# base.net
KiCad netlist of a schematic drawn in EAGLE
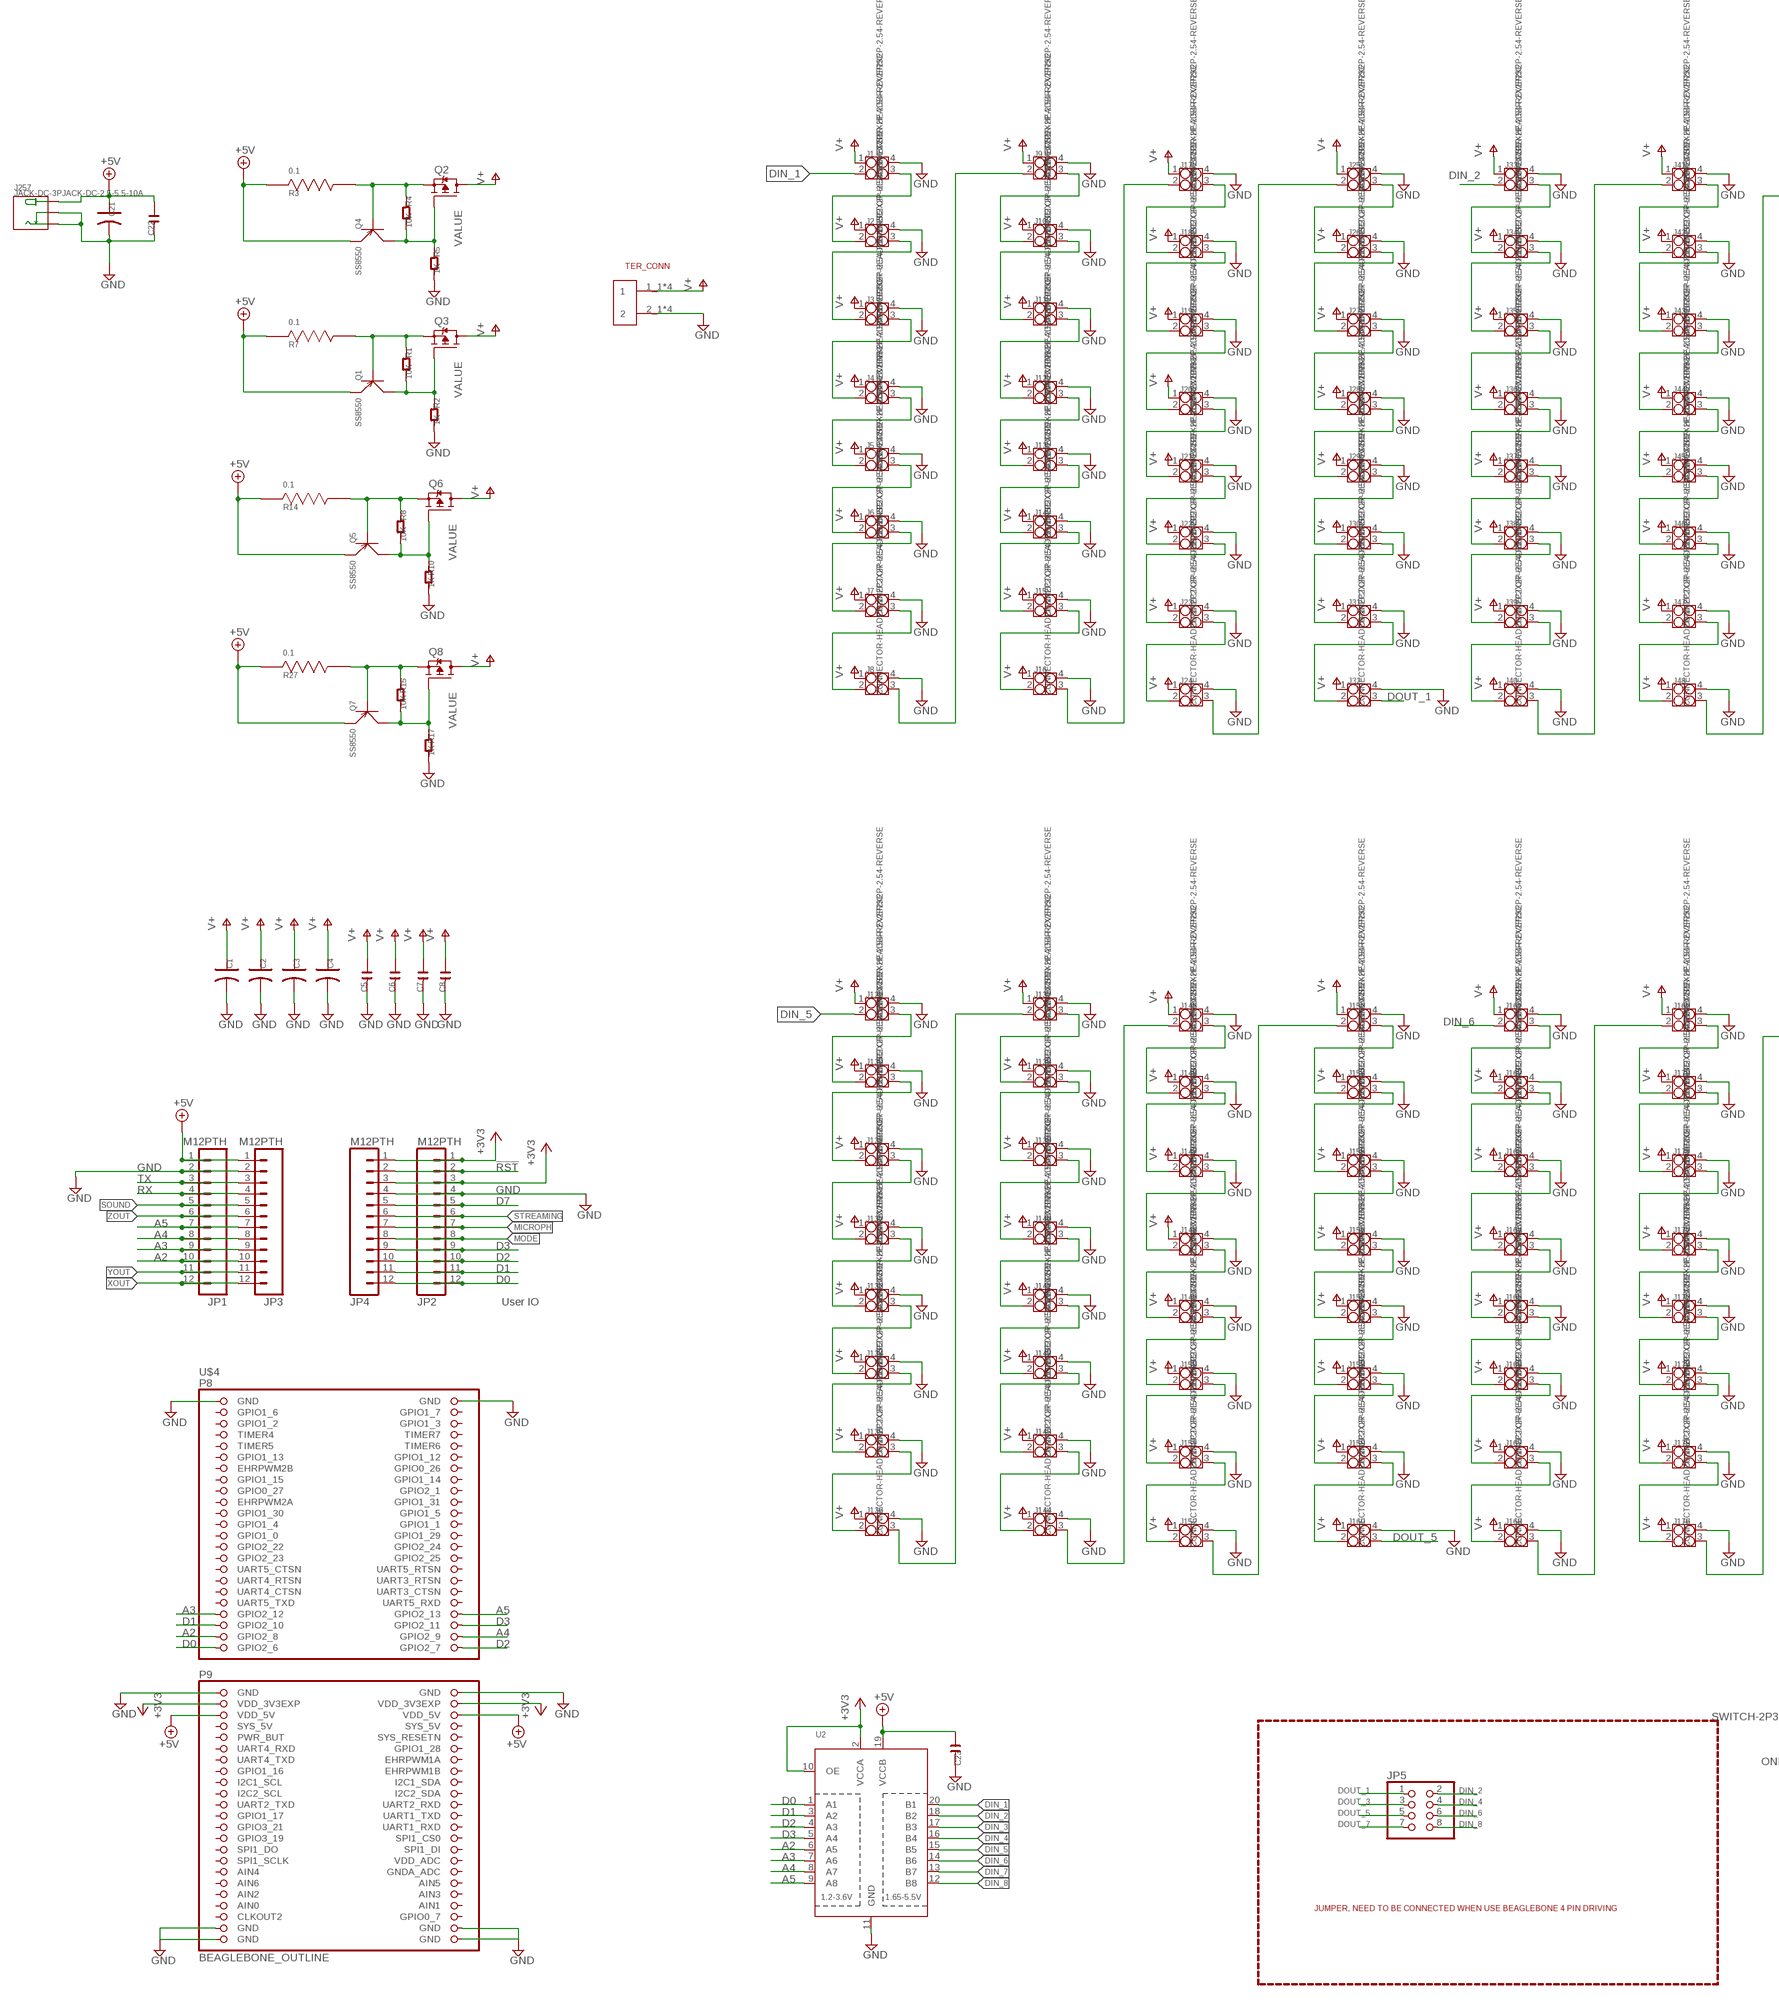
[diagram p0: schematic, sheet 1, part 1 of 2]
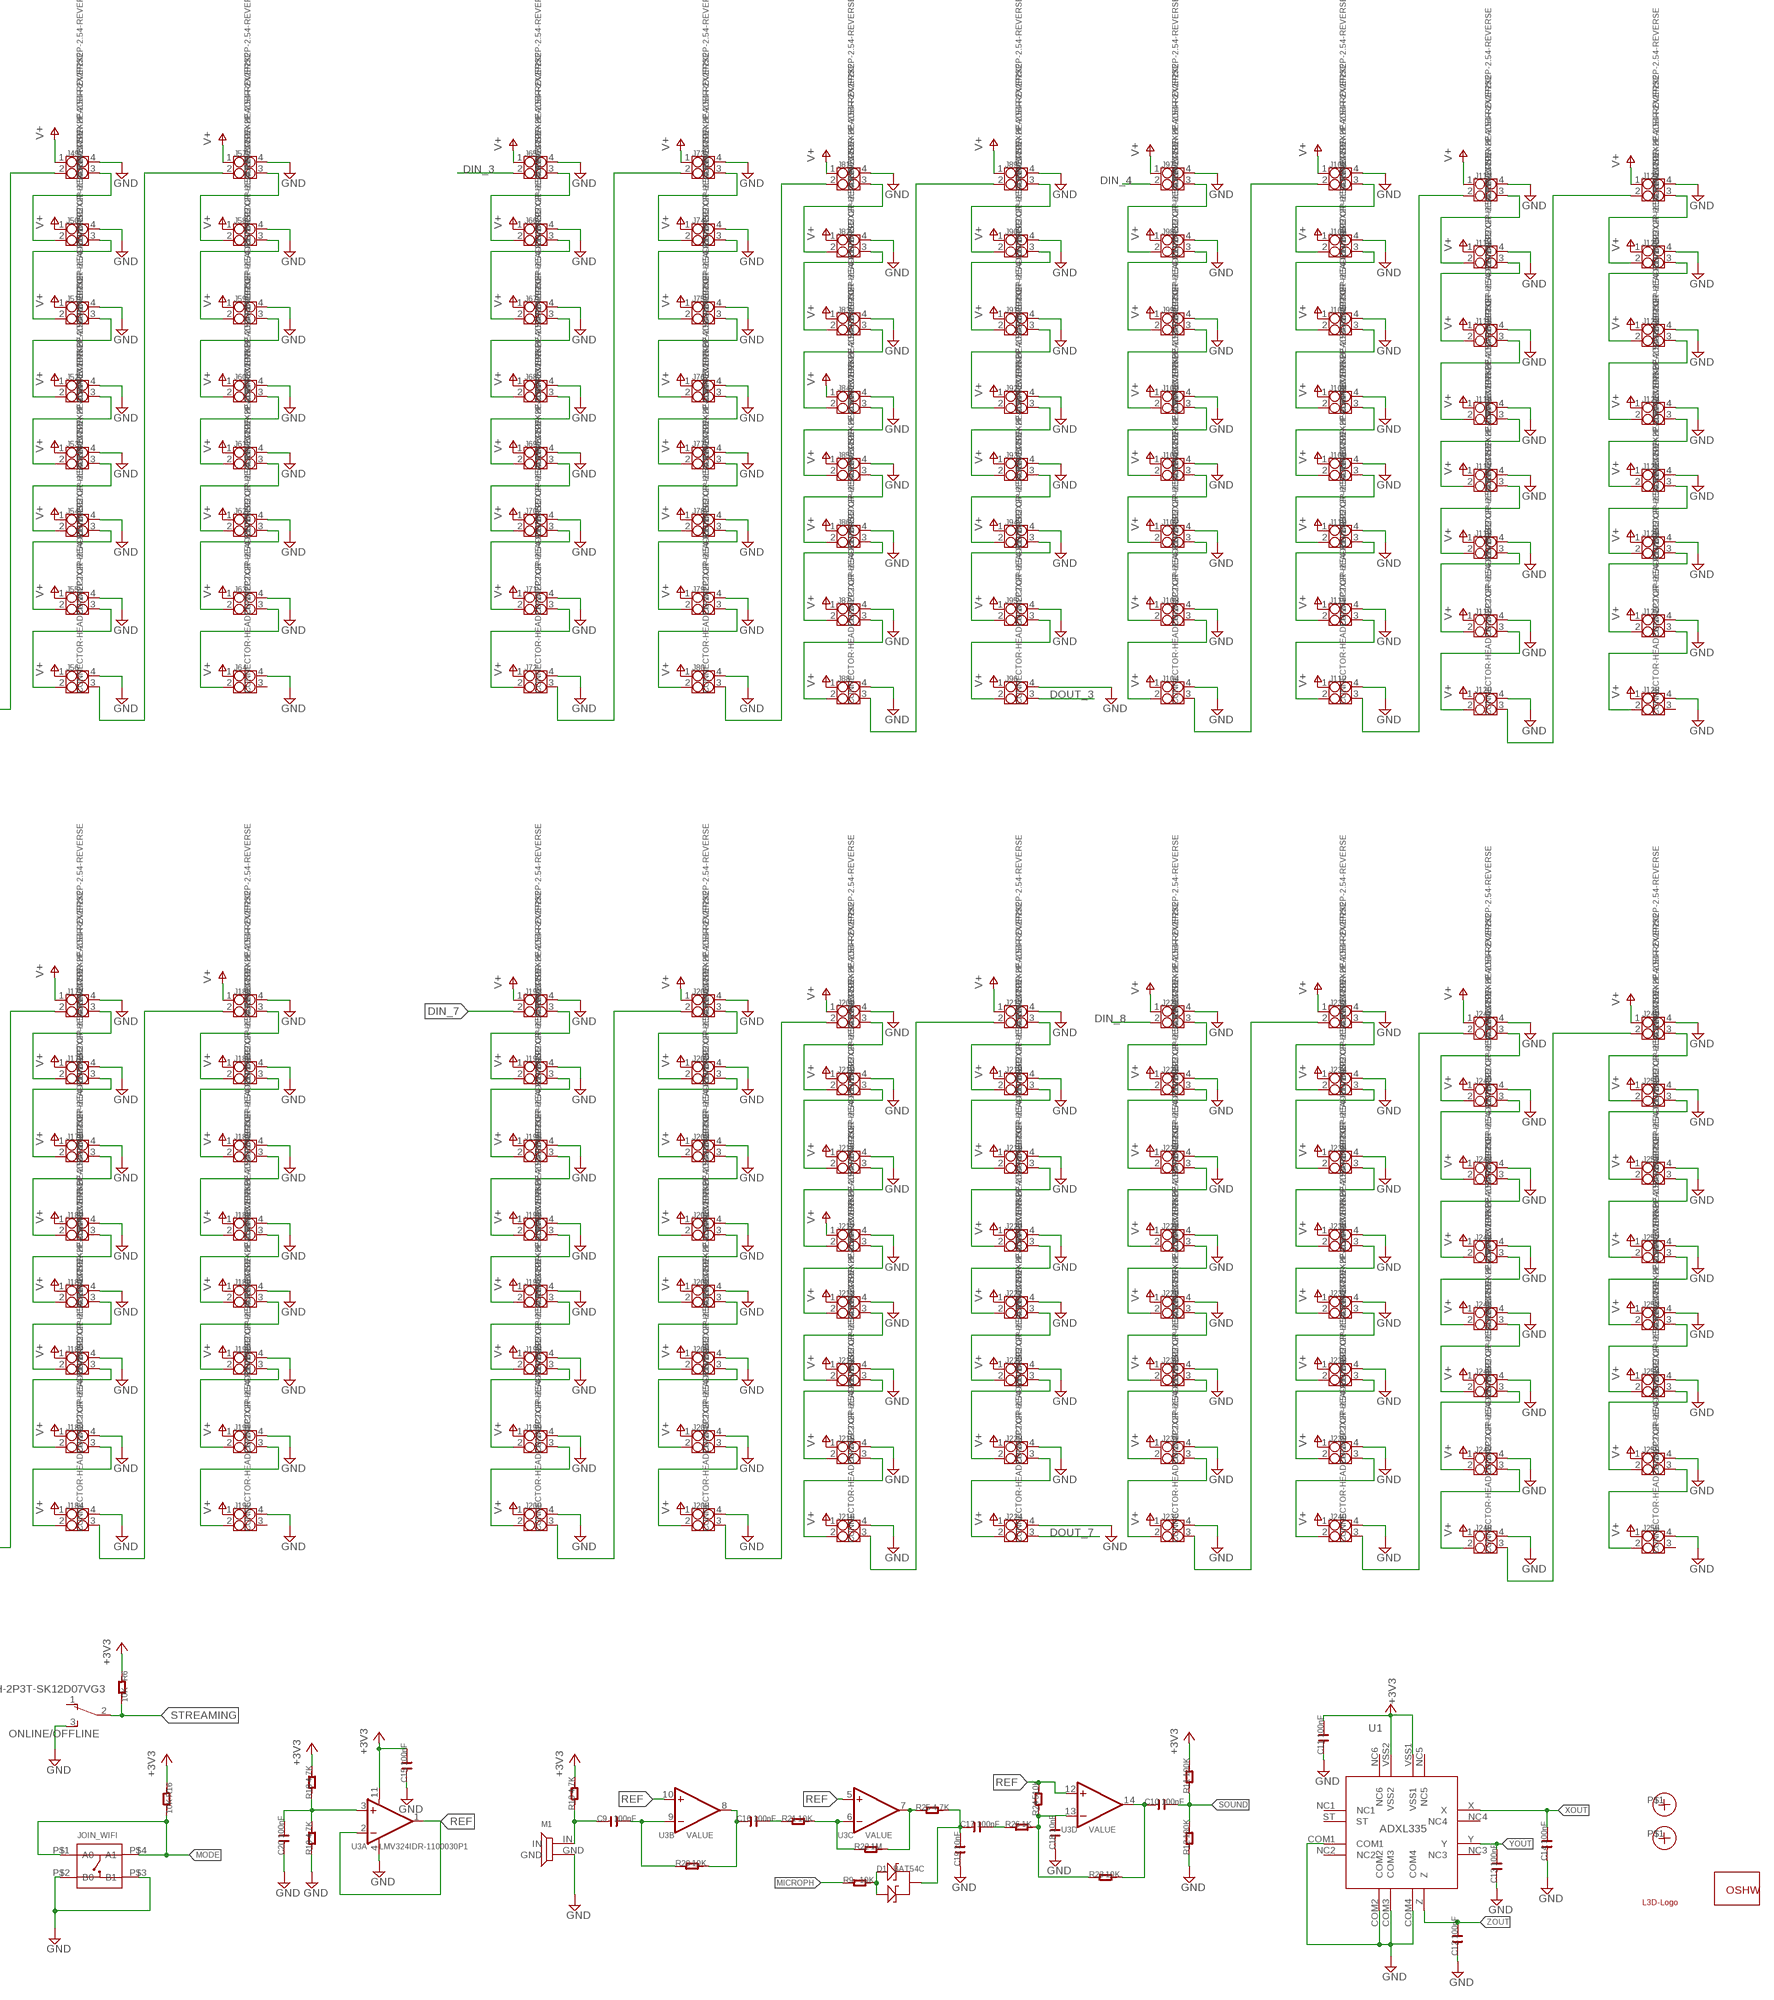
[diagram p1: schematic, sheet 1, part 2 of 2]

(export (version "E")
  (design (tool "Eeschema 10.0.6"))
  (components
    (comp (ref "C1")
      (value "C-POLAR")
      (footprint "eagle-import:CAPACITOR-E3-8")
      (libsource (lib "eagle-import") (part "C-POLAR"))
    )
    (comp (ref "C2")
      (value "C-POLAR")
      (footprint "eagle-import:CAPACITOR-E3-8")
      (libsource (lib "eagle-import") (part "C-POLAR"))
    )
    (comp (ref "C3")
      (value "C-POLAR")
      (footprint "eagle-import:CAPACITOR-E3-8")
      (libsource (lib "eagle-import") (part "C-POLAR"))
    )
    (comp (ref "C4")
      (value "C-POLAR")
      (footprint "eagle-import:CAPACITOR-E3-8")
      (libsource (lib "eagle-import") (part "C-POLAR"))
    )
    (comp (ref "C5")
      (value "C-0603")
      (footprint "eagle-import:C0603")
      (libsource (lib "eagle-import") (part "C-0603"))
    )
    (comp (ref "C6")
      (value "C-0603")
      (footprint "eagle-import:C0603")
      (libsource (lib "eagle-import") (part "C-0603"))
    )
    (comp (ref "C7")
      (value "C-0603")
      (footprint "eagle-import:C0603")
      (libsource (lib "eagle-import") (part "C-0603"))
    )
    (comp (ref "C8")
      (value "C-0603")
      (footprint "eagle-import:C0603")
      (libsource (lib "eagle-import") (part "C-0603"))
    )
    (comp (ref "C9")
      (value "100nF")
      (footprint "eagle-import:C0603")
      (libsource (lib "eagle-import") (part "C-0603"))
    )
    (comp (ref "C10")
      (value "100nF")
      (footprint "eagle-import:C0603")
      (libsource (lib "eagle-import") (part "C-0603"))
    )
    (comp (ref "C11")
      (value "100nF")
      (footprint "eagle-import:C0603")
      (libsource (lib "eagle-import") (part "C-0603"))
    )
    (comp (ref "C12")
      (value "100nF")
      (footprint "eagle-import:C0603")
      (libsource (lib "eagle-import") (part "C-0603"))
    )
    (comp (ref "C13")
      (value "100nF")
      (footprint "eagle-import:C0603")
      (libsource (lib "eagle-import") (part "C-0603"))
    )
    (comp (ref "C14")
      (value "100nF")
      (footprint "eagle-import:C0603")
      (libsource (lib "eagle-import") (part "C-0603"))
    )
    (comp (ref "C15")
      (value "100nF")
      (footprint "eagle-import:C0603")
      (libsource (lib "eagle-import") (part "C-0603"))
    )
    (comp (ref "C16")
      (value "100nF")
      (footprint "eagle-import:C0603")
      (libsource (lib "eagle-import") (part "C-0603"))
    )
    (comp (ref "C17")
      (value "100nF")
      (footprint "eagle-import:C0603")
      (libsource (lib "eagle-import") (part "C-0603"))
    )
    (comp (ref "C18")
      (value "10nF")
      (footprint "eagle-import:C0603")
      (libsource (lib "eagle-import") (part "C-0603"))
    )
    (comp (ref "C19")
      (value "10nF")
      (footprint "eagle-import:C0603")
      (libsource (lib "eagle-import") (part "C-0603"))
    )
    (comp (ref "C20")
      (value "100nF")
      (footprint "eagle-import:C0603")
      (libsource (lib "eagle-import") (part "C-0603"))
    )
    (comp (ref "C21")
      (value "C-POLAR")
      (footprint "eagle-import:CAPACITOR-E3-8")
      (libsource (lib "eagle-import") (part "C-POLAR"))
    )
    (comp (ref "C22")
      (value "C-0603")
      (footprint "eagle-import:C0603")
      (libsource (lib "eagle-import") (part "C-0603"))
    )
    (comp (ref "C23")
      (value "C-0603")
      (footprint "eagle-import:C0603")
      (libsource (lib "eagle-import") (part "C-0603"))
    )
    (comp (ref "D1")
      (value "BAT54C")
      (footprint "eagle-import:SOT23")
      (libsource (lib "eagle-import") (part "BAT54C"))
    )
    (comp (ref "GOLD_ORB_SM1")
      (value "OSHWLOGO_GOLD_ORB_LG")
      (footprint "eagle-import:OSHW0")
      (libsource (lib "eagle-import") (part "OSHWLOGO_GOLD_ORB_LG"))
    )
    (comp (ref "J1")
      (value "CONNECTOR-HEADER-2X2P2X2P-2.54-REVERSE")
      (footprint "eagle-import:2X2P-2.54-REVERSE")
      (libsource (lib "eagle-import") (part "CONNECTOR-HEADER-2X2P2X2P-2.54-REVERSE"))
    )
    (comp (ref "J2")
      (value "CONNECTOR-HEADER-2X2P2X2P-2.54-REVERSE")
      (footprint "eagle-import:2X2P-2.54-REVERSE")
      (libsource (lib "eagle-import") (part "CONNECTOR-HEADER-2X2P2X2P-2.54-REVERSE"))
    )
    (comp (ref "J3")
      (value "CONNECTOR-HEADER-2X2P2X2P-2.54-REVERSE")
      (footprint "eagle-import:2X2P-2.54-REVERSE")
      (libsource (lib "eagle-import") (part "CONNECTOR-HEADER-2X2P2X2P-2.54-REVERSE"))
    )
    (comp (ref "J4")
      (value "CONNECTOR-HEADER-2X2P2X2P-2.54-REVERSE")
      (footprint "eagle-import:2X2P-2.54-REVERSE")
      (libsource (lib "eagle-import") (part "CONNECTOR-HEADER-2X2P2X2P-2.54-REVERSE"))
    )
    (comp (ref "J5")
      (value "CONNECTOR-HEADER-2X2P2X2P-2.54-REVERSE")
      (footprint "eagle-import:2X2P-2.54-REVERSE")
      (libsource (lib "eagle-import") (part "CONNECTOR-HEADER-2X2P2X2P-2.54-REVERSE"))
    )
    (comp (ref "J6")
      (value "CONNECTOR-HEADER-2X2P2X2P-2.54-REVERSE")
      (footprint "eagle-import:2X2P-2.54-REVERSE")
      (libsource (lib "eagle-import") (part "CONNECTOR-HEADER-2X2P2X2P-2.54-REVERSE"))
    )
    (comp (ref "J7")
      (value "CONNECTOR-HEADER-2X2P2X2P-2.54-REVERSE")
      (footprint "eagle-import:2X2P-2.54-REVERSE")
      (libsource (lib "eagle-import") (part "CONNECTOR-HEADER-2X2P2X2P-2.54-REVERSE"))
    )
    (comp (ref "J8")
      (value "CONNECTOR-HEADER-2X2P2X2P-2.54-REVERSE")
      (footprint "eagle-import:2X2P-2.54-REVERSE")
      (libsource (lib "eagle-import") (part "CONNECTOR-HEADER-2X2P2X2P-2.54-REVERSE"))
    )
    (comp (ref "J9")
      (value "CONNECTOR-HEADER-2X2P2X2P-2.54-REVERSE")
      (footprint "eagle-import:2X2P-2.54-REVERSE")
      (libsource (lib "eagle-import") (part "CONNECTOR-HEADER-2X2P2X2P-2.54-REVERSE"))
    )
    (comp (ref "J10")
      (value "CONNECTOR-HEADER-2X2P2X2P-2.54-REVERSE")
      (footprint "eagle-import:2X2P-2.54-REVERSE")
      (libsource (lib "eagle-import") (part "CONNECTOR-HEADER-2X2P2X2P-2.54-REVERSE"))
    )
    (comp (ref "J11")
      (value "CONNECTOR-HEADER-2X2P2X2P-2.54-REVERSE")
      (footprint "eagle-import:2X2P-2.54-REVERSE")
      (libsource (lib "eagle-import") (part "CONNECTOR-HEADER-2X2P2X2P-2.54-REVERSE"))
    )
    (comp (ref "J12")
      (value "CONNECTOR-HEADER-2X2P2X2P-2.54-REVERSE")
      (footprint "eagle-import:2X2P-2.54-REVERSE")
      (libsource (lib "eagle-import") (part "CONNECTOR-HEADER-2X2P2X2P-2.54-REVERSE"))
    )
    (comp (ref "J13")
      (value "CONNECTOR-HEADER-2X2P2X2P-2.54-REVERSE")
      (footprint "eagle-import:2X2P-2.54-REVERSE")
      (libsource (lib "eagle-import") (part "CONNECTOR-HEADER-2X2P2X2P-2.54-REVERSE"))
    )
    (comp (ref "J14")
      (value "CONNECTOR-HEADER-2X2P2X2P-2.54-REVERSE")
      (footprint "eagle-import:2X2P-2.54-REVERSE")
      (libsource (lib "eagle-import") (part "CONNECTOR-HEADER-2X2P2X2P-2.54-REVERSE"))
    )
    (comp (ref "J15")
      (value "CONNECTOR-HEADER-2X2P2X2P-2.54-REVERSE")
      (footprint "eagle-import:2X2P-2.54-REVERSE")
      (libsource (lib "eagle-import") (part "CONNECTOR-HEADER-2X2P2X2P-2.54-REVERSE"))
    )
    (comp (ref "J16")
      (value "CONNECTOR-HEADER-2X2P2X2P-2.54-REVERSE")
      (footprint "eagle-import:2X2P-2.54-REVERSE")
      (libsource (lib "eagle-import") (part "CONNECTOR-HEADER-2X2P2X2P-2.54-REVERSE"))
    )
    (comp (ref "J17")
      (value "CONNECTOR-HEADER-2X2P2X2P-2.54-REVERSE")
      (footprint "eagle-import:2X2P-2.54-REVERSE")
      (libsource (lib "eagle-import") (part "CONNECTOR-HEADER-2X2P2X2P-2.54-REVERSE"))
    )
    (comp (ref "J18")
      (value "CONNECTOR-HEADER-2X2P2X2P-2.54-REVERSE")
      (footprint "eagle-import:2X2P-2.54-REVERSE")
      (libsource (lib "eagle-import") (part "CONNECTOR-HEADER-2X2P2X2P-2.54-REVERSE"))
    )
    (comp (ref "J19")
      (value "CONNECTOR-HEADER-2X2P2X2P-2.54-REVERSE")
      (footprint "eagle-import:2X2P-2.54-REVERSE")
      (libsource (lib "eagle-import") (part "CONNECTOR-HEADER-2X2P2X2P-2.54-REVERSE"))
    )
    (comp (ref "J20")
      (value "CONNECTOR-HEADER-2X2P2X2P-2.54-REVERSE")
      (footprint "eagle-import:2X2P-2.54-REVERSE")
      (libsource (lib "eagle-import") (part "CONNECTOR-HEADER-2X2P2X2P-2.54-REVERSE"))
    )
    (comp (ref "J21")
      (value "CONNECTOR-HEADER-2X2P2X2P-2.54-REVERSE")
      (footprint "eagle-import:2X2P-2.54-REVERSE")
      (libsource (lib "eagle-import") (part "CONNECTOR-HEADER-2X2P2X2P-2.54-REVERSE"))
    )
    (comp (ref "J22")
      (value "CONNECTOR-HEADER-2X2P2X2P-2.54-REVERSE")
      (footprint "eagle-import:2X2P-2.54-REVERSE")
      (libsource (lib "eagle-import") (part "CONNECTOR-HEADER-2X2P2X2P-2.54-REVERSE"))
    )
    (comp (ref "J23")
      (value "CONNECTOR-HEADER-2X2P2X2P-2.54-REVERSE")
      (footprint "eagle-import:2X2P-2.54-REVERSE")
      (libsource (lib "eagle-import") (part "CONNECTOR-HEADER-2X2P2X2P-2.54-REVERSE"))
    )
    (comp (ref "J24")
      (value "CONNECTOR-HEADER-2X2P2X2P-2.54-REVERSE")
      (footprint "eagle-import:2X2P-2.54-REVERSE")
      (libsource (lib "eagle-import") (part "CONNECTOR-HEADER-2X2P2X2P-2.54-REVERSE"))
    )
    (comp (ref "J25")
      (value "CONNECTOR-HEADER-2X2P2X2P-2.54-REVERSE")
      (footprint "eagle-import:2X2P-2.54-REVERSE")
      (libsource (lib "eagle-import") (part "CONNECTOR-HEADER-2X2P2X2P-2.54-REVERSE"))
    )
    (comp (ref "J26")
      (value "CONNECTOR-HEADER-2X2P2X2P-2.54-REVERSE")
      (footprint "eagle-import:2X2P-2.54-REVERSE")
      (libsource (lib "eagle-import") (part "CONNECTOR-HEADER-2X2P2X2P-2.54-REVERSE"))
    )
    (comp (ref "J27")
      (value "CONNECTOR-HEADER-2X2P2X2P-2.54-REVERSE")
      (footprint "eagle-import:2X2P-2.54-REVERSE")
      (libsource (lib "eagle-import") (part "CONNECTOR-HEADER-2X2P2X2P-2.54-REVERSE"))
    )
    (comp (ref "J28")
      (value "CONNECTOR-HEADER-2X2P2X2P-2.54-REVERSE")
      (footprint "eagle-import:2X2P-2.54-REVERSE")
      (libsource (lib "eagle-import") (part "CONNECTOR-HEADER-2X2P2X2P-2.54-REVERSE"))
    )
    (comp (ref "J29")
      (value "CONNECTOR-HEADER-2X2P2X2P-2.54-REVERSE")
      (footprint "eagle-import:2X2P-2.54-REVERSE")
      (libsource (lib "eagle-import") (part "CONNECTOR-HEADER-2X2P2X2P-2.54-REVERSE"))
    )
    (comp (ref "J30")
      (value "CONNECTOR-HEADER-2X2P2X2P-2.54-REVERSE")
      (footprint "eagle-import:2X2P-2.54-REVERSE")
      (libsource (lib "eagle-import") (part "CONNECTOR-HEADER-2X2P2X2P-2.54-REVERSE"))
    )
    (comp (ref "J31")
      (value "CONNECTOR-HEADER-2X2P2X2P-2.54-REVERSE")
      (footprint "eagle-import:2X2P-2.54-REVERSE")
      (libsource (lib "eagle-import") (part "CONNECTOR-HEADER-2X2P2X2P-2.54-REVERSE"))
    )
    (comp (ref "J32")
      (value "CONNECTOR-HEADER-2X2P2X2P-2.54-REVERSE")
      (footprint "eagle-import:2X2P-2.54-REVERSE")
      (libsource (lib "eagle-import") (part "CONNECTOR-HEADER-2X2P2X2P-2.54-REVERSE"))
    )
    (comp (ref "J33")
      (value "CONNECTOR-HEADER-2X2P2X2P-2.54-REVERSE")
      (footprint "eagle-import:2X2P-2.54-REVERSE")
      (libsource (lib "eagle-import") (part "CONNECTOR-HEADER-2X2P2X2P-2.54-REVERSE"))
    )
    (comp (ref "J34")
      (value "CONNECTOR-HEADER-2X2P2X2P-2.54-REVERSE")
      (footprint "eagle-import:2X2P-2.54-REVERSE")
      (libsource (lib "eagle-import") (part "CONNECTOR-HEADER-2X2P2X2P-2.54-REVERSE"))
    )
    (comp (ref "J35")
      (value "CONNECTOR-HEADER-2X2P2X2P-2.54-REVERSE")
      (footprint "eagle-import:2X2P-2.54-REVERSE")
      (libsource (lib "eagle-import") (part "CONNECTOR-HEADER-2X2P2X2P-2.54-REVERSE"))
    )
    (comp (ref "J36")
      (value "CONNECTOR-HEADER-2X2P2X2P-2.54-REVERSE")
      (footprint "eagle-import:2X2P-2.54-REVERSE")
      (libsource (lib "eagle-import") (part "CONNECTOR-HEADER-2X2P2X2P-2.54-REVERSE"))
    )
    (comp (ref "J37")
      (value "CONNECTOR-HEADER-2X2P2X2P-2.54-REVERSE")
      (footprint "eagle-import:2X2P-2.54-REVERSE")
      (libsource (lib "eagle-import") (part "CONNECTOR-HEADER-2X2P2X2P-2.54-REVERSE"))
    )
    (comp (ref "J38")
      (value "CONNECTOR-HEADER-2X2P2X2P-2.54-REVERSE")
      (footprint "eagle-import:2X2P-2.54-REVERSE")
      (libsource (lib "eagle-import") (part "CONNECTOR-HEADER-2X2P2X2P-2.54-REVERSE"))
    )
    (comp (ref "J39")
      (value "CONNECTOR-HEADER-2X2P2X2P-2.54-REVERSE")
      (footprint "eagle-import:2X2P-2.54-REVERSE")
      (libsource (lib "eagle-import") (part "CONNECTOR-HEADER-2X2P2X2P-2.54-REVERSE"))
    )
    (comp (ref "J40")
      (value "CONNECTOR-HEADER-2X2P2X2P-2.54-REVERSE")
      (footprint "eagle-import:2X2P-2.54-REVERSE")
      (libsource (lib "eagle-import") (part "CONNECTOR-HEADER-2X2P2X2P-2.54-REVERSE"))
    )
    (comp (ref "J41")
      (value "CONNECTOR-HEADER-2X2P2X2P-2.54-REVERSE")
      (footprint "eagle-import:2X2P-2.54-REVERSE")
      (libsource (lib "eagle-import") (part "CONNECTOR-HEADER-2X2P2X2P-2.54-REVERSE"))
    )
    (comp (ref "J42")
      (value "CONNECTOR-HEADER-2X2P2X2P-2.54-REVERSE")
      (footprint "eagle-import:2X2P-2.54-REVERSE")
      (libsource (lib "eagle-import") (part "CONNECTOR-HEADER-2X2P2X2P-2.54-REVERSE"))
    )
    (comp (ref "J43")
      (value "CONNECTOR-HEADER-2X2P2X2P-2.54-REVERSE")
      (footprint "eagle-import:2X2P-2.54-REVERSE")
      (libsource (lib "eagle-import") (part "CONNECTOR-HEADER-2X2P2X2P-2.54-REVERSE"))
    )
    (comp (ref "J44")
      (value "CONNECTOR-HEADER-2X2P2X2P-2.54-REVERSE")
      (footprint "eagle-import:2X2P-2.54-REVERSE")
      (libsource (lib "eagle-import") (part "CONNECTOR-HEADER-2X2P2X2P-2.54-REVERSE"))
    )
    (comp (ref "J45")
      (value "CONNECTOR-HEADER-2X2P2X2P-2.54-REVERSE")
      (footprint "eagle-import:2X2P-2.54-REVERSE")
      (libsource (lib "eagle-import") (part "CONNECTOR-HEADER-2X2P2X2P-2.54-REVERSE"))
    )
    (comp (ref "J46")
      (value "CONNECTOR-HEADER-2X2P2X2P-2.54-REVERSE")
      (footprint "eagle-import:2X2P-2.54-REVERSE")
      (libsource (lib "eagle-import") (part "CONNECTOR-HEADER-2X2P2X2P-2.54-REVERSE"))
    )
    (comp (ref "J47")
      (value "CONNECTOR-HEADER-2X2P2X2P-2.54-REVERSE")
      (footprint "eagle-import:2X2P-2.54-REVERSE")
      (libsource (lib "eagle-import") (part "CONNECTOR-HEADER-2X2P2X2P-2.54-REVERSE"))
    )
    (comp (ref "J48")
      (value "CONNECTOR-HEADER-2X2P2X2P-2.54-REVERSE")
      (footprint "eagle-import:2X2P-2.54-REVERSE")
      (libsource (lib "eagle-import") (part "CONNECTOR-HEADER-2X2P2X2P-2.54-REVERSE"))
    )
    (comp (ref "J49")
      (value "CONNECTOR-HEADER-2X2P2X2P-2.54-REVERSE")
      (footprint "eagle-import:2X2P-2.54-REVERSE")
      (libsource (lib "eagle-import") (part "CONNECTOR-HEADER-2X2P2X2P-2.54-REVERSE"))
    )
    (comp (ref "J50")
      (value "CONNECTOR-HEADER-2X2P2X2P-2.54-REVERSE")
      (footprint "eagle-import:2X2P-2.54-REVERSE")
      (libsource (lib "eagle-import") (part "CONNECTOR-HEADER-2X2P2X2P-2.54-REVERSE"))
    )
    (comp (ref "J51")
      (value "CONNECTOR-HEADER-2X2P2X2P-2.54-REVERSE")
      (footprint "eagle-import:2X2P-2.54-REVERSE")
      (libsource (lib "eagle-import") (part "CONNECTOR-HEADER-2X2P2X2P-2.54-REVERSE"))
    )
    (comp (ref "J52")
      (value "CONNECTOR-HEADER-2X2P2X2P-2.54-REVERSE")
      (footprint "eagle-import:2X2P-2.54-REVERSE")
      (libsource (lib "eagle-import") (part "CONNECTOR-HEADER-2X2P2X2P-2.54-REVERSE"))
    )
    (comp (ref "J53")
      (value "CONNECTOR-HEADER-2X2P2X2P-2.54-REVERSE")
      (footprint "eagle-import:2X2P-2.54-REVERSE")
      (libsource (lib "eagle-import") (part "CONNECTOR-HEADER-2X2P2X2P-2.54-REVERSE"))
    )
    (comp (ref "J54")
      (value "CONNECTOR-HEADER-2X2P2X2P-2.54-REVERSE")
      (footprint "eagle-import:2X2P-2.54-REVERSE")
      (libsource (lib "eagle-import") (part "CONNECTOR-HEADER-2X2P2X2P-2.54-REVERSE"))
    )
    (comp (ref "J55")
      (value "CONNECTOR-HEADER-2X2P2X2P-2.54-REVERSE")
      (footprint "eagle-import:2X2P-2.54-REVERSE")
      (libsource (lib "eagle-import") (part "CONNECTOR-HEADER-2X2P2X2P-2.54-REVERSE"))
    )
    (comp (ref "J56")
      (value "CONNECTOR-HEADER-2X2P2X2P-2.54-REVERSE")
      (footprint "eagle-import:2X2P-2.54-REVERSE")
      (libsource (lib "eagle-import") (part "CONNECTOR-HEADER-2X2P2X2P-2.54-REVERSE"))
    )
    (comp (ref "J57")
      (value "CONNECTOR-HEADER-2X2P2X2P-2.54-REVERSE")
      (footprint "eagle-import:2X2P-2.54-REVERSE")
      (libsource (lib "eagle-import") (part "CONNECTOR-HEADER-2X2P2X2P-2.54-REVERSE"))
    )
    (comp (ref "J58")
      (value "CONNECTOR-HEADER-2X2P2X2P-2.54-REVERSE")
      (footprint "eagle-import:2X2P-2.54-REVERSE")
      (libsource (lib "eagle-import") (part "CONNECTOR-HEADER-2X2P2X2P-2.54-REVERSE"))
    )
    (comp (ref "J59")
      (value "CONNECTOR-HEADER-2X2P2X2P-2.54-REVERSE")
      (footprint "eagle-import:2X2P-2.54-REVERSE")
      (libsource (lib "eagle-import") (part "CONNECTOR-HEADER-2X2P2X2P-2.54-REVERSE"))
    )
    (comp (ref "J60")
      (value "CONNECTOR-HEADER-2X2P2X2P-2.54-REVERSE")
      (footprint "eagle-import:2X2P-2.54-REVERSE")
      (libsource (lib "eagle-import") (part "CONNECTOR-HEADER-2X2P2X2P-2.54-REVERSE"))
    )
    (comp (ref "J61")
      (value "CONNECTOR-HEADER-2X2P2X2P-2.54-REVERSE")
      (footprint "eagle-import:2X2P-2.54-REVERSE")
      (libsource (lib "eagle-import") (part "CONNECTOR-HEADER-2X2P2X2P-2.54-REVERSE"))
    )
    (comp (ref "J62")
      (value "CONNECTOR-HEADER-2X2P2X2P-2.54-REVERSE")
      (footprint "eagle-import:2X2P-2.54-REVERSE")
      (libsource (lib "eagle-import") (part "CONNECTOR-HEADER-2X2P2X2P-2.54-REVERSE"))
    )
    (comp (ref "J63")
      (value "CONNECTOR-HEADER-2X2P2X2P-2.54-REVERSE")
      (footprint "eagle-import:2X2P-2.54-REVERSE")
      (libsource (lib "eagle-import") (part "CONNECTOR-HEADER-2X2P2X2P-2.54-REVERSE"))
    )
    (comp (ref "J64")
      (value "CONNECTOR-HEADER-2X2P2X2P-2.54-REVERSE")
      (footprint "eagle-import:2X2P-2.54-REVERSE")
      (libsource (lib "eagle-import") (part "CONNECTOR-HEADER-2X2P2X2P-2.54-REVERSE"))
    )
    (comp (ref "J65")
      (value "CONNECTOR-HEADER-2X2P2X2P-2.54-REVERSE")
      (footprint "eagle-import:2X2P-2.54-REVERSE")
      (libsource (lib "eagle-import") (part "CONNECTOR-HEADER-2X2P2X2P-2.54-REVERSE"))
    )
    (comp (ref "J66")
      (value "CONNECTOR-HEADER-2X2P2X2P-2.54-REVERSE")
      (footprint "eagle-import:2X2P-2.54-REVERSE")
      (libsource (lib "eagle-import") (part "CONNECTOR-HEADER-2X2P2X2P-2.54-REVERSE"))
    )
    (comp (ref "J67")
      (value "CONNECTOR-HEADER-2X2P2X2P-2.54-REVERSE")
      (footprint "eagle-import:2X2P-2.54-REVERSE")
      (libsource (lib "eagle-import") (part "CONNECTOR-HEADER-2X2P2X2P-2.54-REVERSE"))
    )
    (comp (ref "J68")
      (value "CONNECTOR-HEADER-2X2P2X2P-2.54-REVERSE")
      (footprint "eagle-import:2X2P-2.54-REVERSE")
      (libsource (lib "eagle-import") (part "CONNECTOR-HEADER-2X2P2X2P-2.54-REVERSE"))
    )
    (comp (ref "J69")
      (value "CONNECTOR-HEADER-2X2P2X2P-2.54-REVERSE")
      (footprint "eagle-import:2X2P-2.54-REVERSE")
      (libsource (lib "eagle-import") (part "CONNECTOR-HEADER-2X2P2X2P-2.54-REVERSE"))
    )
    (comp (ref "J70")
      (value "CONNECTOR-HEADER-2X2P2X2P-2.54-REVERSE")
      (footprint "eagle-import:2X2P-2.54-REVERSE")
      (libsource (lib "eagle-import") (part "CONNECTOR-HEADER-2X2P2X2P-2.54-REVERSE"))
    )
    (comp (ref "J71")
      (value "CONNECTOR-HEADER-2X2P2X2P-2.54-REVERSE")
      (footprint "eagle-import:2X2P-2.54-REVERSE")
      (libsource (lib "eagle-import") (part "CONNECTOR-HEADER-2X2P2X2P-2.54-REVERSE"))
    )
    (comp (ref "J72")
      (value "CONNECTOR-HEADER-2X2P2X2P-2.54-REVERSE")
      (footprint "eagle-import:2X2P-2.54-REVERSE")
      (libsource (lib "eagle-import") (part "CONNECTOR-HEADER-2X2P2X2P-2.54-REVERSE"))
    )
    (comp (ref "J73")
      (value "CONNECTOR-HEADER-2X2P2X2P-2.54-REVERSE")
      (footprint "eagle-import:2X2P-2.54-REVERSE")
      (libsource (lib "eagle-import") (part "CONNECTOR-HEADER-2X2P2X2P-2.54-REVERSE"))
    )
    (comp (ref "J74")
      (value "CONNECTOR-HEADER-2X2P2X2P-2.54-REVERSE")
      (footprint "eagle-import:2X2P-2.54-REVERSE")
      (libsource (lib "eagle-import") (part "CONNECTOR-HEADER-2X2P2X2P-2.54-REVERSE"))
    )
    (comp (ref "J75")
      (value "CONNECTOR-HEADER-2X2P2X2P-2.54-REVERSE")
      (footprint "eagle-import:2X2P-2.54-REVERSE")
      (libsource (lib "eagle-import") (part "CONNECTOR-HEADER-2X2P2X2P-2.54-REVERSE"))
    )
    (comp (ref "J76")
      (value "CONNECTOR-HEADER-2X2P2X2P-2.54-REVERSE")
      (footprint "eagle-import:2X2P-2.54-REVERSE")
      (libsource (lib "eagle-import") (part "CONNECTOR-HEADER-2X2P2X2P-2.54-REVERSE"))
    )
    (comp (ref "J77")
      (value "CONNECTOR-HEADER-2X2P2X2P-2.54-REVERSE")
      (footprint "eagle-import:2X2P-2.54-REVERSE")
      (libsource (lib "eagle-import") (part "CONNECTOR-HEADER-2X2P2X2P-2.54-REVERSE"))
    )
    (comp (ref "J78")
      (value "CONNECTOR-HEADER-2X2P2X2P-2.54-REVERSE")
      (footprint "eagle-import:2X2P-2.54-REVERSE")
      (libsource (lib "eagle-import") (part "CONNECTOR-HEADER-2X2P2X2P-2.54-REVERSE"))
    )
    (comp (ref "J79")
      (value "CONNECTOR-HEADER-2X2P2X2P-2.54-REVERSE")
      (footprint "eagle-import:2X2P-2.54-REVERSE")
      (libsource (lib "eagle-import") (part "CONNECTOR-HEADER-2X2P2X2P-2.54-REVERSE"))
    )
    (comp (ref "J80")
      (value "CONNECTOR-HEADER-2X2P2X2P-2.54-REVERSE")
      (footprint "eagle-import:2X2P-2.54-REVERSE")
      (libsource (lib "eagle-import") (part "CONNECTOR-HEADER-2X2P2X2P-2.54-REVERSE"))
    )
    (comp (ref "J81")
      (value "CONNECTOR-HEADER-2X2P2X2P-2.54-REVERSE")
      (footprint "eagle-import:2X2P-2.54-REVERSE")
      (libsource (lib "eagle-import") (part "CONNECTOR-HEADER-2X2P2X2P-2.54-REVERSE"))
    )
    (comp (ref "J82")
      (value "CONNECTOR-HEADER-2X2P2X2P-2.54-REVERSE")
      (footprint "eagle-import:2X2P-2.54-REVERSE")
      (libsource (lib "eagle-import") (part "CONNECTOR-HEADER-2X2P2X2P-2.54-REVERSE"))
    )
    (comp (ref "J83")
      (value "CONNECTOR-HEADER-2X2P2X2P-2.54-REVERSE")
      (footprint "eagle-import:2X2P-2.54-REVERSE")
      (libsource (lib "eagle-import") (part "CONNECTOR-HEADER-2X2P2X2P-2.54-REVERSE"))
    )
    (comp (ref "J84")
      (value "CONNECTOR-HEADER-2X2P2X2P-2.54-REVERSE")
      (footprint "eagle-import:2X2P-2.54-REVERSE")
      (libsource (lib "eagle-import") (part "CONNECTOR-HEADER-2X2P2X2P-2.54-REVERSE"))
    )
    (comp (ref "J85")
      (value "CONNECTOR-HEADER-2X2P2X2P-2.54-REVERSE")
      (footprint "eagle-import:2X2P-2.54-REVERSE")
      (libsource (lib "eagle-import") (part "CONNECTOR-HEADER-2X2P2X2P-2.54-REVERSE"))
    )
    (comp (ref "J86")
      (value "CONNECTOR-HEADER-2X2P2X2P-2.54-REVERSE")
      (footprint "eagle-import:2X2P-2.54-REVERSE")
      (libsource (lib "eagle-import") (part "CONNECTOR-HEADER-2X2P2X2P-2.54-REVERSE"))
    )
    (comp (ref "J87")
      (value "CONNECTOR-HEADER-2X2P2X2P-2.54-REVERSE")
      (footprint "eagle-import:2X2P-2.54-REVERSE")
      (libsource (lib "eagle-import") (part "CONNECTOR-HEADER-2X2P2X2P-2.54-REVERSE"))
    )
    (comp (ref "J88")
      (value "CONNECTOR-HEADER-2X2P2X2P-2.54-REVERSE")
      (footprint "eagle-import:2X2P-2.54-REVERSE")
      (libsource (lib "eagle-import") (part "CONNECTOR-HEADER-2X2P2X2P-2.54-REVERSE"))
    )
    (comp (ref "J89")
      (value "CONNECTOR-HEADER-2X2P2X2P-2.54-REVERSE")
      (footprint "eagle-import:2X2P-2.54-REVERSE")
      (libsource (lib "eagle-import") (part "CONNECTOR-HEADER-2X2P2X2P-2.54-REVERSE"))
    )
    (comp (ref "J90")
      (value "CONNECTOR-HEADER-2X2P2X2P-2.54-REVERSE")
      (footprint "eagle-import:2X2P-2.54-REVERSE")
      (libsource (lib "eagle-import") (part "CONNECTOR-HEADER-2X2P2X2P-2.54-REVERSE"))
    )
    (comp (ref "J91")
      (value "CONNECTOR-HEADER-2X2P2X2P-2.54-REVERSE")
      (footprint "eagle-import:2X2P-2.54-REVERSE")
      (libsource (lib "eagle-import") (part "CONNECTOR-HEADER-2X2P2X2P-2.54-REVERSE"))
    )
    (comp (ref "J92")
      (value "CONNECTOR-HEADER-2X2P2X2P-2.54-REVERSE")
      (footprint "eagle-import:2X2P-2.54-REVERSE")
      (libsource (lib "eagle-import") (part "CONNECTOR-HEADER-2X2P2X2P-2.54-REVERSE"))
    )
    (comp (ref "J93")
      (value "CONNECTOR-HEADER-2X2P2X2P-2.54-REVERSE")
      (footprint "eagle-import:2X2P-2.54-REVERSE")
      (libsource (lib "eagle-import") (part "CONNECTOR-HEADER-2X2P2X2P-2.54-REVERSE"))
    )
    (comp (ref "J94")
      (value "CONNECTOR-HEADER-2X2P2X2P-2.54-REVERSE")
      (footprint "eagle-import:2X2P-2.54-REVERSE")
      (libsource (lib "eagle-import") (part "CONNECTOR-HEADER-2X2P2X2P-2.54-REVERSE"))
    )
    (comp (ref "J95")
      (value "CONNECTOR-HEADER-2X2P2X2P-2.54-REVERSE")
      (footprint "eagle-import:2X2P-2.54-REVERSE")
      (libsource (lib "eagle-import") (part "CONNECTOR-HEADER-2X2P2X2P-2.54-REVERSE"))
    )
    (comp (ref "J96")
      (value "CONNECTOR-HEADER-2X2P2X2P-2.54-REVERSE")
      (footprint "eagle-import:2X2P-2.54-REVERSE")
      (libsource (lib "eagle-import") (part "CONNECTOR-HEADER-2X2P2X2P-2.54-REVERSE"))
    )
    (comp (ref "J97")
      (value "CONNECTOR-HEADER-2X2P2X2P-2.54-REVERSE")
      (footprint "eagle-import:2X2P-2.54-REVERSE")
      (libsource (lib "eagle-import") (part "CONNECTOR-HEADER-2X2P2X2P-2.54-REVERSE"))
    )
    (comp (ref "J98")
      (value "CONNECTOR-HEADER-2X2P2X2P-2.54-REVERSE")
      (footprint "eagle-import:2X2P-2.54-REVERSE")
      (libsource (lib "eagle-import") (part "CONNECTOR-HEADER-2X2P2X2P-2.54-REVERSE"))
    )
    (comp (ref "J99")
      (value "CONNECTOR-HEADER-2X2P2X2P-2.54-REVERSE")
      (footprint "eagle-import:2X2P-2.54-REVERSE")
      (libsource (lib "eagle-import") (part "CONNECTOR-HEADER-2X2P2X2P-2.54-REVERSE"))
    )
    (comp (ref "J100")
      (value "CONNECTOR-HEADER-2X2P2X2P-2.54-REVERSE")
      (footprint "eagle-import:2X2P-2.54-REVERSE")
      (libsource (lib "eagle-import") (part "CONNECTOR-HEADER-2X2P2X2P-2.54-REVERSE"))
    )
    (comp (ref "J101")
      (value "CONNECTOR-HEADER-2X2P2X2P-2.54-REVERSE")
      (footprint "eagle-import:2X2P-2.54-REVERSE")
      (libsource (lib "eagle-import") (part "CONNECTOR-HEADER-2X2P2X2P-2.54-REVERSE"))
    )
    (comp (ref "J102")
      (value "CONNECTOR-HEADER-2X2P2X2P-2.54-REVERSE")
      (footprint "eagle-import:2X2P-2.54-REVERSE")
      (libsource (lib "eagle-import") (part "CONNECTOR-HEADER-2X2P2X2P-2.54-REVERSE"))
    )
    (comp (ref "J103")
      (value "CONNECTOR-HEADER-2X2P2X2P-2.54-REVERSE")
      (footprint "eagle-import:2X2P-2.54-REVERSE")
      (libsource (lib "eagle-import") (part "CONNECTOR-HEADER-2X2P2X2P-2.54-REVERSE"))
    )
    (comp (ref "J104")
      (value "CONNECTOR-HEADER-2X2P2X2P-2.54-REVERSE")
      (footprint "eagle-import:2X2P-2.54-REVERSE")
      (libsource (lib "eagle-import") (part "CONNECTOR-HEADER-2X2P2X2P-2.54-REVERSE"))
    )
    (comp (ref "J105")
      (value "CONNECTOR-HEADER-2X2P2X2P-2.54-REVERSE")
      (footprint "eagle-import:2X2P-2.54-REVERSE")
      (libsource (lib "eagle-import") (part "CONNECTOR-HEADER-2X2P2X2P-2.54-REVERSE"))
    )
    (comp (ref "J106")
      (value "CONNECTOR-HEADER-2X2P2X2P-2.54-REVERSE")
      (footprint "eagle-import:2X2P-2.54-REVERSE")
      (libsource (lib "eagle-import") (part "CONNECTOR-HEADER-2X2P2X2P-2.54-REVERSE"))
    )
    (comp (ref "J107")
      (value "CONNECTOR-HEADER-2X2P2X2P-2.54-REVERSE")
      (footprint "eagle-import:2X2P-2.54-REVERSE")
      (libsource (lib "eagle-import") (part "CONNECTOR-HEADER-2X2P2X2P-2.54-REVERSE"))
    )
    (comp (ref "J108")
      (value "CONNECTOR-HEADER-2X2P2X2P-2.54-REVERSE")
      (footprint "eagle-import:2X2P-2.54-REVERSE")
      (libsource (lib "eagle-import") (part "CONNECTOR-HEADER-2X2P2X2P-2.54-REVERSE"))
    )
    (comp (ref "J109")
      (value "CONNECTOR-HEADER-2X2P2X2P-2.54-REVERSE")
      (footprint "eagle-import:2X2P-2.54-REVERSE")
      (libsource (lib "eagle-import") (part "CONNECTOR-HEADER-2X2P2X2P-2.54-REVERSE"))
    )
    (comp (ref "J110")
      (value "CONNECTOR-HEADER-2X2P2X2P-2.54-REVERSE")
      (footprint "eagle-import:2X2P-2.54-REVERSE")
      (libsource (lib "eagle-import") (part "CONNECTOR-HEADER-2X2P2X2P-2.54-REVERSE"))
    )
    (comp (ref "J111")
      (value "CONNECTOR-HEADER-2X2P2X2P-2.54-REVERSE")
      (footprint "eagle-import:2X2P-2.54-REVERSE")
      (libsource (lib "eagle-import") (part "CONNECTOR-HEADER-2X2P2X2P-2.54-REVERSE"))
    )
    (comp (ref "J112")
      (value "CONNECTOR-HEADER-2X2P2X2P-2.54-REVERSE")
      (footprint "eagle-import:2X2P-2.54-REVERSE")
      (libsource (lib "eagle-import") (part "CONNECTOR-HEADER-2X2P2X2P-2.54-REVERSE"))
    )
    (comp (ref "J113")
      (value "CONNECTOR-HEADER-2X2P2X2P-2.54-REVERSE")
      (footprint "eagle-import:2X2P-2.54-REVERSE")
      (libsource (lib "eagle-import") (part "CONNECTOR-HEADER-2X2P2X2P-2.54-REVERSE"))
    )
    (comp (ref "J114")
      (value "CONNECTOR-HEADER-2X2P2X2P-2.54-REVERSE")
      (footprint "eagle-import:2X2P-2.54-REVERSE")
      (libsource (lib "eagle-import") (part "CONNECTOR-HEADER-2X2P2X2P-2.54-REVERSE"))
    )
    (comp (ref "J115")
      (value "CONNECTOR-HEADER-2X2P2X2P-2.54-REVERSE")
      (footprint "eagle-import:2X2P-2.54-REVERSE")
      (libsource (lib "eagle-import") (part "CONNECTOR-HEADER-2X2P2X2P-2.54-REVERSE"))
    )
    (comp (ref "J116")
      (value "CONNECTOR-HEADER-2X2P2X2P-2.54-REVERSE")
      (footprint "eagle-import:2X2P-2.54-REVERSE")
      (libsource (lib "eagle-import") (part "CONNECTOR-HEADER-2X2P2X2P-2.54-REVERSE"))
    )
    (comp (ref "J117")
      (value "CONNECTOR-HEADER-2X2P2X2P-2.54-REVERSE")
      (footprint "eagle-import:2X2P-2.54-REVERSE")
      (libsource (lib "eagle-import") (part "CONNECTOR-HEADER-2X2P2X2P-2.54-REVERSE"))
    )
    (comp (ref "J118")
      (value "CONNECTOR-HEADER-2X2P2X2P-2.54-REVERSE")
      (footprint "eagle-import:2X2P-2.54-REVERSE")
      (libsource (lib "eagle-import") (part "CONNECTOR-HEADER-2X2P2X2P-2.54-REVERSE"))
    )
    (comp (ref "J119")
      (value "CONNECTOR-HEADER-2X2P2X2P-2.54-REVERSE")
      (footprint "eagle-import:2X2P-2.54-REVERSE")
      (libsource (lib "eagle-import") (part "CONNECTOR-HEADER-2X2P2X2P-2.54-REVERSE"))
    )
    (comp (ref "J120")
      (value "CONNECTOR-HEADER-2X2P2X2P-2.54-REVERSE")
      (footprint "eagle-import:2X2P-2.54-REVERSE")
      (libsource (lib "eagle-import") (part "CONNECTOR-HEADER-2X2P2X2P-2.54-REVERSE"))
    )
    (comp (ref "J121")
      (value "CONNECTOR-HEADER-2X2P2X2P-2.54-REVERSE")
      (footprint "eagle-import:2X2P-2.54-REVERSE")
      (libsource (lib "eagle-import") (part "CONNECTOR-HEADER-2X2P2X2P-2.54-REVERSE"))
    )
    (comp (ref "J122")
      (value "CONNECTOR-HEADER-2X2P2X2P-2.54-REVERSE")
      (footprint "eagle-import:2X2P-2.54-REVERSE")
      (libsource (lib "eagle-import") (part "CONNECTOR-HEADER-2X2P2X2P-2.54-REVERSE"))
    )
    (comp (ref "J123")
      (value "CONNECTOR-HEADER-2X2P2X2P-2.54-REVERSE")
      (footprint "eagle-import:2X2P-2.54-REVERSE")
      (libsource (lib "eagle-import") (part "CONNECTOR-HEADER-2X2P2X2P-2.54-REVERSE"))
    )
    (comp (ref "J124")
      (value "CONNECTOR-HEADER-2X2P2X2P-2.54-REVERSE")
      (footprint "eagle-import:2X2P-2.54-REVERSE")
      (libsource (lib "eagle-import") (part "CONNECTOR-HEADER-2X2P2X2P-2.54-REVERSE"))
    )
    (comp (ref "J125")
      (value "CONNECTOR-HEADER-2X2P2X2P-2.54-REVERSE")
      (footprint "eagle-import:2X2P-2.54-REVERSE")
      (libsource (lib "eagle-import") (part "CONNECTOR-HEADER-2X2P2X2P-2.54-REVERSE"))
    )
    (comp (ref "J126")
      (value "CONNECTOR-HEADER-2X2P2X2P-2.54-REVERSE")
      (footprint "eagle-import:2X2P-2.54-REVERSE")
      (libsource (lib "eagle-import") (part "CONNECTOR-HEADER-2X2P2X2P-2.54-REVERSE"))
    )
    (comp (ref "J127")
      (value "CONNECTOR-HEADER-2X2P2X2P-2.54-REVERSE")
      (footprint "eagle-import:2X2P-2.54-REVERSE")
      (libsource (lib "eagle-import") (part "CONNECTOR-HEADER-2X2P2X2P-2.54-REVERSE"))
    )
    (comp (ref "J128")
      (value "CONNECTOR-HEADER-2X2P2X2P-2.54-REVERSE")
      (footprint "eagle-import:2X2P-2.54-REVERSE")
      (libsource (lib "eagle-import") (part "CONNECTOR-HEADER-2X2P2X2P-2.54-REVERSE"))
    )
    (comp (ref "J129")
      (value "CONNECTOR-HEADER-2X2P2X2P-2.54-REVERSE")
      (footprint "eagle-import:2X2P-2.54-REVERSE")
      (libsource (lib "eagle-import") (part "CONNECTOR-HEADER-2X2P2X2P-2.54-REVERSE"))
    )
    (comp (ref "J130")
      (value "CONNECTOR-HEADER-2X2P2X2P-2.54-REVERSE")
      (footprint "eagle-import:2X2P-2.54-REVERSE")
      (libsource (lib "eagle-import") (part "CONNECTOR-HEADER-2X2P2X2P-2.54-REVERSE"))
    )
    (comp (ref "J131")
      (value "CONNECTOR-HEADER-2X2P2X2P-2.54-REVERSE")
      (footprint "eagle-import:2X2P-2.54-REVERSE")
      (libsource (lib "eagle-import") (part "CONNECTOR-HEADER-2X2P2X2P-2.54-REVERSE"))
    )
    (comp (ref "J132")
      (value "CONNECTOR-HEADER-2X2P2X2P-2.54-REVERSE")
      (footprint "eagle-import:2X2P-2.54-REVERSE")
      (libsource (lib "eagle-import") (part "CONNECTOR-HEADER-2X2P2X2P-2.54-REVERSE"))
    )
    (comp (ref "J133")
      (value "CONNECTOR-HEADER-2X2P2X2P-2.54-REVERSE")
      (footprint "eagle-import:2X2P-2.54-REVERSE")
      (libsource (lib "eagle-import") (part "CONNECTOR-HEADER-2X2P2X2P-2.54-REVERSE"))
    )
    (comp (ref "J134")
      (value "CONNECTOR-HEADER-2X2P2X2P-2.54-REVERSE")
      (footprint "eagle-import:2X2P-2.54-REVERSE")
      (libsource (lib "eagle-import") (part "CONNECTOR-HEADER-2X2P2X2P-2.54-REVERSE"))
    )
    (comp (ref "J135")
      (value "CONNECTOR-HEADER-2X2P2X2P-2.54-REVERSE")
      (footprint "eagle-import:2X2P-2.54-REVERSE")
      (libsource (lib "eagle-import") (part "CONNECTOR-HEADER-2X2P2X2P-2.54-REVERSE"))
    )
    (comp (ref "J136")
      (value "CONNECTOR-HEADER-2X2P2X2P-2.54-REVERSE")
      (footprint "eagle-import:2X2P-2.54-REVERSE")
      (libsource (lib "eagle-import") (part "CONNECTOR-HEADER-2X2P2X2P-2.54-REVERSE"))
    )
    (comp (ref "J137")
      (value "CONNECTOR-HEADER-2X2P2X2P-2.54-REVERSE")
      (footprint "eagle-import:2X2P-2.54-REVERSE")
      (libsource (lib "eagle-import") (part "CONNECTOR-HEADER-2X2P2X2P-2.54-REVERSE"))
    )
    (comp (ref "J138")
      (value "CONNECTOR-HEADER-2X2P2X2P-2.54-REVERSE")
      (footprint "eagle-import:2X2P-2.54-REVERSE")
      (libsource (lib "eagle-import") (part "CONNECTOR-HEADER-2X2P2X2P-2.54-REVERSE"))
    )
    (comp (ref "J139")
      (value "CONNECTOR-HEADER-2X2P2X2P-2.54-REVERSE")
      (footprint "eagle-import:2X2P-2.54-REVERSE")
      (libsource (lib "eagle-import") (part "CONNECTOR-HEADER-2X2P2X2P-2.54-REVERSE"))
    )
    (comp (ref "J140")
      (value "CONNECTOR-HEADER-2X2P2X2P-2.54-REVERSE")
      (footprint "eagle-import:2X2P-2.54-REVERSE")
      (libsource (lib "eagle-import") (part "CONNECTOR-HEADER-2X2P2X2P-2.54-REVERSE"))
    )
    (comp (ref "J141")
      (value "CONNECTOR-HEADER-2X2P2X2P-2.54-REVERSE")
      (footprint "eagle-import:2X2P-2.54-REVERSE")
      (libsource (lib "eagle-import") (part "CONNECTOR-HEADER-2X2P2X2P-2.54-REVERSE"))
    )
    (comp (ref "J142")
      (value "CONNECTOR-HEADER-2X2P2X2P-2.54-REVERSE")
      (footprint "eagle-import:2X2P-2.54-REVERSE")
      (libsource (lib "eagle-import") (part "CONNECTOR-HEADER-2X2P2X2P-2.54-REVERSE"))
    )
    (comp (ref "J143")
      (value "CONNECTOR-HEADER-2X2P2X2P-2.54-REVERSE")
      (footprint "eagle-import:2X2P-2.54-REVERSE")
      (libsource (lib "eagle-import") (part "CONNECTOR-HEADER-2X2P2X2P-2.54-REVERSE"))
    )
    (comp (ref "J144")
      (value "CONNECTOR-HEADER-2X2P2X2P-2.54-REVERSE")
      (footprint "eagle-import:2X2P-2.54-REVERSE")
      (libsource (lib "eagle-import") (part "CONNECTOR-HEADER-2X2P2X2P-2.54-REVERSE"))
    )
    (comp (ref "J145")
      (value "CONNECTOR-HEADER-2X2P2X2P-2.54-REVERSE")
      (footprint "eagle-import:2X2P-2.54-REVERSE")
      (libsource (lib "eagle-import") (part "CONNECTOR-HEADER-2X2P2X2P-2.54-REVERSE"))
    )
    (comp (ref "J146")
      (value "CONNECTOR-HEADER-2X2P2X2P-2.54-REVERSE")
      (footprint "eagle-import:2X2P-2.54-REVERSE")
      (libsource (lib "eagle-import") (part "CONNECTOR-HEADER-2X2P2X2P-2.54-REVERSE"))
    )
    (comp (ref "J147")
      (value "CONNECTOR-HEADER-2X2P2X2P-2.54-REVERSE")
      (footprint "eagle-import:2X2P-2.54-REVERSE")
      (libsource (lib "eagle-import") (part "CONNECTOR-HEADER-2X2P2X2P-2.54-REVERSE"))
    )
    (comp (ref "J148")
      (value "CONNECTOR-HEADER-2X2P2X2P-2.54-REVERSE")
      (footprint "eagle-import:2X2P-2.54-REVERSE")
      (libsource (lib "eagle-import") (part "CONNECTOR-HEADER-2X2P2X2P-2.54-REVERSE"))
    )
    (comp (ref "J149")
      (value "CONNECTOR-HEADER-2X2P2X2P-2.54-REVERSE")
      (footprint "eagle-import:2X2P-2.54-REVERSE")
      (libsource (lib "eagle-import") (part "CONNECTOR-HEADER-2X2P2X2P-2.54-REVERSE"))
    )
    (comp (ref "J150")
      (value "CONNECTOR-HEADER-2X2P2X2P-2.54-REVERSE")
      (footprint "eagle-import:2X2P-2.54-REVERSE")
      (libsource (lib "eagle-import") (part "CONNECTOR-HEADER-2X2P2X2P-2.54-REVERSE"))
    )
    (comp (ref "J151")
      (value "CONNECTOR-HEADER-2X2P2X2P-2.54-REVERSE")
      (footprint "eagle-import:2X2P-2.54-REVERSE")
      (libsource (lib "eagle-import") (part "CONNECTOR-HEADER-2X2P2X2P-2.54-REVERSE"))
    )
    (comp (ref "J152")
      (value "CONNECTOR-HEADER-2X2P2X2P-2.54-REVERSE")
      (footprint "eagle-import:2X2P-2.54-REVERSE")
      (libsource (lib "eagle-import") (part "CONNECTOR-HEADER-2X2P2X2P-2.54-REVERSE"))
    )
    (comp (ref "J153")
      (value "CONNECTOR-HEADER-2X2P2X2P-2.54-REVERSE")
      (footprint "eagle-import:2X2P-2.54-REVERSE")
      (libsource (lib "eagle-import") (part "CONNECTOR-HEADER-2X2P2X2P-2.54-REVERSE"))
    )
    (comp (ref "J154")
      (value "CONNECTOR-HEADER-2X2P2X2P-2.54-REVERSE")
      (footprint "eagle-import:2X2P-2.54-REVERSE")
      (libsource (lib "eagle-import") (part "CONNECTOR-HEADER-2X2P2X2P-2.54-REVERSE"))
    )
    (comp (ref "J155")
      (value "CONNECTOR-HEADER-2X2P2X2P-2.54-REVERSE")
      (footprint "eagle-import:2X2P-2.54-REVERSE")
      (libsource (lib "eagle-import") (part "CONNECTOR-HEADER-2X2P2X2P-2.54-REVERSE"))
    )
    (comp (ref "J156")
      (value "CONNECTOR-HEADER-2X2P2X2P-2.54-REVERSE")
      (footprint "eagle-import:2X2P-2.54-REVERSE")
      (libsource (lib "eagle-import") (part "CONNECTOR-HEADER-2X2P2X2P-2.54-REVERSE"))
    )
    (comp (ref "J157")
      (value "CONNECTOR-HEADER-2X2P2X2P-2.54-REVERSE")
      (footprint "eagle-import:2X2P-2.54-REVERSE")
      (libsource (lib "eagle-import") (part "CONNECTOR-HEADER-2X2P2X2P-2.54-REVERSE"))
    )
    (comp (ref "J158")
      (value "CONNECTOR-HEADER-2X2P2X2P-2.54-REVERSE")
      (footprint "eagle-import:2X2P-2.54-REVERSE")
      (libsource (lib "eagle-import") (part "CONNECTOR-HEADER-2X2P2X2P-2.54-REVERSE"))
    )
    (comp (ref "J159")
      (value "CONNECTOR-HEADER-2X2P2X2P-2.54-REVERSE")
      (footprint "eagle-import:2X2P-2.54-REVERSE")
      (libsource (lib "eagle-import") (part "CONNECTOR-HEADER-2X2P2X2P-2.54-REVERSE"))
    )
    (comp (ref "J160")
      (value "CONNECTOR-HEADER-2X2P2X2P-2.54-REVERSE")
      (footprint "eagle-import:2X2P-2.54-REVERSE")
      (libsource (lib "eagle-import") (part "CONNECTOR-HEADER-2X2P2X2P-2.54-REVERSE"))
    )
    (comp (ref "J161")
      (value "CONNECTOR-HEADER-2X2P2X2P-2.54-REVERSE")
      (footprint "eagle-import:2X2P-2.54-REVERSE")
      (libsource (lib "eagle-import") (part "CONNECTOR-HEADER-2X2P2X2P-2.54-REVERSE"))
    )
    (comp (ref "J162")
      (value "CONNECTOR-HEADER-2X2P2X2P-2.54-REVERSE")
      (footprint "eagle-import:2X2P-2.54-REVERSE")
      (libsource (lib "eagle-import") (part "CONNECTOR-HEADER-2X2P2X2P-2.54-REVERSE"))
    )
    (comp (ref "J163")
      (value "CONNECTOR-HEADER-2X2P2X2P-2.54-REVERSE")
      (footprint "eagle-import:2X2P-2.54-REVERSE")
      (libsource (lib "eagle-import") (part "CONNECTOR-HEADER-2X2P2X2P-2.54-REVERSE"))
    )
    (comp (ref "J164")
      (value "CONNECTOR-HEADER-2X2P2X2P-2.54-REVERSE")
      (footprint "eagle-import:2X2P-2.54-REVERSE")
      (libsource (lib "eagle-import") (part "CONNECTOR-HEADER-2X2P2X2P-2.54-REVERSE"))
    )
    (comp (ref "J165")
      (value "CONNECTOR-HEADER-2X2P2X2P-2.54-REVERSE")
      (footprint "eagle-import:2X2P-2.54-REVERSE")
      (libsource (lib "eagle-import") (part "CONNECTOR-HEADER-2X2P2X2P-2.54-REVERSE"))
    )
    (comp (ref "J166")
      (value "CONNECTOR-HEADER-2X2P2X2P-2.54-REVERSE")
      (footprint "eagle-import:2X2P-2.54-REVERSE")
      (libsource (lib "eagle-import") (part "CONNECTOR-HEADER-2X2P2X2P-2.54-REVERSE"))
    )
    (comp (ref "J167")
      (value "CONNECTOR-HEADER-2X2P2X2P-2.54-REVERSE")
      (footprint "eagle-import:2X2P-2.54-REVERSE")
      (libsource (lib "eagle-import") (part "CONNECTOR-HEADER-2X2P2X2P-2.54-REVERSE"))
    )
    (comp (ref "J168")
      (value "CONNECTOR-HEADER-2X2P2X2P-2.54-REVERSE")
      (footprint "eagle-import:2X2P-2.54-REVERSE")
      (libsource (lib "eagle-import") (part "CONNECTOR-HEADER-2X2P2X2P-2.54-REVERSE"))
    )
    (comp (ref "J169")
      (value "CONNECTOR-HEADER-2X2P2X2P-2.54-REVERSE")
      (footprint "eagle-import:2X2P-2.54-REVERSE")
      (libsource (lib "eagle-import") (part "CONNECTOR-HEADER-2X2P2X2P-2.54-REVERSE"))
    )
    (comp (ref "J170")
      (value "CONNECTOR-HEADER-2X2P2X2P-2.54-REVERSE")
      (footprint "eagle-import:2X2P-2.54-REVERSE")
      (libsource (lib "eagle-import") (part "CONNECTOR-HEADER-2X2P2X2P-2.54-REVERSE"))
    )
    (comp (ref "J171")
      (value "CONNECTOR-HEADER-2X2P2X2P-2.54-REVERSE")
      (footprint "eagle-import:2X2P-2.54-REVERSE")
      (libsource (lib "eagle-import") (part "CONNECTOR-HEADER-2X2P2X2P-2.54-REVERSE"))
    )
    (comp (ref "J172")
      (value "CONNECTOR-HEADER-2X2P2X2P-2.54-REVERSE")
      (footprint "eagle-import:2X2P-2.54-REVERSE")
      (libsource (lib "eagle-import") (part "CONNECTOR-HEADER-2X2P2X2P-2.54-REVERSE"))
    )
    (comp (ref "J173")
      (value "CONNECTOR-HEADER-2X2P2X2P-2.54-REVERSE")
      (footprint "eagle-import:2X2P-2.54-REVERSE")
      (libsource (lib "eagle-import") (part "CONNECTOR-HEADER-2X2P2X2P-2.54-REVERSE"))
    )
    (comp (ref "J174")
      (value "CONNECTOR-HEADER-2X2P2X2P-2.54-REVERSE")
      (footprint "eagle-import:2X2P-2.54-REVERSE")
      (libsource (lib "eagle-import") (part "CONNECTOR-HEADER-2X2P2X2P-2.54-REVERSE"))
    )
    (comp (ref "J175")
      (value "CONNECTOR-HEADER-2X2P2X2P-2.54-REVERSE")
      (footprint "eagle-import:2X2P-2.54-REVERSE")
      (libsource (lib "eagle-import") (part "CONNECTOR-HEADER-2X2P2X2P-2.54-REVERSE"))
    )
    (comp (ref "J176")
      (value "CONNECTOR-HEADER-2X2P2X2P-2.54-REVERSE")
      (footprint "eagle-import:2X2P-2.54-REVERSE")
      (libsource (lib "eagle-import") (part "CONNECTOR-HEADER-2X2P2X2P-2.54-REVERSE"))
    )
    (comp (ref "J177")
      (value "CONNECTOR-HEADER-2X2P2X2P-2.54-REVERSE")
      (footprint "eagle-import:2X2P-2.54-REVERSE")
      (libsource (lib "eagle-import") (part "CONNECTOR-HEADER-2X2P2X2P-2.54-REVERSE"))
    )
    (comp (ref "J178")
      (value "CONNECTOR-HEADER-2X2P2X2P-2.54-REVERSE")
      (footprint "eagle-import:2X2P-2.54-REVERSE")
      (libsource (lib "eagle-import") (part "CONNECTOR-HEADER-2X2P2X2P-2.54-REVERSE"))
    )
    (comp (ref "J179")
      (value "CONNECTOR-HEADER-2X2P2X2P-2.54-REVERSE")
      (footprint "eagle-import:2X2P-2.54-REVERSE")
      (libsource (lib "eagle-import") (part "CONNECTOR-HEADER-2X2P2X2P-2.54-REVERSE"))
    )
    (comp (ref "J180")
      (value "CONNECTOR-HEADER-2X2P2X2P-2.54-REVERSE")
      (footprint "eagle-import:2X2P-2.54-REVERSE")
      (libsource (lib "eagle-import") (part "CONNECTOR-HEADER-2X2P2X2P-2.54-REVERSE"))
    )
    (comp (ref "J181")
      (value "CONNECTOR-HEADER-2X2P2X2P-2.54-REVERSE")
      (footprint "eagle-import:2X2P-2.54-REVERSE")
      (libsource (lib "eagle-import") (part "CONNECTOR-HEADER-2X2P2X2P-2.54-REVERSE"))
    )
    (comp (ref "J182")
      (value "CONNECTOR-HEADER-2X2P2X2P-2.54-REVERSE")
      (footprint "eagle-import:2X2P-2.54-REVERSE")
      (libsource (lib "eagle-import") (part "CONNECTOR-HEADER-2X2P2X2P-2.54-REVERSE"))
    )
    (comp (ref "J183")
      (value "CONNECTOR-HEADER-2X2P2X2P-2.54-REVERSE")
      (footprint "eagle-import:2X2P-2.54-REVERSE")
      (libsource (lib "eagle-import") (part "CONNECTOR-HEADER-2X2P2X2P-2.54-REVERSE"))
    )
    (comp (ref "J184")
      (value "CONNECTOR-HEADER-2X2P2X2P-2.54-REVERSE")
      (footprint "eagle-import:2X2P-2.54-REVERSE")
      (libsource (lib "eagle-import") (part "CONNECTOR-HEADER-2X2P2X2P-2.54-REVERSE"))
    )
    (comp (ref "J185")
      (value "CONNECTOR-HEADER-2X2P2X2P-2.54-REVERSE")
      (footprint "eagle-import:2X2P-2.54-REVERSE")
      (libsource (lib "eagle-import") (part "CONNECTOR-HEADER-2X2P2X2P-2.54-REVERSE"))
    )
    (comp (ref "J186")
      (value "CONNECTOR-HEADER-2X2P2X2P-2.54-REVERSE")
      (footprint "eagle-import:2X2P-2.54-REVERSE")
      (libsource (lib "eagle-import") (part "CONNECTOR-HEADER-2X2P2X2P-2.54-REVERSE"))
    )
    (comp (ref "J187")
      (value "CONNECTOR-HEADER-2X2P2X2P-2.54-REVERSE")
      (footprint "eagle-import:2X2P-2.54-REVERSE")
      (libsource (lib "eagle-import") (part "CONNECTOR-HEADER-2X2P2X2P-2.54-REVERSE"))
    )
    (comp (ref "J188")
      (value "CONNECTOR-HEADER-2X2P2X2P-2.54-REVERSE")
      (footprint "eagle-import:2X2P-2.54-REVERSE")
      (libsource (lib "eagle-import") (part "CONNECTOR-HEADER-2X2P2X2P-2.54-REVERSE"))
    )
    (comp (ref "J189")
      (value "CONNECTOR-HEADER-2X2P2X2P-2.54-REVERSE")
      (footprint "eagle-import:2X2P-2.54-REVERSE")
      (libsource (lib "eagle-import") (part "CONNECTOR-HEADER-2X2P2X2P-2.54-REVERSE"))
    )
    (comp (ref "J190")
      (value "CONNECTOR-HEADER-2X2P2X2P-2.54-REVERSE")
      (footprint "eagle-import:2X2P-2.54-REVERSE")
      (libsource (lib "eagle-import") (part "CONNECTOR-HEADER-2X2P2X2P-2.54-REVERSE"))
    )
    (comp (ref "J191")
      (value "CONNECTOR-HEADER-2X2P2X2P-2.54-REVERSE")
      (footprint "eagle-import:2X2P-2.54-REVERSE")
      (libsource (lib "eagle-import") (part "CONNECTOR-HEADER-2X2P2X2P-2.54-REVERSE"))
    )
    (comp (ref "J192")
      (value "CONNECTOR-HEADER-2X2P2X2P-2.54-REVERSE")
      (footprint "eagle-import:2X2P-2.54-REVERSE")
      (libsource (lib "eagle-import") (part "CONNECTOR-HEADER-2X2P2X2P-2.54-REVERSE"))
    )
    (comp (ref "J193")
      (value "CONNECTOR-HEADER-2X2P2X2P-2.54-REVERSE")
      (footprint "eagle-import:2X2P-2.54-REVERSE")
      (libsource (lib "eagle-import") (part "CONNECTOR-HEADER-2X2P2X2P-2.54-REVERSE"))
    )
    (comp (ref "J194")
      (value "CONNECTOR-HEADER-2X2P2X2P-2.54-REVERSE")
      (footprint "eagle-import:2X2P-2.54-REVERSE")
      (libsource (lib "eagle-import") (part "CONNECTOR-HEADER-2X2P2X2P-2.54-REVERSE"))
    )
    (comp (ref "J195")
      (value "CONNECTOR-HEADER-2X2P2X2P-2.54-REVERSE")
      (footprint "eagle-import:2X2P-2.54-REVERSE")
      (libsource (lib "eagle-import") (part "CONNECTOR-HEADER-2X2P2X2P-2.54-REVERSE"))
    )
    (comp (ref "J196")
      (value "CONNECTOR-HEADER-2X2P2X2P-2.54-REVERSE")
      (footprint "eagle-import:2X2P-2.54-REVERSE")
      (libsource (lib "eagle-import") (part "CONNECTOR-HEADER-2X2P2X2P-2.54-REVERSE"))
    )
    (comp (ref "J197")
      (value "CONNECTOR-HEADER-2X2P2X2P-2.54-REVERSE")
      (footprint "eagle-import:2X2P-2.54-REVERSE")
      (libsource (lib "eagle-import") (part "CONNECTOR-HEADER-2X2P2X2P-2.54-REVERSE"))
    )
    (comp (ref "J198")
      (value "CONNECTOR-HEADER-2X2P2X2P-2.54-REVERSE")
      (footprint "eagle-import:2X2P-2.54-REVERSE")
      (libsource (lib "eagle-import") (part "CONNECTOR-HEADER-2X2P2X2P-2.54-REVERSE"))
    )
    (comp (ref "J199")
      (value "CONNECTOR-HEADER-2X2P2X2P-2.54-REVERSE")
      (footprint "eagle-import:2X2P-2.54-REVERSE")
      (libsource (lib "eagle-import") (part "CONNECTOR-HEADER-2X2P2X2P-2.54-REVERSE"))
    )
    (comp (ref "J200")
      (value "CONNECTOR-HEADER-2X2P2X2P-2.54-REVERSE")
      (footprint "eagle-import:2X2P-2.54-REVERSE")
      (libsource (lib "eagle-import") (part "CONNECTOR-HEADER-2X2P2X2P-2.54-REVERSE"))
    )
    (comp (ref "J201")
      (value "CONNECTOR-HEADER-2X2P2X2P-2.54-REVERSE")
      (footprint "eagle-import:2X2P-2.54-REVERSE")
      (libsource (lib "eagle-import") (part "CONNECTOR-HEADER-2X2P2X2P-2.54-REVERSE"))
    )
    (comp (ref "J202")
      (value "CONNECTOR-HEADER-2X2P2X2P-2.54-REVERSE")
      (footprint "eagle-import:2X2P-2.54-REVERSE")
      (libsource (lib "eagle-import") (part "CONNECTOR-HEADER-2X2P2X2P-2.54-REVERSE"))
    )
    (comp (ref "J203")
      (value "CONNECTOR-HEADER-2X2P2X2P-2.54-REVERSE")
      (footprint "eagle-import:2X2P-2.54-REVERSE")
      (libsource (lib "eagle-import") (part "CONNECTOR-HEADER-2X2P2X2P-2.54-REVERSE"))
    )
    (comp (ref "J204")
      (value "CONNECTOR-HEADER-2X2P2X2P-2.54-REVERSE")
      (footprint "eagle-import:2X2P-2.54-REVERSE")
      (libsource (lib "eagle-import") (part "CONNECTOR-HEADER-2X2P2X2P-2.54-REVERSE"))
    )
    (comp (ref "J205")
      (value "CONNECTOR-HEADER-2X2P2X2P-2.54-REVERSE")
      (footprint "eagle-import:2X2P-2.54-REVERSE")
      (libsource (lib "eagle-import") (part "CONNECTOR-HEADER-2X2P2X2P-2.54-REVERSE"))
    )
    (comp (ref "J206")
      (value "CONNECTOR-HEADER-2X2P2X2P-2.54-REVERSE")
      (footprint "eagle-import:2X2P-2.54-REVERSE")
      (libsource (lib "eagle-import") (part "CONNECTOR-HEADER-2X2P2X2P-2.54-REVERSE"))
    )
    (comp (ref "J207")
      (value "CONNECTOR-HEADER-2X2P2X2P-2.54-REVERSE")
      (footprint "eagle-import:2X2P-2.54-REVERSE")
      (libsource (lib "eagle-import") (part "CONNECTOR-HEADER-2X2P2X2P-2.54-REVERSE"))
    )
    (comp (ref "J208")
      (value "CONNECTOR-HEADER-2X2P2X2P-2.54-REVERSE")
      (footprint "eagle-import:2X2P-2.54-REVERSE")
      (libsource (lib "eagle-import") (part "CONNECTOR-HEADER-2X2P2X2P-2.54-REVERSE"))
    )
    (comp (ref "J209")
      (value "CONNECTOR-HEADER-2X2P2X2P-2.54-REVERSE")
      (footprint "eagle-import:2X2P-2.54-REVERSE")
      (libsource (lib "eagle-import") (part "CONNECTOR-HEADER-2X2P2X2P-2.54-REVERSE"))
    )
    (comp (ref "J210")
      (value "CONNECTOR-HEADER-2X2P2X2P-2.54-REVERSE")
      (footprint "eagle-import:2X2P-2.54-REVERSE")
      (libsource (lib "eagle-import") (part "CONNECTOR-HEADER-2X2P2X2P-2.54-REVERSE"))
    )
    (comp (ref "J211")
      (value "CONNECTOR-HEADER-2X2P2X2P-2.54-REVERSE")
      (footprint "eagle-import:2X2P-2.54-REVERSE")
      (libsource (lib "eagle-import") (part "CONNECTOR-HEADER-2X2P2X2P-2.54-REVERSE"))
    )
    (comp (ref "J212")
      (value "CONNECTOR-HEADER-2X2P2X2P-2.54-REVERSE")
      (footprint "eagle-import:2X2P-2.54-REVERSE")
      (libsource (lib "eagle-import") (part "CONNECTOR-HEADER-2X2P2X2P-2.54-REVERSE"))
    )
    (comp (ref "J213")
      (value "CONNECTOR-HEADER-2X2P2X2P-2.54-REVERSE")
      (footprint "eagle-import:2X2P-2.54-REVERSE")
      (libsource (lib "eagle-import") (part "CONNECTOR-HEADER-2X2P2X2P-2.54-REVERSE"))
    )
    (comp (ref "J214")
      (value "CONNECTOR-HEADER-2X2P2X2P-2.54-REVERSE")
      (footprint "eagle-import:2X2P-2.54-REVERSE")
      (libsource (lib "eagle-import") (part "CONNECTOR-HEADER-2X2P2X2P-2.54-REVERSE"))
    )
    (comp (ref "J215")
      (value "CONNECTOR-HEADER-2X2P2X2P-2.54-REVERSE")
      (footprint "eagle-import:2X2P-2.54-REVERSE")
      (libsource (lib "eagle-import") (part "CONNECTOR-HEADER-2X2P2X2P-2.54-REVERSE"))
    )
    (comp (ref "J216")
      (value "CONNECTOR-HEADER-2X2P2X2P-2.54-REVERSE")
      (footprint "eagle-import:2X2P-2.54-REVERSE")
      (libsource (lib "eagle-import") (part "CONNECTOR-HEADER-2X2P2X2P-2.54-REVERSE"))
    )
    (comp (ref "J217")
      (value "CONNECTOR-HEADER-2X2P2X2P-2.54-REVERSE")
      (footprint "eagle-import:2X2P-2.54-REVERSE")
      (libsource (lib "eagle-import") (part "CONNECTOR-HEADER-2X2P2X2P-2.54-REVERSE"))
    )
    (comp (ref "J218")
      (value "CONNECTOR-HEADER-2X2P2X2P-2.54-REVERSE")
      (footprint "eagle-import:2X2P-2.54-REVERSE")
      (libsource (lib "eagle-import") (part "CONNECTOR-HEADER-2X2P2X2P-2.54-REVERSE"))
    )
    (comp (ref "J219")
      (value "CONNECTOR-HEADER-2X2P2X2P-2.54-REVERSE")
      (footprint "eagle-import:2X2P-2.54-REVERSE")
      (libsource (lib "eagle-import") (part "CONNECTOR-HEADER-2X2P2X2P-2.54-REVERSE"))
    )
    (comp (ref "J220")
      (value "CONNECTOR-HEADER-2X2P2X2P-2.54-REVERSE")
      (footprint "eagle-import:2X2P-2.54-REVERSE")
      (libsource (lib "eagle-import") (part "CONNECTOR-HEADER-2X2P2X2P-2.54-REVERSE"))
    )
    (comp (ref "J221")
      (value "CONNECTOR-HEADER-2X2P2X2P-2.54-REVERSE")
      (footprint "eagle-import:2X2P-2.54-REVERSE")
      (libsource (lib "eagle-import") (part "CONNECTOR-HEADER-2X2P2X2P-2.54-REVERSE"))
    )
    (comp (ref "J222")
      (value "CONNECTOR-HEADER-2X2P2X2P-2.54-REVERSE")
      (footprint "eagle-import:2X2P-2.54-REVERSE")
      (libsource (lib "eagle-import") (part "CONNECTOR-HEADER-2X2P2X2P-2.54-REVERSE"))
    )
    (comp (ref "J223")
      (value "CONNECTOR-HEADER-2X2P2X2P-2.54-REVERSE")
      (footprint "eagle-import:2X2P-2.54-REVERSE")
      (libsource (lib "eagle-import") (part "CONNECTOR-HEADER-2X2P2X2P-2.54-REVERSE"))
    )
    (comp (ref "J224")
      (value "CONNECTOR-HEADER-2X2P2X2P-2.54-REVERSE")
      (footprint "eagle-import:2X2P-2.54-REVERSE")
      (libsource (lib "eagle-import") (part "CONNECTOR-HEADER-2X2P2X2P-2.54-REVERSE"))
    )
    (comp (ref "J225")
      (value "CONNECTOR-HEADER-2X2P2X2P-2.54-REVERSE")
      (footprint "eagle-import:2X2P-2.54-REVERSE")
      (libsource (lib "eagle-import") (part "CONNECTOR-HEADER-2X2P2X2P-2.54-REVERSE"))
    )
    (comp (ref "J226")
      (value "CONNECTOR-HEADER-2X2P2X2P-2.54-REVERSE")
      (footprint "eagle-import:2X2P-2.54-REVERSE")
      (libsource (lib "eagle-import") (part "CONNECTOR-HEADER-2X2P2X2P-2.54-REVERSE"))
    )
    (comp (ref "J227")
      (value "CONNECTOR-HEADER-2X2P2X2P-2.54-REVERSE")
      (footprint "eagle-import:2X2P-2.54-REVERSE")
      (libsource (lib "eagle-import") (part "CONNECTOR-HEADER-2X2P2X2P-2.54-REVERSE"))
    )
    (comp (ref "J228")
      (value "CONNECTOR-HEADER-2X2P2X2P-2.54-REVERSE")
      (footprint "eagle-import:2X2P-2.54-REVERSE")
      (libsource (lib "eagle-import") (part "CONNECTOR-HEADER-2X2P2X2P-2.54-REVERSE"))
    )
    (comp (ref "J229")
      (value "CONNECTOR-HEADER-2X2P2X2P-2.54-REVERSE")
      (footprint "eagle-import:2X2P-2.54-REVERSE")
      (libsource (lib "eagle-import") (part "CONNECTOR-HEADER-2X2P2X2P-2.54-REVERSE"))
    )
    (comp (ref "J230")
      (value "CONNECTOR-HEADER-2X2P2X2P-2.54-REVERSE")
      (footprint "eagle-import:2X2P-2.54-REVERSE")
      (libsource (lib "eagle-import") (part "CONNECTOR-HEADER-2X2P2X2P-2.54-REVERSE"))
    )
    (comp (ref "J231")
      (value "CONNECTOR-HEADER-2X2P2X2P-2.54-REVERSE")
      (footprint "eagle-import:2X2P-2.54-REVERSE")
      (libsource (lib "eagle-import") (part "CONNECTOR-HEADER-2X2P2X2P-2.54-REVERSE"))
    )
    (comp (ref "J232")
      (value "CONNECTOR-HEADER-2X2P2X2P-2.54-REVERSE")
      (footprint "eagle-import:2X2P-2.54-REVERSE")
      (libsource (lib "eagle-import") (part "CONNECTOR-HEADER-2X2P2X2P-2.54-REVERSE"))
    )
    (comp (ref "J233")
      (value "CONNECTOR-HEADER-2X2P2X2P-2.54-REVERSE")
      (footprint "eagle-import:2X2P-2.54-REVERSE")
      (libsource (lib "eagle-import") (part "CONNECTOR-HEADER-2X2P2X2P-2.54-REVERSE"))
    )
    (comp (ref "J234")
      (value "CONNECTOR-HEADER-2X2P2X2P-2.54-REVERSE")
      (footprint "eagle-import:2X2P-2.54-REVERSE")
      (libsource (lib "eagle-import") (part "CONNECTOR-HEADER-2X2P2X2P-2.54-REVERSE"))
    )
    (comp (ref "J235")
      (value "CONNECTOR-HEADER-2X2P2X2P-2.54-REVERSE")
      (footprint "eagle-import:2X2P-2.54-REVERSE")
      (libsource (lib "eagle-import") (part "CONNECTOR-HEADER-2X2P2X2P-2.54-REVERSE"))
    )
    (comp (ref "J236")
      (value "CONNECTOR-HEADER-2X2P2X2P-2.54-REVERSE")
      (footprint "eagle-import:2X2P-2.54-REVERSE")
      (libsource (lib "eagle-import") (part "CONNECTOR-HEADER-2X2P2X2P-2.54-REVERSE"))
    )
    (comp (ref "J237")
      (value "CONNECTOR-HEADER-2X2P2X2P-2.54-REVERSE")
      (footprint "eagle-import:2X2P-2.54-REVERSE")
      (libsource (lib "eagle-import") (part "CONNECTOR-HEADER-2X2P2X2P-2.54-REVERSE"))
    )
    (comp (ref "J238")
      (value "CONNECTOR-HEADER-2X2P2X2P-2.54-REVERSE")
      (footprint "eagle-import:2X2P-2.54-REVERSE")
      (libsource (lib "eagle-import") (part "CONNECTOR-HEADER-2X2P2X2P-2.54-REVERSE"))
    )
    (comp (ref "J239")
      (value "CONNECTOR-HEADER-2X2P2X2P-2.54-REVERSE")
      (footprint "eagle-import:2X2P-2.54-REVERSE")
      (libsource (lib "eagle-import") (part "CONNECTOR-HEADER-2X2P2X2P-2.54-REVERSE"))
    )
    (comp (ref "J240")
      (value "CONNECTOR-HEADER-2X2P2X2P-2.54-REVERSE")
      (footprint "eagle-import:2X2P-2.54-REVERSE")
      (libsource (lib "eagle-import") (part "CONNECTOR-HEADER-2X2P2X2P-2.54-REVERSE"))
    )
    (comp (ref "J241")
      (value "CONNECTOR-HEADER-2X2P2X2P-2.54-REVERSE")
      (footprint "eagle-import:2X2P-2.54-REVERSE")
      (libsource (lib "eagle-import") (part "CONNECTOR-HEADER-2X2P2X2P-2.54-REVERSE"))
    )
    (comp (ref "J242")
      (value "CONNECTOR-HEADER-2X2P2X2P-2.54-REVERSE")
      (footprint "eagle-import:2X2P-2.54-REVERSE")
      (libsource (lib "eagle-import") (part "CONNECTOR-HEADER-2X2P2X2P-2.54-REVERSE"))
    )
    (comp (ref "J243")
      (value "CONNECTOR-HEADER-2X2P2X2P-2.54-REVERSE")
      (footprint "eagle-import:2X2P-2.54-REVERSE")
      (libsource (lib "eagle-import") (part "CONNECTOR-HEADER-2X2P2X2P-2.54-REVERSE"))
    )
    (comp (ref "J244")
      (value "CONNECTOR-HEADER-2X2P2X2P-2.54-REVERSE")
      (footprint "eagle-import:2X2P-2.54-REVERSE")
      (libsource (lib "eagle-import") (part "CONNECTOR-HEADER-2X2P2X2P-2.54-REVERSE"))
    )
    (comp (ref "J245")
      (value "CONNECTOR-HEADER-2X2P2X2P-2.54-REVERSE")
      (footprint "eagle-import:2X2P-2.54-REVERSE")
      (libsource (lib "eagle-import") (part "CONNECTOR-HEADER-2X2P2X2P-2.54-REVERSE"))
    )
    (comp (ref "J246")
      (value "CONNECTOR-HEADER-2X2P2X2P-2.54-REVERSE")
      (footprint "eagle-import:2X2P-2.54-REVERSE")
      (libsource (lib "eagle-import") (part "CONNECTOR-HEADER-2X2P2X2P-2.54-REVERSE"))
    )
    (comp (ref "J247")
      (value "CONNECTOR-HEADER-2X2P2X2P-2.54-REVERSE")
      (footprint "eagle-import:2X2P-2.54-REVERSE")
      (libsource (lib "eagle-import") (part "CONNECTOR-HEADER-2X2P2X2P-2.54-REVERSE"))
    )
    (comp (ref "J248")
      (value "CONNECTOR-HEADER-2X2P2X2P-2.54-REVERSE")
      (footprint "eagle-import:2X2P-2.54-REVERSE")
      (libsource (lib "eagle-import") (part "CONNECTOR-HEADER-2X2P2X2P-2.54-REVERSE"))
    )
    (comp (ref "J249")
      (value "CONNECTOR-HEADER-2X2P2X2P-2.54-REVERSE")
      (footprint "eagle-import:2X2P-2.54-REVERSE")
      (libsource (lib "eagle-import") (part "CONNECTOR-HEADER-2X2P2X2P-2.54-REVERSE"))
    )
    (comp (ref "J250")
      (value "CONNECTOR-HEADER-2X2P2X2P-2.54-REVERSE")
      (footprint "eagle-import:2X2P-2.54-REVERSE")
      (libsource (lib "eagle-import") (part "CONNECTOR-HEADER-2X2P2X2P-2.54-REVERSE"))
    )
    (comp (ref "J251")
      (value "CONNECTOR-HEADER-2X2P2X2P-2.54-REVERSE")
      (footprint "eagle-import:2X2P-2.54-REVERSE")
      (libsource (lib "eagle-import") (part "CONNECTOR-HEADER-2X2P2X2P-2.54-REVERSE"))
    )
    (comp (ref "J252")
      (value "CONNECTOR-HEADER-2X2P2X2P-2.54-REVERSE")
      (footprint "eagle-import:2X2P-2.54-REVERSE")
      (libsource (lib "eagle-import") (part "CONNECTOR-HEADER-2X2P2X2P-2.54-REVERSE"))
    )
    (comp (ref "J253")
      (value "CONNECTOR-HEADER-2X2P2X2P-2.54-REVERSE")
      (footprint "eagle-import:2X2P-2.54-REVERSE")
      (libsource (lib "eagle-import") (part "CONNECTOR-HEADER-2X2P2X2P-2.54-REVERSE"))
    )
    (comp (ref "J254")
      (value "CONNECTOR-HEADER-2X2P2X2P-2.54-REVERSE")
      (footprint "eagle-import:2X2P-2.54-REVERSE")
      (libsource (lib "eagle-import") (part "CONNECTOR-HEADER-2X2P2X2P-2.54-REVERSE"))
    )
    (comp (ref "J255")
      (value "CONNECTOR-HEADER-2X2P2X2P-2.54-REVERSE")
      (footprint "eagle-import:2X2P-2.54-REVERSE")
      (libsource (lib "eagle-import") (part "CONNECTOR-HEADER-2X2P2X2P-2.54-REVERSE"))
    )
    (comp (ref "J256")
      (value "CONNECTOR-HEADER-2X2P2X2P-2.54-REVERSE")
      (footprint "eagle-import:2X2P-2.54-REVERSE")
      (libsource (lib "eagle-import") (part "CONNECTOR-HEADER-2X2P2X2P-2.54-REVERSE"))
    )
    (comp (ref "J257")
      (value "JACK-DC-3PJACK-DC-2.5-5.5-10A")
      (footprint "eagle-import:JACK-DC-2.5-5.5-10A")
      (libsource (lib "eagle-import") (part "JACK-DC-3PJACK-DC-2.5-5.5-10A"))
    )
    (comp (ref "JOIN_WIFI")
      (value "BUTTON-4P4P-12X12X6H")
      (footprint "eagle-import:4P-12X12X6H")
      (libsource (lib "eagle-import") (part "BUTTON-4P4P-12X12X6H"))
    )
    (comp (ref "JP1")
      (value "M12PTH")
      (footprint "eagle-import:1X12-SMALL-PADS")
      (libsource (lib "eagle-import") (part "M12PTH"))
    )
    (comp (ref "JP2")
      (value "M12PTH")
      (footprint "eagle-import:1X12-SMALL-PADS")
      (libsource (lib "eagle-import") (part "M12PTH"))
    )
    (comp (ref "JP3")
      (value "M12PTH")
      (footprint "eagle-import:1X12-SMALL-PADS")
      (libsource (lib "eagle-import") (part "M12PTH"))
    )
    (comp (ref "JP4")
      (value "M12PTH")
      (footprint "eagle-import:1X12-SMALL-PADS")
      (libsource (lib "eagle-import") (part "M12PTH"))
    )
    (comp (ref "JP5")
      (value "PINHD-2X4")
      (footprint "eagle-import:2X04")
      (libsource (lib "eagle-import") (part "PINHD-2X4"))
    )
    (comp (ref "M1")
      (value "MICROPHONE")
      (footprint "eagle-import:MICROPHONE")
      (libsource (lib "eagle-import") (part "MICROPHONE"))
    )
    (comp (ref "ONLINE/OFFLINE")
      (value "SWITCH-2P3T-SK12D07VG3")
      (footprint "eagle-import:SWITCH-2P3T-SK12D07VG3")
      (libsource (lib "eagle-import") (part "SWITCH-2P3T-SK12D07VG3"))
    )
    (comp (ref "Q1")
      (value "SS8550")
      (footprint "eagle-import:SOT23")
      (libsource (lib "eagle-import") (part "TRANSISTOR-PNP-041003001"))
    )
    (comp (ref "Q2")
      (value "FDD6637")
      (footprint "eagle-import:TO252")
      (libsource (lib "eagle-import") (part "FDD4141TO252"))
    )
    (comp (ref "Q3")
      (value "FDD6637")
      (footprint "eagle-import:TO252")
      (libsource (lib "eagle-import") (part "FDD4141TO252"))
    )
    (comp (ref "Q4")
      (value "SS8550")
      (footprint "eagle-import:SOT23")
      (libsource (lib "eagle-import") (part "TRANSISTOR-PNP-041003001"))
    )
    (comp (ref "Q5")
      (value "SS8550")
      (footprint "eagle-import:SOT23")
      (libsource (lib "eagle-import") (part "TRANSISTOR-PNP-041003001"))
    )
    (comp (ref "Q6")
      (value "FDD6637")
      (footprint "eagle-import:TO252")
      (libsource (lib "eagle-import") (part "FDD4141TO252"))
    )
    (comp (ref "Q7")
      (value "SS8550")
      (footprint "eagle-import:SOT23")
      (libsource (lib "eagle-import") (part "TRANSISTOR-PNP-041003001"))
    )
    (comp (ref "Q8")
      (value "FDD6637")
      (footprint "eagle-import:TO252")
      (libsource (lib "eagle-import") (part "FDD4141TO252"))
    )
    (comp (ref "R1")
      (value "10K")
      (footprint "eagle-import:R0603")
      (libsource (lib "eagle-import") (part "R-0603"))
    )
    (comp (ref "R2")
      (value "1K")
      (footprint "eagle-import:R0603")
      (libsource (lib "eagle-import") (part "R-0603"))
    )
    (comp (ref "R3")
      (value "0.1")
      (footprint "eagle-import:RESISTOR-3W-20MM")
      (libsource (lib "eagle-import") (part "RESISTOR-3W-20MM"))
    )
    (comp (ref "R4")
      (value "10K")
      (footprint "eagle-import:R0603")
      (libsource (lib "eagle-import") (part "R-0603"))
    )
    (comp (ref "R5")
      (value "1K")
      (footprint "eagle-import:R0603")
      (libsource (lib "eagle-import") (part "R-0603"))
    )
    (comp (ref "R6")
      (value "10K")
      (footprint "eagle-import:R0603")
      (libsource (lib "eagle-import") (part "R-0603"))
    )
    (comp (ref "R7")
      (value "0.1")
      (footprint "eagle-import:RESISTOR-3W-20MM")
      (libsource (lib "eagle-import") (part "RESISTOR-3W-20MM"))
    )
    (comp (ref "R8")
      (value "10K")
      (footprint "eagle-import:R0603")
      (libsource (lib "eagle-import") (part "R-0603"))
    )
    (comp (ref "R9")
      (value "10K")
      (footprint "eagle-import:R0603")
      (libsource (lib "eagle-import") (part "R-0603"))
    )
    (comp (ref "R10")
      (value "1K")
      (footprint "eagle-import:R0603")
      (libsource (lib "eagle-import") (part "R-0603"))
    )
    (comp (ref "R11")
      (value "100K")
      (footprint "eagle-import:R0603")
      (libsource (lib "eagle-import") (part "R-0603"))
    )
    (comp (ref "R12")
      (value "100K")
      (footprint "eagle-import:R0603")
      (libsource (lib "eagle-import") (part "R-0603"))
    )
    (comp (ref "R13")
      (value "4.7K")
      (footprint "eagle-import:R0603")
      (libsource (lib "eagle-import") (part "R-0603"))
    )
    (comp (ref "R14")
      (value "0.1")
      (footprint "eagle-import:RESISTOR-3W-20MM")
      (libsource (lib "eagle-import") (part "RESISTOR-3W-20MM"))
    )
    (comp (ref "R15")
      (value "10K")
      (footprint "eagle-import:R0603")
      (libsource (lib "eagle-import") (part "R-0603"))
    )
    (comp (ref "R16")
      (value "10K")
      (footprint "eagle-import:R0603")
      (libsource (lib "eagle-import") (part "R-0603"))
    )
    (comp (ref "R17")
      (value "1K")
      (footprint "eagle-import:R0603")
      (libsource (lib "eagle-import") (part "R-0603"))
    )
    (comp (ref "R18")
      (value "4.7K")
      (footprint "eagle-import:R0603")
      (libsource (lib "eagle-import") (part "R-0603"))
    )
    (comp (ref "R19")
      (value "4.7K")
      (footprint "eagle-import:R0603")
      (libsource (lib "eagle-import") (part "R-0603"))
    )
    (comp (ref "R20")
      (value "10K")
      (footprint "eagle-import:R0603")
      (libsource (lib "eagle-import") (part "R-0603"))
    )
    (comp (ref "R21")
      (value "10K")
      (footprint "eagle-import:R0603")
      (libsource (lib "eagle-import") (part "R-0603"))
    )
    (comp (ref "R22")
      (value "1M")
      (footprint "eagle-import:R0603")
      (libsource (lib "eagle-import") (part "R-0603"))
    )
    (comp (ref "R23")
      (value "10K")
      (footprint "eagle-import:R0603")
      (libsource (lib "eagle-import") (part "R-0603"))
    )
    (comp (ref "R24")
      (value "510K")
      (footprint "eagle-import:R0603")
      (libsource (lib "eagle-import") (part "R-0603"))
    )
    (comp (ref "R25")
      (value "4.7K")
      (footprint "eagle-import:R0603")
      (libsource (lib "eagle-import") (part "R-0603"))
    )
    (comp (ref "R26")
      (value "1K")
      (footprint "eagle-import:R0603")
      (libsource (lib "eagle-import") (part "R-0603"))
    )
    (comp (ref "R27")
      (value "0.1")
      (footprint "eagle-import:RESISTOR-3W-20MM")
      (libsource (lib "eagle-import") (part "RESISTOR-3W-20MM"))
    )
    (comp (ref "TER_CONN")
      (value "TERMINAL_CONN")
      (footprint "eagle-import:TERMINALCONNECTOR_15MM")
      (libsource (lib "eagle-import") (part "TERMINAL_CONN"))
    )
    (comp (ref "U$1")
      (value "L3D-LOGOL3DCUBE-LOGO-0.8X2.5")
      (footprint "eagle-import:L3DCUBE-LOGO-0.8X2.5")
      (libsource (lib "eagle-import") (part "L3D-LOGOL3DCUBE-LOGO-0.8X2.5"))
    )
    (comp (ref "U$2")
      (value "FIDUCIAL-MARK")
      (footprint "eagle-import:FIDUCIAL-MARK")
      (libsource (lib "eagle-import") (part "FIDUCIAL-MARK"))
    )
    (comp (ref "U$3")
      (value "FIDUCIAL-MARK")
      (footprint "eagle-import:FIDUCIAL-MARK")
      (libsource (lib "eagle-import") (part "FIDUCIAL-MARK"))
    )
    (comp (ref "U$4")
      (value "BEAGLEBONE_OUTLINE")
      (footprint "eagle-import:BEAGLEBONE_SHIELD")
      (libsource (lib "eagle-import") (part "BEAGLEBONE_OUTLINE"))
    )
    (comp (ref "U1")
      (value "ADXL335")
      (footprint "eagle-import:ADXL335")
      (libsource (lib "eagle-import") (part "ADXL335"))
    )
    (comp (ref "U2")
      (value "TXB0108PWR")
      (footprint "eagle-import:TSSOP20")
      (libsource (lib "eagle-import") (part "TXB0108PWR"))
    )
    (comp (ref "U3")
      (value "LMV324IDR-1100030P1")
      (footprint "eagle-import:SOIC14")
      (libsource (lib "eagle-import") (part "LMV324IDR-1100030P1"))
    )
  )
  (nets
    (net (code "1") (name "+3V3") (class "Default")
      (node (ref "C11") (pin "2") (pinfunction "2_2") (pintype "bidirectional"))
      (node (ref "C15") (pin "2") (pinfunction "2_2") (pintype "bidirectional"))
      (node (ref "JP2") (pin "1") (pinfunction "1_1") (pintype "passive"))
      (node (ref "JP2") (pin "3") (pinfunction "3_3") (pintype "passive"))
      (node (ref "JP4") (pin "1") (pinfunction "1_1") (pintype "passive"))
      (node (ref "JP4") (pin "3") (pinfunction "3_3") (pintype "passive"))
      (node (ref "R11") (pin "2") (pinfunction "2_2") (pintype "bidirectional"))
      (node (ref "R13") (pin "2") (pinfunction "2_2") (pintype "bidirectional"))
      (node (ref "R16") (pin "1") (pinfunction "1_1") (pintype "bidirectional"))
      (node (ref "R18") (pin "2") (pinfunction "2_2") (pintype "bidirectional"))
      (node (ref "R6") (pin "1") (pinfunction "1_1") (pintype "bidirectional"))
      (node (ref "U$4") (pin "49") (pinfunction "VDD_3V3EXP_49") (pintype "power_in"))
      (node (ref "U$4") (pin "50") (pinfunction "VDD_3V3EXP_50") (pintype "power_in"))
      (node (ref "U1") (pin "VSS1") (pinfunction "VSS1_VSS1") (pintype "bidirectional"))
      (node (ref "U1") (pin "VSS2") (pinfunction "VSS2_VSS2") (pintype "bidirectional"))
      (node (ref "U2") (pin "10") (pinfunction "OE_10") (pintype "bidirectional"))
      (node (ref "U2") (pin "2") (pinfunction "VCCA_2") (pintype "bidirectional"))
      (node (ref "U3") (pin "11") (pinfunction "V-_11") (pintype "power_in"))
    )
    (net (code "2") (name "+5V") (class "Default")
      (node (ref "C21") (pin "+") (pinfunction "1_+") (pintype "bidirectional"))
      (node (ref "C22") (pin "2") (pinfunction "2_2") (pintype "bidirectional"))
      (node (ref "C23") (pin "2") (pinfunction "2_2") (pintype "bidirectional"))
      (node (ref "J257") (pin "+") (pinfunction "+_+") (pintype "bidirectional"))
      (node (ref "JP1") (pin "1") (pinfunction "1_1") (pintype "passive"))
      (node (ref "JP3") (pin "1") (pinfunction "1_1") (pintype "passive"))
      (node (ref "Q1") (pin "2") (pinfunction "E_2") (pintype "passive"))
      (node (ref "Q4") (pin "2") (pinfunction "E_2") (pintype "passive"))
      (node (ref "Q5") (pin "2") (pinfunction "E_2") (pintype "passive"))
      (node (ref "Q7") (pin "2") (pinfunction "E_2") (pintype "passive"))
      (node (ref "R14") (pin "1") (pinfunction "1_1") (pintype "bidirectional"))
      (node (ref "R27") (pin "1") (pinfunction "1_1") (pintype "bidirectional"))
      (node (ref "R3") (pin "1") (pinfunction "1_1") (pintype "bidirectional"))
      (node (ref "R7") (pin "1") (pinfunction "1_1") (pintype "bidirectional"))
      (node (ref "U$4") (pin "51") (pinfunction "VDD_5V_51") (pintype "power_in"))
      (node (ref "U$4") (pin "52") (pinfunction "VDD_5V_52") (pintype "power_in"))
      (node (ref "U2") (pin "19") (pinfunction "VCCB_19") (pintype "bidirectional"))
    )
    (net (code "3") (name "/A2") (class "Default")
      (node (ref "JP1") (pin "10") (pinfunction "10_10") (pintype "passive"))
      (node (ref "JP3") (pin "10") (pinfunction "10_10") (pintype "passive"))
      (node (ref "U$4") (pin "43") (pinfunction "GPIO2_8_43") (pintype "passive"))
      (node (ref "U2") (pin "6") (pinfunction "A5_6") (pintype "bidirectional"))
    )
    (net (code "4") (name "/A3") (class "Default")
      (node (ref "JP1") (pin "9") (pinfunction "9_9") (pintype "passive"))
      (node (ref "JP3") (pin "9") (pinfunction "9_9") (pintype "passive"))
      (node (ref "U$4") (pin "39") (pinfunction "GPIO2_12_39") (pintype "passive"))
      (node (ref "U2") (pin "7") (pinfunction "A6_7") (pintype "bidirectional"))
    )
    (net (code "5") (name "/A4") (class "Default")
      (node (ref "JP1") (pin "8") (pinfunction "8_8") (pintype "passive"))
      (node (ref "JP3") (pin "8") (pinfunction "8_8") (pintype "passive"))
      (node (ref "U$4") (pin "44") (pinfunction "GPIO2_9_44") (pintype "passive"))
      (node (ref "U2") (pin "8") (pinfunction "A7_8") (pintype "bidirectional"))
    )
    (net (code "6") (name "/A5") (class "Default")
      (node (ref "JP1") (pin "7") (pinfunction "7_7") (pintype "passive"))
      (node (ref "JP3") (pin "7") (pinfunction "7_7") (pintype "passive"))
      (node (ref "U$4") (pin "40") (pinfunction "GPIO2_13_40") (pintype "passive"))
      (node (ref "U2") (pin "9") (pinfunction "A8_9") (pintype "bidirectional"))
    )
    (net (code "7") (name "/AIN0") (class "Default")
      (node (ref "U$4") (pin "85") (pinfunction "AIN0_85") (pintype "power_in"))
    )
    (net (code "8") (name "/D0") (class "Default")
      (node (ref "JP2") (pin "12") (pinfunction "12_12") (pintype "passive"))
      (node (ref "JP4") (pin "12") (pinfunction "12_12") (pintype "passive"))
      (node (ref "U$4") (pin "45") (pinfunction "GPIO2_6_45") (pintype "passive"))
      (node (ref "U2") (pin "1") (pinfunction "A1_1") (pintype "bidirectional"))
    )
    (net (code "9") (name "/D1") (class "Default")
      (node (ref "JP2") (pin "11") (pinfunction "11_11") (pintype "passive"))
      (node (ref "JP4") (pin "11") (pinfunction "11_11") (pintype "passive"))
      (node (ref "U$4") (pin "41") (pinfunction "GPIO2_10_41") (pintype "passive"))
      (node (ref "U2") (pin "3") (pinfunction "A2_3") (pintype "bidirectional"))
    )
    (net (code "10") (name "/D2") (class "Default")
      (node (ref "JP2") (pin "10") (pinfunction "10_10") (pintype "passive"))
      (node (ref "JP4") (pin "10") (pinfunction "10_10") (pintype "passive"))
      (node (ref "U$4") (pin "46") (pinfunction "GPIO2_7_46") (pintype "passive"))
      (node (ref "U2") (pin "4") (pinfunction "A3_4") (pintype "bidirectional"))
    )
    (net (code "11") (name "/D3") (class "Default")
      (node (ref "JP2") (pin "9") (pinfunction "9_9") (pintype "passive"))
      (node (ref "JP4") (pin "9") (pinfunction "9_9") (pintype "passive"))
      (node (ref "U$4") (pin "42") (pinfunction "GPIO2_11_42") (pintype "passive"))
      (node (ref "U2") (pin "5") (pinfunction "A4_5") (pintype "bidirectional"))
    )
    (net (code "12") (name "/D7") (class "Default")
      (node (ref "JP2") (pin "5") (pinfunction "5_5") (pintype "passive"))
      (node (ref "JP4") (pin "5") (pinfunction "5_5") (pintype "passive"))
    )
    (net (code "13") (name "/DOUT_1") (class "Default")
      (node (ref "J32") (pin "3") (pinfunction "3_3") (pintype "bidirectional"))
      (node (ref "JP5") (pin "1") (pinfunction "1_1") (pintype "passive"))
    )
    (net (code "14") (name "/DOUT_3") (class "Default")
      (node (ref "J96") (pin "3") (pinfunction "3_3") (pintype "bidirectional"))
      (node (ref "JP5") (pin "3") (pinfunction "3_3") (pintype "passive"))
    )
    (net (code "15") (name "/DOUT_5") (class "Default")
      (node (ref "J160") (pin "3") (pinfunction "3_3") (pintype "bidirectional"))
      (node (ref "JP5") (pin "5") (pinfunction "5_5") (pintype "passive"))
    )
    (net (code "16") (name "/DOUT_7") (class "Default")
      (node (ref "J224") (pin "3") (pinfunction "3_3") (pintype "bidirectional"))
      (node (ref "JP5") (pin "7") (pinfunction "7_7") (pintype "passive"))
    )
    (net (code "17") (name "/RX") (class "Default")
      (node (ref "JP1") (pin "4") (pinfunction "4_4") (pintype "passive"))
      (node (ref "JP3") (pin "4") (pinfunction "4_4") (pintype "passive"))
    )
    (net (code "18") (name "/SYS_5V") (class "Default")
      (node (ref "U$4") (pin "53") (pinfunction "SYS_5V_53") (pintype "power_in"))
    )
    (net (code "19") (name "/TX") (class "Default")
      (node (ref "JP1") (pin "3") (pinfunction "3_3") (pintype "passive"))
      (node (ref "JP3") (pin "3") (pinfunction "3_3") (pintype "passive"))
    )
    (net (code "20") (name "/~{RST}") (class "Default")
      (node (ref "JP2") (pin "2") (pinfunction "2_2") (pintype "passive"))
      (node (ref "JP4") (pin "2") (pinfunction "2_2") (pintype "passive"))
    )
    (net (code "21") (name "DIN_1") (class "Default")
      (node (ref "J1") (pin "2") (pinfunction "2_2") (pintype "bidirectional"))
      (node (ref "U2") (pin "20") (pinfunction "B1_20") (pintype "bidirectional"))
    )
    (net (code "22") (name "DIN_2") (class "Default")
      (node (ref "J33") (pin "2") (pinfunction "2_2") (pintype "bidirectional"))
      (node (ref "JP5") (pin "2") (pinfunction "2_2") (pintype "passive"))
      (node (ref "U2") (pin "18") (pinfunction "B2_18") (pintype "bidirectional"))
    )
    (net (code "23") (name "DIN_3") (class "Default")
      (node (ref "J65") (pin "2") (pinfunction "2_2") (pintype "bidirectional"))
      (node (ref "U2") (pin "17") (pinfunction "B3_17") (pintype "bidirectional"))
    )
    (net (code "24") (name "DIN_4") (class "Default")
      (node (ref "J97") (pin "2") (pinfunction "2_2") (pintype "bidirectional"))
      (node (ref "JP5") (pin "4") (pinfunction "4_4") (pintype "passive"))
      (node (ref "U2") (pin "16") (pinfunction "B4_16") (pintype "bidirectional"))
    )
    (net (code "25") (name "DIN_5") (class "Default")
      (node (ref "J129") (pin "2") (pinfunction "2_2") (pintype "bidirectional"))
      (node (ref "U2") (pin "15") (pinfunction "B5_15") (pintype "bidirectional"))
    )
    (net (code "26") (name "DIN_6") (class "Default")
      (node (ref "J161") (pin "2") (pinfunction "2_2") (pintype "bidirectional"))
      (node (ref "JP5") (pin "6") (pinfunction "6_6") (pintype "passive"))
      (node (ref "U2") (pin "14") (pinfunction "B6_14") (pintype "bidirectional"))
    )
    (net (code "27") (name "DIN_7") (class "Default")
      (node (ref "J193") (pin "2") (pinfunction "2_2") (pintype "bidirectional"))
      (node (ref "U2") (pin "13") (pinfunction "B7_13") (pintype "bidirectional"))
    )
    (net (code "28") (name "DIN_8") (class "Default")
      (node (ref "J225") (pin "2") (pinfunction "2_2") (pintype "bidirectional"))
      (node (ref "JP5") (pin "8") (pinfunction "8_8") (pintype "passive"))
      (node (ref "U2") (pin "12") (pinfunction "B8_12") (pintype "bidirectional"))
    )
    (net (code "29") (name "GND") (class "Default")
      (node (ref "C1") (pin "-") (pinfunction "2_-") (pintype "bidirectional"))
      (node (ref "C11") (pin "1") (pinfunction "1_1") (pintype "bidirectional"))
      (node (ref "C12") (pin "1") (pinfunction "1_1") (pintype "bidirectional"))
      (node (ref "C13") (pin "1") (pinfunction "1_1") (pintype "bidirectional"))
      (node (ref "C14") (pin "1") (pinfunction "1_1") (pintype "bidirectional"))
      (node (ref "C15") (pin "1") (pinfunction "1_1") (pintype "bidirectional"))
      (node (ref "C18") (pin "1") (pinfunction "1_1") (pintype "bidirectional"))
      (node (ref "C19") (pin "1") (pinfunction "1_1") (pintype "bidirectional"))
      (node (ref "C2") (pin "-") (pinfunction "2_-") (pintype "bidirectional"))
      (node (ref "C20") (pin "1") (pinfunction "1_1") (pintype "bidirectional"))
      (node (ref "C21") (pin "-") (pinfunction "2_-") (pintype "bidirectional"))
      (node (ref "C22") (pin "1") (pinfunction "1_1") (pintype "bidirectional"))
      (node (ref "C23") (pin "1") (pinfunction "1_1") (pintype "bidirectional"))
      (node (ref "C3") (pin "-") (pinfunction "2_-") (pintype "bidirectional"))
      (node (ref "C4") (pin "-") (pinfunction "2_-") (pintype "bidirectional"))
      (node (ref "C5") (pin "1") (pinfunction "1_1") (pintype "bidirectional"))
      (node (ref "C6") (pin "1") (pinfunction "1_1") (pintype "bidirectional"))
      (node (ref "C7") (pin "1") (pinfunction "1_1") (pintype "bidirectional"))
      (node (ref "C8") (pin "1") (pinfunction "1_1") (pintype "bidirectional"))
      (node (ref "J1") (pin "4") (pinfunction "4_4") (pintype "bidirectional"))
      (node (ref "J10") (pin "4") (pinfunction "4_4") (pintype "bidirectional"))
      (node (ref "J100") (pin "4") (pinfunction "4_4") (pintype "bidirectional"))
      (node (ref "J101") (pin "4") (pinfunction "4_4") (pintype "bidirectional"))
      (node (ref "J102") (pin "4") (pinfunction "4_4") (pintype "bidirectional"))
      (node (ref "J103") (pin "4") (pinfunction "4_4") (pintype "bidirectional"))
      (node (ref "J104") (pin "4") (pinfunction "4_4") (pintype "bidirectional"))
      (node (ref "J105") (pin "4") (pinfunction "4_4") (pintype "bidirectional"))
      (node (ref "J106") (pin "4") (pinfunction "4_4") (pintype "bidirectional"))
      (node (ref "J107") (pin "4") (pinfunction "4_4") (pintype "bidirectional"))
      (node (ref "J108") (pin "4") (pinfunction "4_4") (pintype "bidirectional"))
      (node (ref "J109") (pin "4") (pinfunction "4_4") (pintype "bidirectional"))
      (node (ref "J11") (pin "4") (pinfunction "4_4") (pintype "bidirectional"))
      (node (ref "J110") (pin "4") (pinfunction "4_4") (pintype "bidirectional"))
      (node (ref "J111") (pin "4") (pinfunction "4_4") (pintype "bidirectional"))
      (node (ref "J112") (pin "4") (pinfunction "4_4") (pintype "bidirectional"))
      (node (ref "J113") (pin "4") (pinfunction "4_4") (pintype "bidirectional"))
      (node (ref "J114") (pin "4") (pinfunction "4_4") (pintype "bidirectional"))
      (node (ref "J115") (pin "4") (pinfunction "4_4") (pintype "bidirectional"))
      (node (ref "J116") (pin "4") (pinfunction "4_4") (pintype "bidirectional"))
      (node (ref "J117") (pin "4") (pinfunction "4_4") (pintype "bidirectional"))
      (node (ref "J118") (pin "4") (pinfunction "4_4") (pintype "bidirectional"))
      (node (ref "J119") (pin "4") (pinfunction "4_4") (pintype "bidirectional"))
      (node (ref "J12") (pin "4") (pinfunction "4_4") (pintype "bidirectional"))
      (node (ref "J120") (pin "4") (pinfunction "4_4") (pintype "bidirectional"))
      (node (ref "J121") (pin "4") (pinfunction "4_4") (pintype "bidirectional"))
      (node (ref "J122") (pin "4") (pinfunction "4_4") (pintype "bidirectional"))
      (node (ref "J123") (pin "4") (pinfunction "4_4") (pintype "bidirectional"))
      (node (ref "J124") (pin "4") (pinfunction "4_4") (pintype "bidirectional"))
      (node (ref "J125") (pin "4") (pinfunction "4_4") (pintype "bidirectional"))
      (node (ref "J126") (pin "4") (pinfunction "4_4") (pintype "bidirectional"))
      (node (ref "J127") (pin "4") (pinfunction "4_4") (pintype "bidirectional"))
      (node (ref "J128") (pin "4") (pinfunction "4_4") (pintype "bidirectional"))
      (node (ref "J129") (pin "4") (pinfunction "4_4") (pintype "bidirectional"))
      (node (ref "J13") (pin "4") (pinfunction "4_4") (pintype "bidirectional"))
      (node (ref "J130") (pin "4") (pinfunction "4_4") (pintype "bidirectional"))
      (node (ref "J131") (pin "4") (pinfunction "4_4") (pintype "bidirectional"))
      (node (ref "J132") (pin "4") (pinfunction "4_4") (pintype "bidirectional"))
      (node (ref "J133") (pin "4") (pinfunction "4_4") (pintype "bidirectional"))
      (node (ref "J134") (pin "4") (pinfunction "4_4") (pintype "bidirectional"))
      (node (ref "J135") (pin "4") (pinfunction "4_4") (pintype "bidirectional"))
      (node (ref "J136") (pin "4") (pinfunction "4_4") (pintype "bidirectional"))
      (node (ref "J137") (pin "4") (pinfunction "4_4") (pintype "bidirectional"))
      (node (ref "J138") (pin "4") (pinfunction "4_4") (pintype "bidirectional"))
      (node (ref "J139") (pin "4") (pinfunction "4_4") (pintype "bidirectional"))
      (node (ref "J14") (pin "4") (pinfunction "4_4") (pintype "bidirectional"))
      (node (ref "J140") (pin "4") (pinfunction "4_4") (pintype "bidirectional"))
      (node (ref "J141") (pin "4") (pinfunction "4_4") (pintype "bidirectional"))
      (node (ref "J142") (pin "4") (pinfunction "4_4") (pintype "bidirectional"))
      (node (ref "J143") (pin "4") (pinfunction "4_4") (pintype "bidirectional"))
      (node (ref "J144") (pin "4") (pinfunction "4_4") (pintype "bidirectional"))
      (node (ref "J145") (pin "4") (pinfunction "4_4") (pintype "bidirectional"))
      (node (ref "J146") (pin "4") (pinfunction "4_4") (pintype "bidirectional"))
      (node (ref "J147") (pin "4") (pinfunction "4_4") (pintype "bidirectional"))
      (node (ref "J148") (pin "4") (pinfunction "4_4") (pintype "bidirectional"))
      (node (ref "J149") (pin "4") (pinfunction "4_4") (pintype "bidirectional"))
      (node (ref "J15") (pin "4") (pinfunction "4_4") (pintype "bidirectional"))
      (node (ref "J150") (pin "4") (pinfunction "4_4") (pintype "bidirectional"))
      (node (ref "J151") (pin "4") (pinfunction "4_4") (pintype "bidirectional"))
      (node (ref "J152") (pin "4") (pinfunction "4_4") (pintype "bidirectional"))
      (node (ref "J153") (pin "4") (pinfunction "4_4") (pintype "bidirectional"))
      (node (ref "J154") (pin "4") (pinfunction "4_4") (pintype "bidirectional"))
      (node (ref "J155") (pin "4") (pinfunction "4_4") (pintype "bidirectional"))
      (node (ref "J156") (pin "4") (pinfunction "4_4") (pintype "bidirectional"))
      (node (ref "J157") (pin "4") (pinfunction "4_4") (pintype "bidirectional"))
      (node (ref "J158") (pin "4") (pinfunction "4_4") (pintype "bidirectional"))
      (node (ref "J159") (pin "4") (pinfunction "4_4") (pintype "bidirectional"))
      (node (ref "J16") (pin "4") (pinfunction "4_4") (pintype "bidirectional"))
      (node (ref "J160") (pin "4") (pinfunction "4_4") (pintype "bidirectional"))
      (node (ref "J161") (pin "4") (pinfunction "4_4") (pintype "bidirectional"))
      (node (ref "J162") (pin "4") (pinfunction "4_4") (pintype "bidirectional"))
      (node (ref "J163") (pin "4") (pinfunction "4_4") (pintype "bidirectional"))
      (node (ref "J164") (pin "4") (pinfunction "4_4") (pintype "bidirectional"))
      (node (ref "J165") (pin "4") (pinfunction "4_4") (pintype "bidirectional"))
      (node (ref "J166") (pin "4") (pinfunction "4_4") (pintype "bidirectional"))
      (node (ref "J167") (pin "4") (pinfunction "4_4") (pintype "bidirectional"))
      (node (ref "J168") (pin "4") (pinfunction "4_4") (pintype "bidirectional"))
      (node (ref "J169") (pin "4") (pinfunction "4_4") (pintype "bidirectional"))
      (node (ref "J17") (pin "4") (pinfunction "4_4") (pintype "bidirectional"))
      (node (ref "J170") (pin "4") (pinfunction "4_4") (pintype "bidirectional"))
      (node (ref "J171") (pin "4") (pinfunction "4_4") (pintype "bidirectional"))
      (node (ref "J172") (pin "4") (pinfunction "4_4") (pintype "bidirectional"))
      (node (ref "J173") (pin "4") (pinfunction "4_4") (pintype "bidirectional"))
      (node (ref "J174") (pin "4") (pinfunction "4_4") (pintype "bidirectional"))
      (node (ref "J175") (pin "4") (pinfunction "4_4") (pintype "bidirectional"))
      (node (ref "J176") (pin "4") (pinfunction "4_4") (pintype "bidirectional"))
      (node (ref "J177") (pin "4") (pinfunction "4_4") (pintype "bidirectional"))
      (node (ref "J178") (pin "4") (pinfunction "4_4") (pintype "bidirectional"))
      (node (ref "J179") (pin "4") (pinfunction "4_4") (pintype "bidirectional"))
      (node (ref "J18") (pin "4") (pinfunction "4_4") (pintype "bidirectional"))
      (node (ref "J180") (pin "4") (pinfunction "4_4") (pintype "bidirectional"))
      (node (ref "J181") (pin "4") (pinfunction "4_4") (pintype "bidirectional"))
      (node (ref "J182") (pin "4") (pinfunction "4_4") (pintype "bidirectional"))
      (node (ref "J183") (pin "4") (pinfunction "4_4") (pintype "bidirectional"))
      (node (ref "J184") (pin "4") (pinfunction "4_4") (pintype "bidirectional"))
      (node (ref "J185") (pin "4") (pinfunction "4_4") (pintype "bidirectional"))
      (node (ref "J186") (pin "4") (pinfunction "4_4") (pintype "bidirectional"))
      (node (ref "J187") (pin "4") (pinfunction "4_4") (pintype "bidirectional"))
      (node (ref "J188") (pin "4") (pinfunction "4_4") (pintype "bidirectional"))
      (node (ref "J189") (pin "4") (pinfunction "4_4") (pintype "bidirectional"))
      (node (ref "J19") (pin "4") (pinfunction "4_4") (pintype "bidirectional"))
      (node (ref "J190") (pin "4") (pinfunction "4_4") (pintype "bidirectional"))
      (node (ref "J191") (pin "4") (pinfunction "4_4") (pintype "bidirectional"))
      (node (ref "J192") (pin "4") (pinfunction "4_4") (pintype "bidirectional"))
      (node (ref "J193") (pin "4") (pinfunction "4_4") (pintype "bidirectional"))
      (node (ref "J194") (pin "4") (pinfunction "4_4") (pintype "bidirectional"))
      (node (ref "J195") (pin "4") (pinfunction "4_4") (pintype "bidirectional"))
      (node (ref "J196") (pin "4") (pinfunction "4_4") (pintype "bidirectional"))
      (node (ref "J197") (pin "4") (pinfunction "4_4") (pintype "bidirectional"))
      (node (ref "J198") (pin "4") (pinfunction "4_4") (pintype "bidirectional"))
      (node (ref "J199") (pin "4") (pinfunction "4_4") (pintype "bidirectional"))
      (node (ref "J2") (pin "4") (pinfunction "4_4") (pintype "bidirectional"))
      (node (ref "J20") (pin "4") (pinfunction "4_4") (pintype "bidirectional"))
      (node (ref "J200") (pin "4") (pinfunction "4_4") (pintype "bidirectional"))
      (node (ref "J201") (pin "4") (pinfunction "4_4") (pintype "bidirectional"))
      (node (ref "J202") (pin "4") (pinfunction "4_4") (pintype "bidirectional"))
      (node (ref "J203") (pin "4") (pinfunction "4_4") (pintype "bidirectional"))
      (node (ref "J204") (pin "4") (pinfunction "4_4") (pintype "bidirectional"))
      (node (ref "J205") (pin "4") (pinfunction "4_4") (pintype "bidirectional"))
      (node (ref "J206") (pin "4") (pinfunction "4_4") (pintype "bidirectional"))
      (node (ref "J207") (pin "4") (pinfunction "4_4") (pintype "bidirectional"))
      (node (ref "J208") (pin "4") (pinfunction "4_4") (pintype "bidirectional"))
      (node (ref "J209") (pin "4") (pinfunction "4_4") (pintype "bidirectional"))
      (node (ref "J21") (pin "4") (pinfunction "4_4") (pintype "bidirectional"))
      (node (ref "J210") (pin "4") (pinfunction "4_4") (pintype "bidirectional"))
      (node (ref "J211") (pin "4") (pinfunction "4_4") (pintype "bidirectional"))
      (node (ref "J212") (pin "4") (pinfunction "4_4") (pintype "bidirectional"))
      (node (ref "J213") (pin "4") (pinfunction "4_4") (pintype "bidirectional"))
      (node (ref "J214") (pin "4") (pinfunction "4_4") (pintype "bidirectional"))
      (node (ref "J215") (pin "4") (pinfunction "4_4") (pintype "bidirectional"))
      (node (ref "J216") (pin "4") (pinfunction "4_4") (pintype "bidirectional"))
      (node (ref "J217") (pin "4") (pinfunction "4_4") (pintype "bidirectional"))
      (node (ref "J218") (pin "4") (pinfunction "4_4") (pintype "bidirectional"))
      (node (ref "J219") (pin "4") (pinfunction "4_4") (pintype "bidirectional"))
      (node (ref "J22") (pin "4") (pinfunction "4_4") (pintype "bidirectional"))
      (node (ref "J220") (pin "4") (pinfunction "4_4") (pintype "bidirectional"))
      (node (ref "J221") (pin "4") (pinfunction "4_4") (pintype "bidirectional"))
      (node (ref "J222") (pin "4") (pinfunction "4_4") (pintype "bidirectional"))
      (node (ref "J223") (pin "4") (pinfunction "4_4") (pintype "bidirectional"))
      (node (ref "J224") (pin "4") (pinfunction "4_4") (pintype "bidirectional"))
      (node (ref "J225") (pin "4") (pinfunction "4_4") (pintype "bidirectional"))
      (node (ref "J226") (pin "4") (pinfunction "4_4") (pintype "bidirectional"))
      (node (ref "J227") (pin "4") (pinfunction "4_4") (pintype "bidirectional"))
      (node (ref "J228") (pin "4") (pinfunction "4_4") (pintype "bidirectional"))
      (node (ref "J229") (pin "4") (pinfunction "4_4") (pintype "bidirectional"))
      (node (ref "J23") (pin "4") (pinfunction "4_4") (pintype "bidirectional"))
      (node (ref "J230") (pin "4") (pinfunction "4_4") (pintype "bidirectional"))
      (node (ref "J231") (pin "4") (pinfunction "4_4") (pintype "bidirectional"))
      (node (ref "J232") (pin "4") (pinfunction "4_4") (pintype "bidirectional"))
      (node (ref "J233") (pin "4") (pinfunction "4_4") (pintype "bidirectional"))
      (node (ref "J234") (pin "4") (pinfunction "4_4") (pintype "bidirectional"))
      (node (ref "J235") (pin "4") (pinfunction "4_4") (pintype "bidirectional"))
      (node (ref "J236") (pin "4") (pinfunction "4_4") (pintype "bidirectional"))
      (node (ref "J237") (pin "4") (pinfunction "4_4") (pintype "bidirectional"))
      (node (ref "J238") (pin "4") (pinfunction "4_4") (pintype "bidirectional"))
      (node (ref "J239") (pin "4") (pinfunction "4_4") (pintype "bidirectional"))
      (node (ref "J24") (pin "4") (pinfunction "4_4") (pintype "bidirectional"))
      (node (ref "J240") (pin "4") (pinfunction "4_4") (pintype "bidirectional"))
      (node (ref "J241") (pin "4") (pinfunction "4_4") (pintype "bidirectional"))
      (node (ref "J242") (pin "4") (pinfunction "4_4") (pintype "bidirectional"))
      (node (ref "J243") (pin "4") (pinfunction "4_4") (pintype "bidirectional"))
      (node (ref "J244") (pin "4") (pinfunction "4_4") (pintype "bidirectional"))
      (node (ref "J245") (pin "4") (pinfunction "4_4") (pintype "bidirectional"))
      (node (ref "J246") (pin "4") (pinfunction "4_4") (pintype "bidirectional"))
      (node (ref "J247") (pin "4") (pinfunction "4_4") (pintype "bidirectional"))
      (node (ref "J248") (pin "4") (pinfunction "4_4") (pintype "bidirectional"))
      (node (ref "J249") (pin "4") (pinfunction "4_4") (pintype "bidirectional"))
      (node (ref "J25") (pin "4") (pinfunction "4_4") (pintype "bidirectional"))
      (node (ref "J250") (pin "4") (pinfunction "4_4") (pintype "bidirectional"))
      (node (ref "J251") (pin "4") (pinfunction "4_4") (pintype "bidirectional"))
      (node (ref "J252") (pin "4") (pinfunction "4_4") (pintype "bidirectional"))
      (node (ref "J253") (pin "4") (pinfunction "4_4") (pintype "bidirectional"))
      (node (ref "J254") (pin "4") (pinfunction "4_4") (pintype "bidirectional"))
      (node (ref "J255") (pin "4") (pinfunction "4_4") (pintype "bidirectional"))
      (node (ref "J256") (pin "4") (pinfunction "4_4") (pintype "bidirectional"))
      (node (ref "J257") (pin "-1") (pinfunction "-_-1") (pintype "bidirectional"))
      (node (ref "J257") (pin "-2") (pinfunction "-_-2") (pintype "bidirectional"))
      (node (ref "J257") (pin "-3") (pinfunction "-_-3") (pintype "bidirectional"))
      (node (ref "J257") (pin "-4") (pinfunction "-_-4") (pintype "bidirectional"))
      (node (ref "J257") (pin "S1") (pinfunction "CDN_S1") (pintype "bidirectional"))
      (node (ref "J257") (pin "S10") (pinfunction "CDN_S10") (pintype "bidirectional"))
      (node (ref "J257") (pin "S11") (pinfunction "CDN_S11") (pintype "bidirectional"))
      (node (ref "J257") (pin "S12") (pinfunction "CDN_S12") (pintype "bidirectional"))
      (node (ref "J257") (pin "S2") (pinfunction "CDN_S2") (pintype "bidirectional"))
      (node (ref "J257") (pin "S3") (pinfunction "CDN_S3") (pintype "bidirectional"))
      (node (ref "J257") (pin "S4") (pinfunction "CDN_S4") (pintype "bidirectional"))
      (node (ref "J257") (pin "S5") (pinfunction "CDN_S5") (pintype "bidirectional"))
      (node (ref "J257") (pin "S6") (pinfunction "CDN_S6") (pintype "bidirectional"))
      (node (ref "J257") (pin "S7") (pinfunction "CDN_S7") (pintype "bidirectional"))
      (node (ref "J257") (pin "S8") (pinfunction "CDN_S8") (pintype "bidirectional"))
      (node (ref "J257") (pin "S9") (pinfunction "CDN_S9") (pintype "bidirectional"))
      (node (ref "J26") (pin "4") (pinfunction "4_4") (pintype "bidirectional"))
      (node (ref "J27") (pin "4") (pinfunction "4_4") (pintype "bidirectional"))
      (node (ref "J28") (pin "4") (pinfunction "4_4") (pintype "bidirectional"))
      (node (ref "J29") (pin "4") (pinfunction "4_4") (pintype "bidirectional"))
      (node (ref "J3") (pin "4") (pinfunction "4_4") (pintype "bidirectional"))
      (node (ref "J30") (pin "4") (pinfunction "4_4") (pintype "bidirectional"))
      (node (ref "J31") (pin "4") (pinfunction "4_4") (pintype "bidirectional"))
      (node (ref "J32") (pin "4") (pinfunction "4_4") (pintype "bidirectional"))
      (node (ref "J33") (pin "4") (pinfunction "4_4") (pintype "bidirectional"))
      (node (ref "J34") (pin "4") (pinfunction "4_4") (pintype "bidirectional"))
      (node (ref "J35") (pin "4") (pinfunction "4_4") (pintype "bidirectional"))
      (node (ref "J36") (pin "4") (pinfunction "4_4") (pintype "bidirectional"))
      (node (ref "J37") (pin "4") (pinfunction "4_4") (pintype "bidirectional"))
      (node (ref "J38") (pin "4") (pinfunction "4_4") (pintype "bidirectional"))
      (node (ref "J39") (pin "4") (pinfunction "4_4") (pintype "bidirectional"))
      (node (ref "J4") (pin "4") (pinfunction "4_4") (pintype "bidirectional"))
      (node (ref "J40") (pin "4") (pinfunction "4_4") (pintype "bidirectional"))
      (node (ref "J41") (pin "4") (pinfunction "4_4") (pintype "bidirectional"))
      (node (ref "J42") (pin "4") (pinfunction "4_4") (pintype "bidirectional"))
      (node (ref "J43") (pin "4") (pinfunction "4_4") (pintype "bidirectional"))
      (node (ref "J44") (pin "4") (pinfunction "4_4") (pintype "bidirectional"))
      (node (ref "J45") (pin "4") (pinfunction "4_4") (pintype "bidirectional"))
      (node (ref "J46") (pin "4") (pinfunction "4_4") (pintype "bidirectional"))
      (node (ref "J47") (pin "4") (pinfunction "4_4") (pintype "bidirectional"))
      (node (ref "J48") (pin "4") (pinfunction "4_4") (pintype "bidirectional"))
      (node (ref "J49") (pin "4") (pinfunction "4_4") (pintype "bidirectional"))
      (node (ref "J5") (pin "4") (pinfunction "4_4") (pintype "bidirectional"))
      (node (ref "J50") (pin "4") (pinfunction "4_4") (pintype "bidirectional"))
      (node (ref "J51") (pin "4") (pinfunction "4_4") (pintype "bidirectional"))
      (node (ref "J52") (pin "4") (pinfunction "4_4") (pintype "bidirectional"))
      (node (ref "J53") (pin "4") (pinfunction "4_4") (pintype "bidirectional"))
      (node (ref "J54") (pin "4") (pinfunction "4_4") (pintype "bidirectional"))
      (node (ref "J55") (pin "4") (pinfunction "4_4") (pintype "bidirectional"))
      (node (ref "J56") (pin "4") (pinfunction "4_4") (pintype "bidirectional"))
      (node (ref "J57") (pin "4") (pinfunction "4_4") (pintype "bidirectional"))
      (node (ref "J58") (pin "4") (pinfunction "4_4") (pintype "bidirectional"))
      (node (ref "J59") (pin "4") (pinfunction "4_4") (pintype "bidirectional"))
      (node (ref "J6") (pin "4") (pinfunction "4_4") (pintype "bidirectional"))
      (node (ref "J60") (pin "4") (pinfunction "4_4") (pintype "bidirectional"))
      (node (ref "J61") (pin "4") (pinfunction "4_4") (pintype "bidirectional"))
      (node (ref "J62") (pin "4") (pinfunction "4_4") (pintype "bidirectional"))
      (node (ref "J63") (pin "4") (pinfunction "4_4") (pintype "bidirectional"))
      (node (ref "J64") (pin "4") (pinfunction "4_4") (pintype "bidirectional"))
      (node (ref "J65") (pin "4") (pinfunction "4_4") (pintype "bidirectional"))
      (node (ref "J66") (pin "4") (pinfunction "4_4") (pintype "bidirectional"))
      (node (ref "J67") (pin "4") (pinfunction "4_4") (pintype "bidirectional"))
      (node (ref "J68") (pin "4") (pinfunction "4_4") (pintype "bidirectional"))
      (node (ref "J69") (pin "4") (pinfunction "4_4") (pintype "bidirectional"))
      (node (ref "J7") (pin "4") (pinfunction "4_4") (pintype "bidirectional"))
      (node (ref "J70") (pin "4") (pinfunction "4_4") (pintype "bidirectional"))
      (node (ref "J71") (pin "4") (pinfunction "4_4") (pintype "bidirectional"))
      (node (ref "J72") (pin "4") (pinfunction "4_4") (pintype "bidirectional"))
      (node (ref "J73") (pin "4") (pinfunction "4_4") (pintype "bidirectional"))
      (node (ref "J74") (pin "4") (pinfunction "4_4") (pintype "bidirectional"))
      (node (ref "J75") (pin "4") (pinfunction "4_4") (pintype "bidirectional"))
      (node (ref "J76") (pin "4") (pinfunction "4_4") (pintype "bidirectional"))
      (node (ref "J77") (pin "4") (pinfunction "4_4") (pintype "bidirectional"))
      (node (ref "J78") (pin "4") (pinfunction "4_4") (pintype "bidirectional"))
      (node (ref "J79") (pin "4") (pinfunction "4_4") (pintype "bidirectional"))
      (node (ref "J8") (pin "4") (pinfunction "4_4") (pintype "bidirectional"))
      (node (ref "J80") (pin "4") (pinfunction "4_4") (pintype "bidirectional"))
      (node (ref "J81") (pin "4") (pinfunction "4_4") (pintype "bidirectional"))
      (node (ref "J82") (pin "4") (pinfunction "4_4") (pintype "bidirectional"))
      (node (ref "J83") (pin "4") (pinfunction "4_4") (pintype "bidirectional"))
      (node (ref "J84") (pin "4") (pinfunction "4_4") (pintype "bidirectional"))
      (node (ref "J85") (pin "4") (pinfunction "4_4") (pintype "bidirectional"))
      (node (ref "J86") (pin "4") (pinfunction "4_4") (pintype "bidirectional"))
      (node (ref "J87") (pin "4") (pinfunction "4_4") (pintype "bidirectional"))
      (node (ref "J88") (pin "4") (pinfunction "4_4") (pintype "bidirectional"))
      (node (ref "J89") (pin "4") (pinfunction "4_4") (pintype "bidirectional"))
      (node (ref "J9") (pin "4") (pinfunction "4_4") (pintype "bidirectional"))
      (node (ref "J90") (pin "4") (pinfunction "4_4") (pintype "bidirectional"))
      (node (ref "J91") (pin "4") (pinfunction "4_4") (pintype "bidirectional"))
      (node (ref "J92") (pin "4") (pinfunction "4_4") (pintype "bidirectional"))
      (node (ref "J93") (pin "4") (pinfunction "4_4") (pintype "bidirectional"))
      (node (ref "J94") (pin "4") (pinfunction "4_4") (pintype "bidirectional"))
      (node (ref "J95") (pin "4") (pinfunction "4_4") (pintype "bidirectional"))
      (node (ref "J96") (pin "4") (pinfunction "4_4") (pintype "bidirectional"))
      (node (ref "J97") (pin "4") (pinfunction "4_4") (pintype "bidirectional"))
      (node (ref "J98") (pin "4") (pinfunction "4_4") (pintype "bidirectional"))
      (node (ref "J99") (pin "4") (pinfunction "4_4") (pintype "bidirectional"))
      (node (ref "JOIN_WIFI") (pin "P$2") (pinfunction "B0_P$2") (pintype "bidirectional"))
      (node (ref "JOIN_WIFI") (pin "P$3") (pinfunction "B1_P$3") (pintype "bidirectional"))
      (node (ref "JP1") (pin "2") (pinfunction "2_2") (pintype "passive"))
      (node (ref "JP2") (pin "4") (pinfunction "4_4") (pintype "passive"))
      (node (ref "JP3") (pin "2") (pinfunction "2_2") (pintype "passive"))
      (node (ref "JP4") (pin "4") (pinfunction "4_4") (pintype "passive"))
      (node (ref "M1") (pin "GND") (pinfunction "GND_GND") (pintype "bidirectional"))
      (node (ref "ONLINE/OFFLINE") (pin "3") (pinfunction "S_3") (pintype "passive"))
      (node (ref "R10") (pin "2") (pinfunction "2_2") (pintype "bidirectional"))
      (node (ref "R12") (pin "1") (pinfunction "1_1") (pintype "bidirectional"))
      (node (ref "R17") (pin "2") (pinfunction "2_2") (pintype "bidirectional"))
      (node (ref "R19") (pin "1") (pinfunction "1_1") (pintype "bidirectional"))
      (node (ref "R2") (pin "2") (pinfunction "2_2") (pintype "bidirectional"))
      (node (ref "R5") (pin "2") (pinfunction "2_2") (pintype "bidirectional"))
      (node (ref "TER_CONN") (pin "2_1") (pinfunction "2_2_1") (pintype "bidirectional"))
      (node (ref "TER_CONN") (pin "2_2") (pinfunction "2_2_2") (pintype "bidirectional"))
      (node (ref "TER_CONN") (pin "2_3") (pinfunction "2_2_3") (pintype "bidirectional"))
      (node (ref "TER_CONN") (pin "2_4") (pinfunction "2_2_4") (pintype "bidirectional"))
      (node (ref "U$4") (pin "1") (pinfunction "GND_1") (pintype "power_in"))
      (node (ref "U$4") (pin "2") (pinfunction "GND_2") (pintype "power_in"))
      (node (ref "U$4") (pin "47") (pinfunction "GND_47") (pintype "power_in"))
      (node (ref "U$4") (pin "48") (pinfunction "GND_48") (pintype "power_in"))
      (node (ref "U$4") (pin "89") (pinfunction "GND_89") (pintype "power_in"))
      (node (ref "U$4") (pin "90") (pinfunction "GND_90") (pintype "power_in"))
      (node (ref "U$4") (pin "91") (pinfunction "GND_91") (pintype "power_in"))
      (node (ref "U$4") (pin "92") (pinfunction "GND_92") (pintype "power_in"))
      (node (ref "U1") (pin "COM1") (pinfunction "COM1_COM1") (pintype "bidirectional"))
      (node (ref "U1") (pin "COM2") (pinfunction "COM2_COM2") (pintype "bidirectional"))
      (node (ref "U1") (pin "COM3") (pinfunction "COM3_COM3") (pintype "bidirectional"))
      (node (ref "U1") (pin "COM4") (pinfunction "COM4_COM4") (pintype "bidirectional"))
      (node (ref "U2") (pin "11") (pinfunction "GND_11") (pintype "bidirectional"))
      (node (ref "U3") (pin "4") (pinfunction "V+_4") (pintype "power_in"))
    )
    (net (code "30") (name "MICROPH") (class "Default")
      (node (ref "JP2") (pin "7") (pinfunction "7_7") (pintype "passive"))
      (node (ref "JP4") (pin "7") (pinfunction "7_7") (pintype "passive"))
      (node (ref "R9") (pin "1") (pinfunction "1_1") (pintype "bidirectional"))
    )
    (net (code "31") (name "MODE") (class "Default")
      (node (ref "JOIN_WIFI") (pin "P$1") (pinfunction "A0_P$1") (pintype "bidirectional"))
      (node (ref "JOIN_WIFI") (pin "P$4") (pinfunction "A1_P$4") (pintype "bidirectional"))
      (node (ref "JP2") (pin "8") (pinfunction "8_8") (pintype "passive"))
      (node (ref "JP4") (pin "8") (pinfunction "8_8") (pintype "passive"))
      (node (ref "R16") (pin "2") (pinfunction "2_2") (pintype "bidirectional"))
    )
    (net (code "32") (name "Net-(C9-Pad1)") (class "Default")
      (node (ref "C9") (pin "1") (pinfunction "1_1") (pintype "bidirectional"))
      (node (ref "M1") (pin "IN") (pinfunction "IN_IN") (pintype "bidirectional"))
      (node (ref "R13") (pin "1") (pinfunction "1_1") (pintype "bidirectional"))
    )
    (net (code "33") (name "Net-(C16-Pad2)") (class "Default")
      (node (ref "C16") (pin "2") (pinfunction "2_2") (pintype "bidirectional"))
      (node (ref "R21") (pin "1") (pinfunction "1_1") (pintype "bidirectional"))
    )
    (net (code "34") (name "Net-(C17-Pad1)") (class "Default")
      (node (ref "C17") (pin "1") (pinfunction "1_1") (pintype "bidirectional"))
      (node (ref "C19") (pin "2") (pinfunction "2_2") (pintype "bidirectional"))
      (node (ref "D1") (pin "3") (pinfunction "3_3") (pintype "passive"))
      (node (ref "R25") (pin "2") (pinfunction "2_2") (pintype "bidirectional"))
    )
    (net (code "35") (name "Net-(C17-Pad2)") (class "Default")
      (node (ref "C17") (pin "2") (pinfunction "2_2") (pintype "bidirectional"))
      (node (ref "R26") (pin "1") (pinfunction "1_1") (pintype "bidirectional"))
    )
    (net (code "36") (name "Net-(D1-Pad1)") (class "Default")
      (node (ref "D1") (pin "1") (pinfunction "1_1") (pintype "passive"))
      (node (ref "D1") (pin "2") (pinfunction "2_2") (pintype "passive"))
      (node (ref "R9") (pin "2") (pinfunction "2_2") (pintype "bidirectional"))
    )
    (net (code "37") (name "Net-(J1-Pad3)") (class "Default")
      (node (ref "J1") (pin "3") (pinfunction "3_3") (pintype "bidirectional"))
      (node (ref "J2") (pin "2") (pinfunction "2_2") (pintype "bidirectional"))
    )
    (net (code "38") (name "Net-(J2-Pad3)") (class "Default")
      (node (ref "J2") (pin "3") (pinfunction "3_3") (pintype "bidirectional"))
      (node (ref "J3") (pin "2") (pinfunction "2_2") (pintype "bidirectional"))
    )
    (net (code "39") (name "Net-(J3-Pad3)") (class "Default")
      (node (ref "J3") (pin "3") (pinfunction "3_3") (pintype "bidirectional"))
      (node (ref "J4") (pin "2") (pinfunction "2_2") (pintype "bidirectional"))
    )
    (net (code "40") (name "Net-(J4-Pad3)") (class "Default")
      (node (ref "J4") (pin "3") (pinfunction "3_3") (pintype "bidirectional"))
      (node (ref "J5") (pin "2") (pinfunction "2_2") (pintype "bidirectional"))
    )
    (net (code "41") (name "Net-(J5-Pad3)") (class "Default")
      (node (ref "J5") (pin "3") (pinfunction "3_3") (pintype "bidirectional"))
      (node (ref "J6") (pin "2") (pinfunction "2_2") (pintype "bidirectional"))
    )
    (net (code "42") (name "Net-(J6-Pad3)") (class "Default")
      (node (ref "J6") (pin "3") (pinfunction "3_3") (pintype "bidirectional"))
      (node (ref "J7") (pin "2") (pinfunction "2_2") (pintype "bidirectional"))
    )
    (net (code "43") (name "Net-(J7-Pad3)") (class "Default")
      (node (ref "J7") (pin "3") (pinfunction "3_3") (pintype "bidirectional"))
      (node (ref "J8") (pin "2") (pinfunction "2_2") (pintype "bidirectional"))
    )
    (net (code "44") (name "Net-(J8-Pad3)") (class "Default")
      (node (ref "J8") (pin "3") (pinfunction "3_3") (pintype "bidirectional"))
      (node (ref "J9") (pin "2") (pinfunction "2_2") (pintype "bidirectional"))
    )
    (net (code "45") (name "Net-(J10-Pad2)") (class "Default")
      (node (ref "J10") (pin "2") (pinfunction "2_2") (pintype "bidirectional"))
      (node (ref "J9") (pin "3") (pinfunction "3_3") (pintype "bidirectional"))
    )
    (net (code "46") (name "Net-(J10-Pad3)") (class "Default")
      (node (ref "J10") (pin "3") (pinfunction "3_3") (pintype "bidirectional"))
      (node (ref "J11") (pin "2") (pinfunction "2_2") (pintype "bidirectional"))
    )
    (net (code "47") (name "Net-(J11-Pad3)") (class "Default")
      (node (ref "J11") (pin "3") (pinfunction "3_3") (pintype "bidirectional"))
      (node (ref "J12") (pin "2") (pinfunction "2_2") (pintype "bidirectional"))
    )
    (net (code "48") (name "Net-(J12-Pad3)") (class "Default")
      (node (ref "J12") (pin "3") (pinfunction "3_3") (pintype "bidirectional"))
      (node (ref "J13") (pin "2") (pinfunction "2_2") (pintype "bidirectional"))
    )
    (net (code "49") (name "Net-(J13-Pad3)") (class "Default")
      (node (ref "J13") (pin "3") (pinfunction "3_3") (pintype "bidirectional"))
      (node (ref "J14") (pin "2") (pinfunction "2_2") (pintype "bidirectional"))
    )
    (net (code "50") (name "Net-(J14-Pad3)") (class "Default")
      (node (ref "J14") (pin "3") (pinfunction "3_3") (pintype "bidirectional"))
      (node (ref "J15") (pin "2") (pinfunction "2_2") (pintype "bidirectional"))
    )
    (net (code "51") (name "Net-(J15-Pad3)") (class "Default")
      (node (ref "J15") (pin "3") (pinfunction "3_3") (pintype "bidirectional"))
      (node (ref "J16") (pin "2") (pinfunction "2_2") (pintype "bidirectional"))
    )
    (net (code "52") (name "Net-(J16-Pad3)") (class "Default")
      (node (ref "J16") (pin "3") (pinfunction "3_3") (pintype "bidirectional"))
      (node (ref "J17") (pin "2") (pinfunction "2_2") (pintype "bidirectional"))
    )
    (net (code "53") (name "Net-(J17-Pad3)") (class "Default")
      (node (ref "J17") (pin "3") (pinfunction "3_3") (pintype "bidirectional"))
      (node (ref "J18") (pin "2") (pinfunction "2_2") (pintype "bidirectional"))
    )
    (net (code "54") (name "Net-(J18-Pad3)") (class "Default")
      (node (ref "J18") (pin "3") (pinfunction "3_3") (pintype "bidirectional"))
      (node (ref "J19") (pin "2") (pinfunction "2_2") (pintype "bidirectional"))
    )
    (net (code "55") (name "Net-(J19-Pad3)") (class "Default")
      (node (ref "J19") (pin "3") (pinfunction "3_3") (pintype "bidirectional"))
      (node (ref "J20") (pin "2") (pinfunction "2_2") (pintype "bidirectional"))
    )
    (net (code "56") (name "Net-(J20-Pad3)") (class "Default")
      (node (ref "J20") (pin "3") (pinfunction "3_3") (pintype "bidirectional"))
      (node (ref "J21") (pin "2") (pinfunction "2_2") (pintype "bidirectional"))
    )
    (net (code "57") (name "Net-(J21-Pad3)") (class "Default")
      (node (ref "J21") (pin "3") (pinfunction "3_3") (pintype "bidirectional"))
      (node (ref "J22") (pin "2") (pinfunction "2_2") (pintype "bidirectional"))
    )
    (net (code "58") (name "Net-(J22-Pad3)") (class "Default")
      (node (ref "J22") (pin "3") (pinfunction "3_3") (pintype "bidirectional"))
      (node (ref "J23") (pin "2") (pinfunction "2_2") (pintype "bidirectional"))
    )
    (net (code "59") (name "Net-(J23-Pad3)") (class "Default")
      (node (ref "J23") (pin "3") (pinfunction "3_3") (pintype "bidirectional"))
      (node (ref "J24") (pin "2") (pinfunction "2_2") (pintype "bidirectional"))
    )
    (net (code "60") (name "Net-(J24-Pad3)") (class "Default")
      (node (ref "J24") (pin "3") (pinfunction "3_3") (pintype "bidirectional"))
      (node (ref "J25") (pin "2") (pinfunction "2_2") (pintype "bidirectional"))
    )
    (net (code "61") (name "Net-(J25-Pad3)") (class "Default")
      (node (ref "J25") (pin "3") (pinfunction "3_3") (pintype "bidirectional"))
      (node (ref "J26") (pin "2") (pinfunction "2_2") (pintype "bidirectional"))
    )
    (net (code "62") (name "Net-(J26-Pad3)") (class "Default")
      (node (ref "J26") (pin "3") (pinfunction "3_3") (pintype "bidirectional"))
      (node (ref "J27") (pin "2") (pinfunction "2_2") (pintype "bidirectional"))
    )
    (net (code "63") (name "Net-(J27-Pad3)") (class "Default")
      (node (ref "J27") (pin "3") (pinfunction "3_3") (pintype "bidirectional"))
      (node (ref "J28") (pin "2") (pinfunction "2_2") (pintype "bidirectional"))
    )
    (net (code "64") (name "Net-(J28-Pad3)") (class "Default")
      (node (ref "J28") (pin "3") (pinfunction "3_3") (pintype "bidirectional"))
      (node (ref "J29") (pin "2") (pinfunction "2_2") (pintype "bidirectional"))
    )
    (net (code "65") (name "Net-(J29-Pad3)") (class "Default")
      (node (ref "J29") (pin "3") (pinfunction "3_3") (pintype "bidirectional"))
      (node (ref "J30") (pin "2") (pinfunction "2_2") (pintype "bidirectional"))
    )
    (net (code "66") (name "Net-(J30-Pad3)") (class "Default")
      (node (ref "J30") (pin "3") (pinfunction "3_3") (pintype "bidirectional"))
      (node (ref "J31") (pin "2") (pinfunction "2_2") (pintype "bidirectional"))
    )
    (net (code "67") (name "Net-(J31-Pad3)") (class "Default")
      (node (ref "J31") (pin "3") (pinfunction "3_3") (pintype "bidirectional"))
      (node (ref "J32") (pin "2") (pinfunction "2_2") (pintype "bidirectional"))
    )
    (net (code "68") (name "Net-(J33-Pad3)") (class "Default")
      (node (ref "J33") (pin "3") (pinfunction "3_3") (pintype "bidirectional"))
      (node (ref "J34") (pin "2") (pinfunction "2_2") (pintype "bidirectional"))
    )
    (net (code "69") (name "Net-(J34-Pad3)") (class "Default")
      (node (ref "J34") (pin "3") (pinfunction "3_3") (pintype "bidirectional"))
      (node (ref "J35") (pin "2") (pinfunction "2_2") (pintype "bidirectional"))
    )
    (net (code "70") (name "Net-(J35-Pad3)") (class "Default")
      (node (ref "J35") (pin "3") (pinfunction "3_3") (pintype "bidirectional"))
      (node (ref "J36") (pin "2") (pinfunction "2_2") (pintype "bidirectional"))
    )
    (net (code "71") (name "Net-(J36-Pad3)") (class "Default")
      (node (ref "J36") (pin "3") (pinfunction "3_3") (pintype "bidirectional"))
      (node (ref "J37") (pin "2") (pinfunction "2_2") (pintype "bidirectional"))
    )
    (net (code "72") (name "Net-(J37-Pad3)") (class "Default")
      (node (ref "J37") (pin "3") (pinfunction "3_3") (pintype "bidirectional"))
      (node (ref "J38") (pin "2") (pinfunction "2_2") (pintype "bidirectional"))
    )
    (net (code "73") (name "Net-(J38-Pad3)") (class "Default")
      (node (ref "J38") (pin "3") (pinfunction "3_3") (pintype "bidirectional"))
      (node (ref "J39") (pin "2") (pinfunction "2_2") (pintype "bidirectional"))
    )
    (net (code "74") (name "Net-(J39-Pad3)") (class "Default")
      (node (ref "J39") (pin "3") (pinfunction "3_3") (pintype "bidirectional"))
      (node (ref "J40") (pin "2") (pinfunction "2_2") (pintype "bidirectional"))
    )
    (net (code "75") (name "Net-(J40-Pad3)") (class "Default")
      (node (ref "J40") (pin "3") (pinfunction "3_3") (pintype "bidirectional"))
      (node (ref "J41") (pin "2") (pinfunction "2_2") (pintype "bidirectional"))
    )
    (net (code "76") (name "Net-(J41-Pad3)") (class "Default")
      (node (ref "J41") (pin "3") (pinfunction "3_3") (pintype "bidirectional"))
      (node (ref "J42") (pin "2") (pinfunction "2_2") (pintype "bidirectional"))
    )
    (net (code "77") (name "Net-(J42-Pad3)") (class "Default")
      (node (ref "J42") (pin "3") (pinfunction "3_3") (pintype "bidirectional"))
      (node (ref "J43") (pin "2") (pinfunction "2_2") (pintype "bidirectional"))
    )
    (net (code "78") (name "Net-(J43-Pad3)") (class "Default")
      (node (ref "J43") (pin "3") (pinfunction "3_3") (pintype "bidirectional"))
      (node (ref "J44") (pin "2") (pinfunction "2_2") (pintype "bidirectional"))
    )
    (net (code "79") (name "Net-(J44-Pad3)") (class "Default")
      (node (ref "J44") (pin "3") (pinfunction "3_3") (pintype "bidirectional"))
      (node (ref "J45") (pin "2") (pinfunction "2_2") (pintype "bidirectional"))
    )
    (net (code "80") (name "Net-(J45-Pad3)") (class "Default")
      (node (ref "J45") (pin "3") (pinfunction "3_3") (pintype "bidirectional"))
      (node (ref "J46") (pin "2") (pinfunction "2_2") (pintype "bidirectional"))
    )
    (net (code "81") (name "Net-(J46-Pad3)") (class "Default")
      (node (ref "J46") (pin "3") (pinfunction "3_3") (pintype "bidirectional"))
      (node (ref "J47") (pin "2") (pinfunction "2_2") (pintype "bidirectional"))
    )
    (net (code "82") (name "Net-(J47-Pad3)") (class "Default")
      (node (ref "J47") (pin "3") (pinfunction "3_3") (pintype "bidirectional"))
      (node (ref "J48") (pin "2") (pinfunction "2_2") (pintype "bidirectional"))
    )
    (net (code "83") (name "Net-(J48-Pad3)") (class "Default")
      (node (ref "J48") (pin "3") (pinfunction "3_3") (pintype "bidirectional"))
      (node (ref "J49") (pin "2") (pinfunction "2_2") (pintype "bidirectional"))
    )
    (net (code "84") (name "Net-(J49-Pad3)") (class "Default")
      (node (ref "J49") (pin "3") (pinfunction "3_3") (pintype "bidirectional"))
      (node (ref "J50") (pin "2") (pinfunction "2_2") (pintype "bidirectional"))
    )
    (net (code "85") (name "Net-(J50-Pad3)") (class "Default")
      (node (ref "J50") (pin "3") (pinfunction "3_3") (pintype "bidirectional"))
      (node (ref "J51") (pin "2") (pinfunction "2_2") (pintype "bidirectional"))
    )
    (net (code "86") (name "Net-(J51-Pad3)") (class "Default")
      (node (ref "J51") (pin "3") (pinfunction "3_3") (pintype "bidirectional"))
      (node (ref "J52") (pin "2") (pinfunction "2_2") (pintype "bidirectional"))
    )
    (net (code "87") (name "Net-(J52-Pad3)") (class "Default")
      (node (ref "J52") (pin "3") (pinfunction "3_3") (pintype "bidirectional"))
      (node (ref "J53") (pin "2") (pinfunction "2_2") (pintype "bidirectional"))
    )
    (net (code "88") (name "Net-(J53-Pad3)") (class "Default")
      (node (ref "J53") (pin "3") (pinfunction "3_3") (pintype "bidirectional"))
      (node (ref "J54") (pin "2") (pinfunction "2_2") (pintype "bidirectional"))
    )
    (net (code "89") (name "Net-(J54-Pad3)") (class "Default")
      (node (ref "J54") (pin "3") (pinfunction "3_3") (pintype "bidirectional"))
      (node (ref "J55") (pin "2") (pinfunction "2_2") (pintype "bidirectional"))
    )
    (net (code "90") (name "Net-(J55-Pad3)") (class "Default")
      (node (ref "J55") (pin "3") (pinfunction "3_3") (pintype "bidirectional"))
      (node (ref "J56") (pin "2") (pinfunction "2_2") (pintype "bidirectional"))
    )
    (net (code "91") (name "Net-(J56-Pad3)") (class "Default")
      (node (ref "J56") (pin "3") (pinfunction "3_3") (pintype "bidirectional"))
      (node (ref "J57") (pin "2") (pinfunction "2_2") (pintype "bidirectional"))
    )
    (net (code "92") (name "Net-(J57-Pad3)") (class "Default")
      (node (ref "J57") (pin "3") (pinfunction "3_3") (pintype "bidirectional"))
      (node (ref "J58") (pin "2") (pinfunction "2_2") (pintype "bidirectional"))
    )
    (net (code "93") (name "Net-(J58-Pad3)") (class "Default")
      (node (ref "J58") (pin "3") (pinfunction "3_3") (pintype "bidirectional"))
      (node (ref "J59") (pin "2") (pinfunction "2_2") (pintype "bidirectional"))
    )
    (net (code "94") (name "Net-(J59-Pad3)") (class "Default")
      (node (ref "J59") (pin "3") (pinfunction "3_3") (pintype "bidirectional"))
      (node (ref "J60") (pin "2") (pinfunction "2_2") (pintype "bidirectional"))
    )
    (net (code "95") (name "Net-(J60-Pad3)") (class "Default")
      (node (ref "J60") (pin "3") (pinfunction "3_3") (pintype "bidirectional"))
      (node (ref "J61") (pin "2") (pinfunction "2_2") (pintype "bidirectional"))
    )
    (net (code "96") (name "Net-(J61-Pad3)") (class "Default")
      (node (ref "J61") (pin "3") (pinfunction "3_3") (pintype "bidirectional"))
      (node (ref "J62") (pin "2") (pinfunction "2_2") (pintype "bidirectional"))
    )
    (net (code "97") (name "Net-(J62-Pad3)") (class "Default")
      (node (ref "J62") (pin "3") (pinfunction "3_3") (pintype "bidirectional"))
      (node (ref "J63") (pin "2") (pinfunction "2_2") (pintype "bidirectional"))
    )
    (net (code "98") (name "Net-(J63-Pad3)") (class "Default")
      (node (ref "J63") (pin "3") (pinfunction "3_3") (pintype "bidirectional"))
      (node (ref "J64") (pin "2") (pinfunction "2_2") (pintype "bidirectional"))
    )
    (net (code "99") (name "Net-(J65-Pad3)") (class "Default")
      (node (ref "J65") (pin "3") (pinfunction "3_3") (pintype "bidirectional"))
      (node (ref "J66") (pin "2") (pinfunction "2_2") (pintype "bidirectional"))
    )
    (net (code "100") (name "Net-(J66-Pad3)") (class "Default")
      (node (ref "J66") (pin "3") (pinfunction "3_3") (pintype "bidirectional"))
      (node (ref "J67") (pin "2") (pinfunction "2_2") (pintype "bidirectional"))
    )
    (net (code "101") (name "Net-(J67-Pad3)") (class "Default")
      (node (ref "J67") (pin "3") (pinfunction "3_3") (pintype "bidirectional"))
      (node (ref "J68") (pin "2") (pinfunction "2_2") (pintype "bidirectional"))
    )
    (net (code "102") (name "Net-(J68-Pad3)") (class "Default")
      (node (ref "J68") (pin "3") (pinfunction "3_3") (pintype "bidirectional"))
      (node (ref "J69") (pin "2") (pinfunction "2_2") (pintype "bidirectional"))
    )
    (net (code "103") (name "Net-(J69-Pad3)") (class "Default")
      (node (ref "J69") (pin "3") (pinfunction "3_3") (pintype "bidirectional"))
      (node (ref "J70") (pin "2") (pinfunction "2_2") (pintype "bidirectional"))
    )
    (net (code "104") (name "Net-(J70-Pad3)") (class "Default")
      (node (ref "J70") (pin "3") (pinfunction "3_3") (pintype "bidirectional"))
      (node (ref "J71") (pin "2") (pinfunction "2_2") (pintype "bidirectional"))
    )
    (net (code "105") (name "Net-(J71-Pad3)") (class "Default")
      (node (ref "J71") (pin "3") (pinfunction "3_3") (pintype "bidirectional"))
      (node (ref "J72") (pin "2") (pinfunction "2_2") (pintype "bidirectional"))
    )
    (net (code "106") (name "Net-(J72-Pad3)") (class "Default")
      (node (ref "J72") (pin "3") (pinfunction "3_3") (pintype "bidirectional"))
      (node (ref "J73") (pin "2") (pinfunction "2_2") (pintype "bidirectional"))
    )
    (net (code "107") (name "Net-(J73-Pad3)") (class "Default")
      (node (ref "J73") (pin "3") (pinfunction "3_3") (pintype "bidirectional"))
      (node (ref "J74") (pin "2") (pinfunction "2_2") (pintype "bidirectional"))
    )
    (net (code "108") (name "Net-(J74-Pad3)") (class "Default")
      (node (ref "J74") (pin "3") (pinfunction "3_3") (pintype "bidirectional"))
      (node (ref "J75") (pin "2") (pinfunction "2_2") (pintype "bidirectional"))
    )
    (net (code "109") (name "Net-(J75-Pad3)") (class "Default")
      (node (ref "J75") (pin "3") (pinfunction "3_3") (pintype "bidirectional"))
      (node (ref "J76") (pin "2") (pinfunction "2_2") (pintype "bidirectional"))
    )
    (net (code "110") (name "Net-(J76-Pad3)") (class "Default")
      (node (ref "J76") (pin "3") (pinfunction "3_3") (pintype "bidirectional"))
      (node (ref "J77") (pin "2") (pinfunction "2_2") (pintype "bidirectional"))
    )
    (net (code "111") (name "Net-(J77-Pad3)") (class "Default")
      (node (ref "J77") (pin "3") (pinfunction "3_3") (pintype "bidirectional"))
      (node (ref "J78") (pin "2") (pinfunction "2_2") (pintype "bidirectional"))
    )
    (net (code "112") (name "Net-(J78-Pad3)") (class "Default")
      (node (ref "J78") (pin "3") (pinfunction "3_3") (pintype "bidirectional"))
      (node (ref "J79") (pin "2") (pinfunction "2_2") (pintype "bidirectional"))
    )
    (net (code "113") (name "Net-(J79-Pad3)") (class "Default")
      (node (ref "J79") (pin "3") (pinfunction "3_3") (pintype "bidirectional"))
      (node (ref "J80") (pin "2") (pinfunction "2_2") (pintype "bidirectional"))
    )
    (net (code "114") (name "Net-(J80-Pad3)") (class "Default")
      (node (ref "J80") (pin "3") (pinfunction "3_3") (pintype "bidirectional"))
      (node (ref "J81") (pin "2") (pinfunction "2_2") (pintype "bidirectional"))
    )
    (net (code "115") (name "Net-(J81-Pad3)") (class "Default")
      (node (ref "J81") (pin "3") (pinfunction "3_3") (pintype "bidirectional"))
      (node (ref "J82") (pin "2") (pinfunction "2_2") (pintype "bidirectional"))
    )
    (net (code "116") (name "Net-(J82-Pad3)") (class "Default")
      (node (ref "J82") (pin "3") (pinfunction "3_3") (pintype "bidirectional"))
      (node (ref "J83") (pin "2") (pinfunction "2_2") (pintype "bidirectional"))
    )
    (net (code "117") (name "Net-(J83-Pad3)") (class "Default")
      (node (ref "J83") (pin "3") (pinfunction "3_3") (pintype "bidirectional"))
      (node (ref "J84") (pin "2") (pinfunction "2_2") (pintype "bidirectional"))
    )
    (net (code "118") (name "Net-(J84-Pad3)") (class "Default")
      (node (ref "J84") (pin "3") (pinfunction "3_3") (pintype "bidirectional"))
      (node (ref "J85") (pin "2") (pinfunction "2_2") (pintype "bidirectional"))
    )
    (net (code "119") (name "Net-(J85-Pad3)") (class "Default")
      (node (ref "J85") (pin "3") (pinfunction "3_3") (pintype "bidirectional"))
      (node (ref "J86") (pin "2") (pinfunction "2_2") (pintype "bidirectional"))
    )
    (net (code "120") (name "Net-(J86-Pad3)") (class "Default")
      (node (ref "J86") (pin "3") (pinfunction "3_3") (pintype "bidirectional"))
      (node (ref "J87") (pin "2") (pinfunction "2_2") (pintype "bidirectional"))
    )
    (net (code "121") (name "Net-(J87-Pad3)") (class "Default")
      (node (ref "J87") (pin "3") (pinfunction "3_3") (pintype "bidirectional"))
      (node (ref "J88") (pin "2") (pinfunction "2_2") (pintype "bidirectional"))
    )
    (net (code "122") (name "Net-(J88-Pad3)") (class "Default")
      (node (ref "J88") (pin "3") (pinfunction "3_3") (pintype "bidirectional"))
      (node (ref "J89") (pin "2") (pinfunction "2_2") (pintype "bidirectional"))
    )
    (net (code "123") (name "Net-(J89-Pad3)") (class "Default")
      (node (ref "J89") (pin "3") (pinfunction "3_3") (pintype "bidirectional"))
      (node (ref "J90") (pin "2") (pinfunction "2_2") (pintype "bidirectional"))
    )
    (net (code "124") (name "Net-(J90-Pad3)") (class "Default")
      (node (ref "J90") (pin "3") (pinfunction "3_3") (pintype "bidirectional"))
      (node (ref "J91") (pin "2") (pinfunction "2_2") (pintype "bidirectional"))
    )
    (net (code "125") (name "Net-(J91-Pad3)") (class "Default")
      (node (ref "J91") (pin "3") (pinfunction "3_3") (pintype "bidirectional"))
      (node (ref "J92") (pin "2") (pinfunction "2_2") (pintype "bidirectional"))
    )
    (net (code "126") (name "Net-(J92-Pad3)") (class "Default")
      (node (ref "J92") (pin "3") (pinfunction "3_3") (pintype "bidirectional"))
      (node (ref "J93") (pin "2") (pinfunction "2_2") (pintype "bidirectional"))
    )
    (net (code "127") (name "Net-(J93-Pad3)") (class "Default")
      (node (ref "J93") (pin "3") (pinfunction "3_3") (pintype "bidirectional"))
      (node (ref "J94") (pin "2") (pinfunction "2_2") (pintype "bidirectional"))
    )
    (net (code "128") (name "Net-(J94-Pad3)") (class "Default")
      (node (ref "J94") (pin "3") (pinfunction "3_3") (pintype "bidirectional"))
      (node (ref "J95") (pin "2") (pinfunction "2_2") (pintype "bidirectional"))
    )
    (net (code "129") (name "Net-(J95-Pad3)") (class "Default")
      (node (ref "J95") (pin "3") (pinfunction "3_3") (pintype "bidirectional"))
      (node (ref "J96") (pin "2") (pinfunction "2_2") (pintype "bidirectional"))
    )
    (net (code "130") (name "Net-(J97-Pad3)") (class "Default")
      (node (ref "J97") (pin "3") (pinfunction "3_3") (pintype "bidirectional"))
      (node (ref "J98") (pin "2") (pinfunction "2_2") (pintype "bidirectional"))
    )
    (net (code "131") (name "Net-(J98-Pad3)") (class "Default")
      (node (ref "J98") (pin "3") (pinfunction "3_3") (pintype "bidirectional"))
      (node (ref "J99") (pin "2") (pinfunction "2_2") (pintype "bidirectional"))
    )
    (net (code "132") (name "Net-(J100-Pad2)") (class "Default")
      (node (ref "J100") (pin "2") (pinfunction "2_2") (pintype "bidirectional"))
      (node (ref "J99") (pin "3") (pinfunction "3_3") (pintype "bidirectional"))
    )
    (net (code "133") (name "Net-(J100-Pad3)") (class "Default")
      (node (ref "J100") (pin "3") (pinfunction "3_3") (pintype "bidirectional"))
      (node (ref "J101") (pin "2") (pinfunction "2_2") (pintype "bidirectional"))
    )
    (net (code "134") (name "Net-(J101-Pad3)") (class "Default")
      (node (ref "J101") (pin "3") (pinfunction "3_3") (pintype "bidirectional"))
      (node (ref "J102") (pin "2") (pinfunction "2_2") (pintype "bidirectional"))
    )
    (net (code "135") (name "Net-(J102-Pad3)") (class "Default")
      (node (ref "J102") (pin "3") (pinfunction "3_3") (pintype "bidirectional"))
      (node (ref "J103") (pin "2") (pinfunction "2_2") (pintype "bidirectional"))
    )
    (net (code "136") (name "Net-(J103-Pad3)") (class "Default")
      (node (ref "J103") (pin "3") (pinfunction "3_3") (pintype "bidirectional"))
      (node (ref "J104") (pin "2") (pinfunction "2_2") (pintype "bidirectional"))
    )
    (net (code "137") (name "Net-(J104-Pad3)") (class "Default")
      (node (ref "J104") (pin "3") (pinfunction "3_3") (pintype "bidirectional"))
      (node (ref "J105") (pin "2") (pinfunction "2_2") (pintype "bidirectional"))
    )
    (net (code "138") (name "Net-(J105-Pad3)") (class "Default")
      (node (ref "J105") (pin "3") (pinfunction "3_3") (pintype "bidirectional"))
      (node (ref "J106") (pin "2") (pinfunction "2_2") (pintype "bidirectional"))
    )
    (net (code "139") (name "Net-(J106-Pad3)") (class "Default")
      (node (ref "J106") (pin "3") (pinfunction "3_3") (pintype "bidirectional"))
      (node (ref "J107") (pin "2") (pinfunction "2_2") (pintype "bidirectional"))
    )
    (net (code "140") (name "Net-(J107-Pad3)") (class "Default")
      (node (ref "J107") (pin "3") (pinfunction "3_3") (pintype "bidirectional"))
      (node (ref "J108") (pin "2") (pinfunction "2_2") (pintype "bidirectional"))
    )
    (net (code "141") (name "Net-(J108-Pad3)") (class "Default")
      (node (ref "J108") (pin "3") (pinfunction "3_3") (pintype "bidirectional"))
      (node (ref "J109") (pin "2") (pinfunction "2_2") (pintype "bidirectional"))
    )
    (net (code "142") (name "Net-(J109-Pad3)") (class "Default")
      (node (ref "J109") (pin "3") (pinfunction "3_3") (pintype "bidirectional"))
      (node (ref "J110") (pin "2") (pinfunction "2_2") (pintype "bidirectional"))
    )
    (net (code "143") (name "Net-(J110-Pad3)") (class "Default")
      (node (ref "J110") (pin "3") (pinfunction "3_3") (pintype "bidirectional"))
      (node (ref "J111") (pin "2") (pinfunction "2_2") (pintype "bidirectional"))
    )
    (net (code "144") (name "Net-(J111-Pad3)") (class "Default")
      (node (ref "J111") (pin "3") (pinfunction "3_3") (pintype "bidirectional"))
      (node (ref "J112") (pin "2") (pinfunction "2_2") (pintype "bidirectional"))
    )
    (net (code "145") (name "Net-(J112-Pad3)") (class "Default")
      (node (ref "J112") (pin "3") (pinfunction "3_3") (pintype "bidirectional"))
      (node (ref "J113") (pin "2") (pinfunction "2_2") (pintype "bidirectional"))
    )
    (net (code "146") (name "Net-(J113-Pad3)") (class "Default")
      (node (ref "J113") (pin "3") (pinfunction "3_3") (pintype "bidirectional"))
      (node (ref "J114") (pin "2") (pinfunction "2_2") (pintype "bidirectional"))
    )
    (net (code "147") (name "Net-(J114-Pad3)") (class "Default")
      (node (ref "J114") (pin "3") (pinfunction "3_3") (pintype "bidirectional"))
      (node (ref "J115") (pin "2") (pinfunction "2_2") (pintype "bidirectional"))
    )
    (net (code "148") (name "Net-(J115-Pad3)") (class "Default")
      (node (ref "J115") (pin "3") (pinfunction "3_3") (pintype "bidirectional"))
      (node (ref "J116") (pin "2") (pinfunction "2_2") (pintype "bidirectional"))
    )
    (net (code "149") (name "Net-(J116-Pad3)") (class "Default")
      (node (ref "J116") (pin "3") (pinfunction "3_3") (pintype "bidirectional"))
      (node (ref "J117") (pin "2") (pinfunction "2_2") (pintype "bidirectional"))
    )
    (net (code "150") (name "Net-(J117-Pad3)") (class "Default")
      (node (ref "J117") (pin "3") (pinfunction "3_3") (pintype "bidirectional"))
      (node (ref "J118") (pin "2") (pinfunction "2_2") (pintype "bidirectional"))
    )
    (net (code "151") (name "Net-(J118-Pad3)") (class "Default")
      (node (ref "J118") (pin "3") (pinfunction "3_3") (pintype "bidirectional"))
      (node (ref "J119") (pin "2") (pinfunction "2_2") (pintype "bidirectional"))
    )
    (net (code "152") (name "Net-(J119-Pad3)") (class "Default")
      (node (ref "J119") (pin "3") (pinfunction "3_3") (pintype "bidirectional"))
      (node (ref "J120") (pin "2") (pinfunction "2_2") (pintype "bidirectional"))
    )
    (net (code "153") (name "Net-(J120-Pad3)") (class "Default")
      (node (ref "J120") (pin "3") (pinfunction "3_3") (pintype "bidirectional"))
      (node (ref "J121") (pin "2") (pinfunction "2_2") (pintype "bidirectional"))
    )
    (net (code "154") (name "Net-(J121-Pad3)") (class "Default")
      (node (ref "J121") (pin "3") (pinfunction "3_3") (pintype "bidirectional"))
      (node (ref "J122") (pin "2") (pinfunction "2_2") (pintype "bidirectional"))
    )
    (net (code "155") (name "Net-(J122-Pad3)") (class "Default")
      (node (ref "J122") (pin "3") (pinfunction "3_3") (pintype "bidirectional"))
      (node (ref "J123") (pin "2") (pinfunction "2_2") (pintype "bidirectional"))
    )
    (net (code "156") (name "Net-(J123-Pad3)") (class "Default")
      (node (ref "J123") (pin "3") (pinfunction "3_3") (pintype "bidirectional"))
      (node (ref "J124") (pin "2") (pinfunction "2_2") (pintype "bidirectional"))
    )
    (net (code "157") (name "Net-(J124-Pad3)") (class "Default")
      (node (ref "J124") (pin "3") (pinfunction "3_3") (pintype "bidirectional"))
      (node (ref "J125") (pin "2") (pinfunction "2_2") (pintype "bidirectional"))
    )
    (net (code "158") (name "Net-(J125-Pad3)") (class "Default")
      (node (ref "J125") (pin "3") (pinfunction "3_3") (pintype "bidirectional"))
      (node (ref "J126") (pin "2") (pinfunction "2_2") (pintype "bidirectional"))
    )
    (net (code "159") (name "Net-(J126-Pad3)") (class "Default")
      (node (ref "J126") (pin "3") (pinfunction "3_3") (pintype "bidirectional"))
      (node (ref "J127") (pin "2") (pinfunction "2_2") (pintype "bidirectional"))
    )
    (net (code "160") (name "Net-(J127-Pad3)") (class "Default")
      (node (ref "J127") (pin "3") (pinfunction "3_3") (pintype "bidirectional"))
      (node (ref "J128") (pin "2") (pinfunction "2_2") (pintype "bidirectional"))
    )
    (net (code "161") (name "Net-(J129-Pad3)") (class "Default")
      (node (ref "J129") (pin "3") (pinfunction "3_3") (pintype "bidirectional"))
      (node (ref "J130") (pin "2") (pinfunction "2_2") (pintype "bidirectional"))
    )
    (net (code "162") (name "Net-(J130-Pad3)") (class "Default")
      (node (ref "J130") (pin "3") (pinfunction "3_3") (pintype "bidirectional"))
      (node (ref "J131") (pin "2") (pinfunction "2_2") (pintype "bidirectional"))
    )
    (net (code "163") (name "Net-(J131-Pad3)") (class "Default")
      (node (ref "J131") (pin "3") (pinfunction "3_3") (pintype "bidirectional"))
      (node (ref "J132") (pin "2") (pinfunction "2_2") (pintype "bidirectional"))
    )
    (net (code "164") (name "Net-(J132-Pad3)") (class "Default")
      (node (ref "J132") (pin "3") (pinfunction "3_3") (pintype "bidirectional"))
      (node (ref "J133") (pin "2") (pinfunction "2_2") (pintype "bidirectional"))
    )
    (net (code "165") (name "Net-(J133-Pad3)") (class "Default")
      (node (ref "J133") (pin "3") (pinfunction "3_3") (pintype "bidirectional"))
      (node (ref "J134") (pin "2") (pinfunction "2_2") (pintype "bidirectional"))
    )
    (net (code "166") (name "Net-(J134-Pad3)") (class "Default")
      (node (ref "J134") (pin "3") (pinfunction "3_3") (pintype "bidirectional"))
      (node (ref "J135") (pin "2") (pinfunction "2_2") (pintype "bidirectional"))
    )
    (net (code "167") (name "Net-(J135-Pad3)") (class "Default")
      (node (ref "J135") (pin "3") (pinfunction "3_3") (pintype "bidirectional"))
      (node (ref "J136") (pin "2") (pinfunction "2_2") (pintype "bidirectional"))
    )
    (net (code "168") (name "Net-(J136-Pad3)") (class "Default")
      (node (ref "J136") (pin "3") (pinfunction "3_3") (pintype "bidirectional"))
      (node (ref "J137") (pin "2") (pinfunction "2_2") (pintype "bidirectional"))
    )
    (net (code "169") (name "Net-(J137-Pad3)") (class "Default")
      (node (ref "J137") (pin "3") (pinfunction "3_3") (pintype "bidirectional"))
      (node (ref "J138") (pin "2") (pinfunction "2_2") (pintype "bidirectional"))
    )
    (net (code "170") (name "Net-(J138-Pad3)") (class "Default")
      (node (ref "J138") (pin "3") (pinfunction "3_3") (pintype "bidirectional"))
      (node (ref "J139") (pin "2") (pinfunction "2_2") (pintype "bidirectional"))
    )
    (net (code "171") (name "Net-(J139-Pad3)") (class "Default")
      (node (ref "J139") (pin "3") (pinfunction "3_3") (pintype "bidirectional"))
      (node (ref "J140") (pin "2") (pinfunction "2_2") (pintype "bidirectional"))
    )
    (net (code "172") (name "Net-(J140-Pad3)") (class "Default")
      (node (ref "J140") (pin "3") (pinfunction "3_3") (pintype "bidirectional"))
      (node (ref "J141") (pin "2") (pinfunction "2_2") (pintype "bidirectional"))
    )
    (net (code "173") (name "Net-(J141-Pad3)") (class "Default")
      (node (ref "J141") (pin "3") (pinfunction "3_3") (pintype "bidirectional"))
      (node (ref "J142") (pin "2") (pinfunction "2_2") (pintype "bidirectional"))
    )
    (net (code "174") (name "Net-(J142-Pad3)") (class "Default")
      (node (ref "J142") (pin "3") (pinfunction "3_3") (pintype "bidirectional"))
      (node (ref "J143") (pin "2") (pinfunction "2_2") (pintype "bidirectional"))
    )
    (net (code "175") (name "Net-(J143-Pad3)") (class "Default")
      (node (ref "J143") (pin "3") (pinfunction "3_3") (pintype "bidirectional"))
      (node (ref "J144") (pin "2") (pinfunction "2_2") (pintype "bidirectional"))
    )
    (net (code "176") (name "Net-(J144-Pad3)") (class "Default")
      (node (ref "J144") (pin "3") (pinfunction "3_3") (pintype "bidirectional"))
      (node (ref "J145") (pin "2") (pinfunction "2_2") (pintype "bidirectional"))
    )
    (net (code "177") (name "Net-(J145-Pad3)") (class "Default")
      (node (ref "J145") (pin "3") (pinfunction "3_3") (pintype "bidirectional"))
      (node (ref "J146") (pin "2") (pinfunction "2_2") (pintype "bidirectional"))
    )
    (net (code "178") (name "Net-(J146-Pad3)") (class "Default")
      (node (ref "J146") (pin "3") (pinfunction "3_3") (pintype "bidirectional"))
      (node (ref "J147") (pin "2") (pinfunction "2_2") (pintype "bidirectional"))
    )
    (net (code "179") (name "Net-(J147-Pad3)") (class "Default")
      (node (ref "J147") (pin "3") (pinfunction "3_3") (pintype "bidirectional"))
      (node (ref "J148") (pin "2") (pinfunction "2_2") (pintype "bidirectional"))
    )
    (net (code "180") (name "Net-(J148-Pad3)") (class "Default")
      (node (ref "J148") (pin "3") (pinfunction "3_3") (pintype "bidirectional"))
      (node (ref "J149") (pin "2") (pinfunction "2_2") (pintype "bidirectional"))
    )
    (net (code "181") (name "Net-(J149-Pad3)") (class "Default")
      (node (ref "J149") (pin "3") (pinfunction "3_3") (pintype "bidirectional"))
      (node (ref "J150") (pin "2") (pinfunction "2_2") (pintype "bidirectional"))
    )
    (net (code "182") (name "Net-(J150-Pad3)") (class "Default")
      (node (ref "J150") (pin "3") (pinfunction "3_3") (pintype "bidirectional"))
      (node (ref "J151") (pin "2") (pinfunction "2_2") (pintype "bidirectional"))
    )
    (net (code "183") (name "Net-(J151-Pad3)") (class "Default")
      (node (ref "J151") (pin "3") (pinfunction "3_3") (pintype "bidirectional"))
      (node (ref "J152") (pin "2") (pinfunction "2_2") (pintype "bidirectional"))
    )
    (net (code "184") (name "Net-(J152-Pad3)") (class "Default")
      (node (ref "J152") (pin "3") (pinfunction "3_3") (pintype "bidirectional"))
      (node (ref "J153") (pin "2") (pinfunction "2_2") (pintype "bidirectional"))
    )
    (net (code "185") (name "Net-(J153-Pad3)") (class "Default")
      (node (ref "J153") (pin "3") (pinfunction "3_3") (pintype "bidirectional"))
      (node (ref "J154") (pin "2") (pinfunction "2_2") (pintype "bidirectional"))
    )
    (net (code "186") (name "Net-(J154-Pad3)") (class "Default")
      (node (ref "J154") (pin "3") (pinfunction "3_3") (pintype "bidirectional"))
      (node (ref "J155") (pin "2") (pinfunction "2_2") (pintype "bidirectional"))
    )
    (net (code "187") (name "Net-(J155-Pad3)") (class "Default")
      (node (ref "J155") (pin "3") (pinfunction "3_3") (pintype "bidirectional"))
      (node (ref "J156") (pin "2") (pinfunction "2_2") (pintype "bidirectional"))
    )
    (net (code "188") (name "Net-(J156-Pad3)") (class "Default")
      (node (ref "J156") (pin "3") (pinfunction "3_3") (pintype "bidirectional"))
      (node (ref "J157") (pin "2") (pinfunction "2_2") (pintype "bidirectional"))
    )
    (net (code "189") (name "Net-(J157-Pad3)") (class "Default")
      (node (ref "J157") (pin "3") (pinfunction "3_3") (pintype "bidirectional"))
      (node (ref "J158") (pin "2") (pinfunction "2_2") (pintype "bidirectional"))
    )
    (net (code "190") (name "Net-(J158-Pad3)") (class "Default")
      (node (ref "J158") (pin "3") (pinfunction "3_3") (pintype "bidirectional"))
      (node (ref "J159") (pin "2") (pinfunction "2_2") (pintype "bidirectional"))
    )
    (net (code "191") (name "Net-(J159-Pad3)") (class "Default")
      (node (ref "J159") (pin "3") (pinfunction "3_3") (pintype "bidirectional"))
      (node (ref "J160") (pin "2") (pinfunction "2_2") (pintype "bidirectional"))
    )
    (net (code "192") (name "Net-(J161-Pad3)") (class "Default")
      (node (ref "J161") (pin "3") (pinfunction "3_3") (pintype "bidirectional"))
      (node (ref "J162") (pin "2") (pinfunction "2_2") (pintype "bidirectional"))
    )
    (net (code "193") (name "Net-(J162-Pad3)") (class "Default")
      (node (ref "J162") (pin "3") (pinfunction "3_3") (pintype "bidirectional"))
      (node (ref "J163") (pin "2") (pinfunction "2_2") (pintype "bidirectional"))
    )
    (net (code "194") (name "Net-(J163-Pad3)") (class "Default")
      (node (ref "J163") (pin "3") (pinfunction "3_3") (pintype "bidirectional"))
      (node (ref "J164") (pin "2") (pinfunction "2_2") (pintype "bidirectional"))
    )
    (net (code "195") (name "Net-(J164-Pad3)") (class "Default")
      (node (ref "J164") (pin "3") (pinfunction "3_3") (pintype "bidirectional"))
      (node (ref "J165") (pin "2") (pinfunction "2_2") (pintype "bidirectional"))
    )
    (net (code "196") (name "Net-(J165-Pad3)") (class "Default")
      (node (ref "J165") (pin "3") (pinfunction "3_3") (pintype "bidirectional"))
      (node (ref "J166") (pin "2") (pinfunction "2_2") (pintype "bidirectional"))
    )
    (net (code "197") (name "Net-(J166-Pad3)") (class "Default")
      (node (ref "J166") (pin "3") (pinfunction "3_3") (pintype "bidirectional"))
      (node (ref "J167") (pin "2") (pinfunction "2_2") (pintype "bidirectional"))
    )
    (net (code "198") (name "Net-(J167-Pad3)") (class "Default")
      (node (ref "J167") (pin "3") (pinfunction "3_3") (pintype "bidirectional"))
      (node (ref "J168") (pin "2") (pinfunction "2_2") (pintype "bidirectional"))
    )
    (net (code "199") (name "Net-(J168-Pad3)") (class "Default")
      (node (ref "J168") (pin "3") (pinfunction "3_3") (pintype "bidirectional"))
      (node (ref "J169") (pin "2") (pinfunction "2_2") (pintype "bidirectional"))
    )
    (net (code "200") (name "Net-(J169-Pad3)") (class "Default")
      (node (ref "J169") (pin "3") (pinfunction "3_3") (pintype "bidirectional"))
      (node (ref "J170") (pin "2") (pinfunction "2_2") (pintype "bidirectional"))
    )
    (net (code "201") (name "Net-(J170-Pad3)") (class "Default")
      (node (ref "J170") (pin "3") (pinfunction "3_3") (pintype "bidirectional"))
      (node (ref "J171") (pin "2") (pinfunction "2_2") (pintype "bidirectional"))
    )
    (net (code "202") (name "Net-(J171-Pad3)") (class "Default")
      (node (ref "J171") (pin "3") (pinfunction "3_3") (pintype "bidirectional"))
      (node (ref "J172") (pin "2") (pinfunction "2_2") (pintype "bidirectional"))
    )
    (net (code "203") (name "Net-(J172-Pad3)") (class "Default")
      (node (ref "J172") (pin "3") (pinfunction "3_3") (pintype "bidirectional"))
      (node (ref "J173") (pin "2") (pinfunction "2_2") (pintype "bidirectional"))
    )
    (net (code "204") (name "Net-(J173-Pad3)") (class "Default")
      (node (ref "J173") (pin "3") (pinfunction "3_3") (pintype "bidirectional"))
      (node (ref "J174") (pin "2") (pinfunction "2_2") (pintype "bidirectional"))
    )
    (net (code "205") (name "Net-(J174-Pad3)") (class "Default")
      (node (ref "J174") (pin "3") (pinfunction "3_3") (pintype "bidirectional"))
      (node (ref "J175") (pin "2") (pinfunction "2_2") (pintype "bidirectional"))
    )
    (net (code "206") (name "Net-(J175-Pad3)") (class "Default")
      (node (ref "J175") (pin "3") (pinfunction "3_3") (pintype "bidirectional"))
      (node (ref "J176") (pin "2") (pinfunction "2_2") (pintype "bidirectional"))
    )
    (net (code "207") (name "Net-(J176-Pad3)") (class "Default")
      (node (ref "J176") (pin "3") (pinfunction "3_3") (pintype "bidirectional"))
      (node (ref "J177") (pin "2") (pinfunction "2_2") (pintype "bidirectional"))
    )
    (net (code "208") (name "Net-(J177-Pad3)") (class "Default")
      (node (ref "J177") (pin "3") (pinfunction "3_3") (pintype "bidirectional"))
      (node (ref "J178") (pin "2") (pinfunction "2_2") (pintype "bidirectional"))
    )
    (net (code "209") (name "Net-(J178-Pad3)") (class "Default")
      (node (ref "J178") (pin "3") (pinfunction "3_3") (pintype "bidirectional"))
      (node (ref "J179") (pin "2") (pinfunction "2_2") (pintype "bidirectional"))
    )
    (net (code "210") (name "Net-(J179-Pad3)") (class "Default")
      (node (ref "J179") (pin "3") (pinfunction "3_3") (pintype "bidirectional"))
      (node (ref "J180") (pin "2") (pinfunction "2_2") (pintype "bidirectional"))
    )
    (net (code "211") (name "Net-(J180-Pad3)") (class "Default")
      (node (ref "J180") (pin "3") (pinfunction "3_3") (pintype "bidirectional"))
      (node (ref "J181") (pin "2") (pinfunction "2_2") (pintype "bidirectional"))
    )
    (net (code "212") (name "Net-(J181-Pad3)") (class "Default")
      (node (ref "J181") (pin "3") (pinfunction "3_3") (pintype "bidirectional"))
      (node (ref "J182") (pin "2") (pinfunction "2_2") (pintype "bidirectional"))
    )
    (net (code "213") (name "Net-(J182-Pad3)") (class "Default")
      (node (ref "J182") (pin "3") (pinfunction "3_3") (pintype "bidirectional"))
      (node (ref "J183") (pin "2") (pinfunction "2_2") (pintype "bidirectional"))
    )
    (net (code "214") (name "Net-(J183-Pad3)") (class "Default")
      (node (ref "J183") (pin "3") (pinfunction "3_3") (pintype "bidirectional"))
      (node (ref "J184") (pin "2") (pinfunction "2_2") (pintype "bidirectional"))
    )
    (net (code "215") (name "Net-(J184-Pad3)") (class "Default")
      (node (ref "J184") (pin "3") (pinfunction "3_3") (pintype "bidirectional"))
      (node (ref "J185") (pin "2") (pinfunction "2_2") (pintype "bidirectional"))
    )
    (net (code "216") (name "Net-(J185-Pad3)") (class "Default")
      (node (ref "J185") (pin "3") (pinfunction "3_3") (pintype "bidirectional"))
      (node (ref "J186") (pin "2") (pinfunction "2_2") (pintype "bidirectional"))
    )
    (net (code "217") (name "Net-(J186-Pad3)") (class "Default")
      (node (ref "J186") (pin "3") (pinfunction "3_3") (pintype "bidirectional"))
      (node (ref "J187") (pin "2") (pinfunction "2_2") (pintype "bidirectional"))
    )
    (net (code "218") (name "Net-(J187-Pad3)") (class "Default")
      (node (ref "J187") (pin "3") (pinfunction "3_3") (pintype "bidirectional"))
      (node (ref "J188") (pin "2") (pinfunction "2_2") (pintype "bidirectional"))
    )
    (net (code "219") (name "Net-(J188-Pad3)") (class "Default")
      (node (ref "J188") (pin "3") (pinfunction "3_3") (pintype "bidirectional"))
      (node (ref "J189") (pin "2") (pinfunction "2_2") (pintype "bidirectional"))
    )
    (net (code "220") (name "Net-(J189-Pad3)") (class "Default")
      (node (ref "J189") (pin "3") (pinfunction "3_3") (pintype "bidirectional"))
      (node (ref "J190") (pin "2") (pinfunction "2_2") (pintype "bidirectional"))
    )
    (net (code "221") (name "Net-(J190-Pad3)") (class "Default")
      (node (ref "J190") (pin "3") (pinfunction "3_3") (pintype "bidirectional"))
      (node (ref "J191") (pin "2") (pinfunction "2_2") (pintype "bidirectional"))
    )
    (net (code "222") (name "Net-(J191-Pad3)") (class "Default")
      (node (ref "J191") (pin "3") (pinfunction "3_3") (pintype "bidirectional"))
      (node (ref "J192") (pin "2") (pinfunction "2_2") (pintype "bidirectional"))
    )
    (net (code "223") (name "Net-(J193-Pad3)") (class "Default")
      (node (ref "J193") (pin "3") (pinfunction "3_3") (pintype "bidirectional"))
      (node (ref "J194") (pin "2") (pinfunction "2_2") (pintype "bidirectional"))
    )
    (net (code "224") (name "Net-(J194-Pad3)") (class "Default")
      (node (ref "J194") (pin "3") (pinfunction "3_3") (pintype "bidirectional"))
      (node (ref "J195") (pin "2") (pinfunction "2_2") (pintype "bidirectional"))
    )
    (net (code "225") (name "Net-(J195-Pad3)") (class "Default")
      (node (ref "J195") (pin "3") (pinfunction "3_3") (pintype "bidirectional"))
      (node (ref "J196") (pin "2") (pinfunction "2_2") (pintype "bidirectional"))
    )
    (net (code "226") (name "Net-(J196-Pad3)") (class "Default")
      (node (ref "J196") (pin "3") (pinfunction "3_3") (pintype "bidirectional"))
      (node (ref "J197") (pin "2") (pinfunction "2_2") (pintype "bidirectional"))
    )
    (net (code "227") (name "Net-(J197-Pad3)") (class "Default")
      (node (ref "J197") (pin "3") (pinfunction "3_3") (pintype "bidirectional"))
      (node (ref "J198") (pin "2") (pinfunction "2_2") (pintype "bidirectional"))
    )
    (net (code "228") (name "Net-(J198-Pad3)") (class "Default")
      (node (ref "J198") (pin "3") (pinfunction "3_3") (pintype "bidirectional"))
      (node (ref "J199") (pin "2") (pinfunction "2_2") (pintype "bidirectional"))
    )
    (net (code "229") (name "Net-(J199-Pad3)") (class "Default")
      (node (ref "J199") (pin "3") (pinfunction "3_3") (pintype "bidirectional"))
      (node (ref "J200") (pin "2") (pinfunction "2_2") (pintype "bidirectional"))
    )
    (net (code "230") (name "Net-(J200-Pad3)") (class "Default")
      (node (ref "J200") (pin "3") (pinfunction "3_3") (pintype "bidirectional"))
      (node (ref "J201") (pin "2") (pinfunction "2_2") (pintype "bidirectional"))
    )
    (net (code "231") (name "Net-(J201-Pad3)") (class "Default")
      (node (ref "J201") (pin "3") (pinfunction "3_3") (pintype "bidirectional"))
      (node (ref "J202") (pin "2") (pinfunction "2_2") (pintype "bidirectional"))
    )
    (net (code "232") (name "Net-(J202-Pad3)") (class "Default")
      (node (ref "J202") (pin "3") (pinfunction "3_3") (pintype "bidirectional"))
      (node (ref "J203") (pin "2") (pinfunction "2_2") (pintype "bidirectional"))
    )
    (net (code "233") (name "Net-(J203-Pad3)") (class "Default")
      (node (ref "J203") (pin "3") (pinfunction "3_3") (pintype "bidirectional"))
      (node (ref "J204") (pin "2") (pinfunction "2_2") (pintype "bidirectional"))
    )
    (net (code "234") (name "Net-(J204-Pad3)") (class "Default")
      (node (ref "J204") (pin "3") (pinfunction "3_3") (pintype "bidirectional"))
      (node (ref "J205") (pin "2") (pinfunction "2_2") (pintype "bidirectional"))
    )
    (net (code "235") (name "Net-(J205-Pad3)") (class "Default")
      (node (ref "J205") (pin "3") (pinfunction "3_3") (pintype "bidirectional"))
      (node (ref "J206") (pin "2") (pinfunction "2_2") (pintype "bidirectional"))
    )
    (net (code "236") (name "Net-(J206-Pad3)") (class "Default")
      (node (ref "J206") (pin "3") (pinfunction "3_3") (pintype "bidirectional"))
      (node (ref "J207") (pin "2") (pinfunction "2_2") (pintype "bidirectional"))
    )
    (net (code "237") (name "Net-(J207-Pad3)") (class "Default")
      (node (ref "J207") (pin "3") (pinfunction "3_3") (pintype "bidirectional"))
      (node (ref "J208") (pin "2") (pinfunction "2_2") (pintype "bidirectional"))
    )
    (net (code "238") (name "Net-(J208-Pad3)") (class "Default")
      (node (ref "J208") (pin "3") (pinfunction "3_3") (pintype "bidirectional"))
      (node (ref "J209") (pin "2") (pinfunction "2_2") (pintype "bidirectional"))
    )
    (net (code "239") (name "Net-(J209-Pad3)") (class "Default")
      (node (ref "J209") (pin "3") (pinfunction "3_3") (pintype "bidirectional"))
      (node (ref "J210") (pin "2") (pinfunction "2_2") (pintype "bidirectional"))
    )
    (net (code "240") (name "Net-(J210-Pad3)") (class "Default")
      (node (ref "J210") (pin "3") (pinfunction "3_3") (pintype "bidirectional"))
      (node (ref "J211") (pin "2") (pinfunction "2_2") (pintype "bidirectional"))
    )
    (net (code "241") (name "Net-(J211-Pad3)") (class "Default")
      (node (ref "J211") (pin "3") (pinfunction "3_3") (pintype "bidirectional"))
      (node (ref "J212") (pin "2") (pinfunction "2_2") (pintype "bidirectional"))
    )
    (net (code "242") (name "Net-(J212-Pad3)") (class "Default")
      (node (ref "J212") (pin "3") (pinfunction "3_3") (pintype "bidirectional"))
      (node (ref "J213") (pin "2") (pinfunction "2_2") (pintype "bidirectional"))
    )
    (net (code "243") (name "Net-(J213-Pad3)") (class "Default")
      (node (ref "J213") (pin "3") (pinfunction "3_3") (pintype "bidirectional"))
      (node (ref "J214") (pin "2") (pinfunction "2_2") (pintype "bidirectional"))
    )
    (net (code "244") (name "Net-(J214-Pad3)") (class "Default")
      (node (ref "J214") (pin "3") (pinfunction "3_3") (pintype "bidirectional"))
      (node (ref "J215") (pin "2") (pinfunction "2_2") (pintype "bidirectional"))
    )
    (net (code "245") (name "Net-(J215-Pad3)") (class "Default")
      (node (ref "J215") (pin "3") (pinfunction "3_3") (pintype "bidirectional"))
      (node (ref "J216") (pin "2") (pinfunction "2_2") (pintype "bidirectional"))
    )
    (net (code "246") (name "Net-(J216-Pad3)") (class "Default")
      (node (ref "J216") (pin "3") (pinfunction "3_3") (pintype "bidirectional"))
      (node (ref "J217") (pin "2") (pinfunction "2_2") (pintype "bidirectional"))
    )
    (net (code "247") (name "Net-(J217-Pad3)") (class "Default")
      (node (ref "J217") (pin "3") (pinfunction "3_3") (pintype "bidirectional"))
      (node (ref "J218") (pin "2") (pinfunction "2_2") (pintype "bidirectional"))
    )
    (net (code "248") (name "Net-(J218-Pad3)") (class "Default")
      (node (ref "J218") (pin "3") (pinfunction "3_3") (pintype "bidirectional"))
      (node (ref "J219") (pin "2") (pinfunction "2_2") (pintype "bidirectional"))
    )
    (net (code "249") (name "Net-(J219-Pad3)") (class "Default")
      (node (ref "J219") (pin "3") (pinfunction "3_3") (pintype "bidirectional"))
      (node (ref "J220") (pin "2") (pinfunction "2_2") (pintype "bidirectional"))
    )
    (net (code "250") (name "Net-(J220-Pad3)") (class "Default")
      (node (ref "J220") (pin "3") (pinfunction "3_3") (pintype "bidirectional"))
      (node (ref "J221") (pin "2") (pinfunction "2_2") (pintype "bidirectional"))
    )
    (net (code "251") (name "Net-(J221-Pad3)") (class "Default")
      (node (ref "J221") (pin "3") (pinfunction "3_3") (pintype "bidirectional"))
      (node (ref "J222") (pin "2") (pinfunction "2_2") (pintype "bidirectional"))
    )
    (net (code "252") (name "Net-(J222-Pad3)") (class "Default")
      (node (ref "J222") (pin "3") (pinfunction "3_3") (pintype "bidirectional"))
      (node (ref "J223") (pin "2") (pinfunction "2_2") (pintype "bidirectional"))
    )
    (net (code "253") (name "Net-(J223-Pad3)") (class "Default")
      (node (ref "J223") (pin "3") (pinfunction "3_3") (pintype "bidirectional"))
      (node (ref "J224") (pin "2") (pinfunction "2_2") (pintype "bidirectional"))
    )
    (net (code "254") (name "Net-(J225-Pad3)") (class "Default")
      (node (ref "J225") (pin "3") (pinfunction "3_3") (pintype "bidirectional"))
      (node (ref "J226") (pin "2") (pinfunction "2_2") (pintype "bidirectional"))
    )
    (net (code "255") (name "Net-(J226-Pad3)") (class "Default")
      (node (ref "J226") (pin "3") (pinfunction "3_3") (pintype "bidirectional"))
      (node (ref "J227") (pin "2") (pinfunction "2_2") (pintype "bidirectional"))
    )
    (net (code "256") (name "Net-(J227-Pad3)") (class "Default")
      (node (ref "J227") (pin "3") (pinfunction "3_3") (pintype "bidirectional"))
      (node (ref "J228") (pin "2") (pinfunction "2_2") (pintype "bidirectional"))
    )
    (net (code "257") (name "Net-(J228-Pad3)") (class "Default")
      (node (ref "J228") (pin "3") (pinfunction "3_3") (pintype "bidirectional"))
      (node (ref "J229") (pin "2") (pinfunction "2_2") (pintype "bidirectional"))
    )
    (net (code "258") (name "Net-(J229-Pad3)") (class "Default")
      (node (ref "J229") (pin "3") (pinfunction "3_3") (pintype "bidirectional"))
      (node (ref "J230") (pin "2") (pinfunction "2_2") (pintype "bidirectional"))
    )
    (net (code "259") (name "Net-(J230-Pad3)") (class "Default")
      (node (ref "J230") (pin "3") (pinfunction "3_3") (pintype "bidirectional"))
      (node (ref "J231") (pin "2") (pinfunction "2_2") (pintype "bidirectional"))
    )
    (net (code "260") (name "Net-(J231-Pad3)") (class "Default")
      (node (ref "J231") (pin "3") (pinfunction "3_3") (pintype "bidirectional"))
      (node (ref "J232") (pin "2") (pinfunction "2_2") (pintype "bidirectional"))
    )
    (net (code "261") (name "Net-(J232-Pad3)") (class "Default")
      (node (ref "J232") (pin "3") (pinfunction "3_3") (pintype "bidirectional"))
      (node (ref "J233") (pin "2") (pinfunction "2_2") (pintype "bidirectional"))
    )
    (net (code "262") (name "Net-(J233-Pad3)") (class "Default")
      (node (ref "J233") (pin "3") (pinfunction "3_3") (pintype "bidirectional"))
      (node (ref "J234") (pin "2") (pinfunction "2_2") (pintype "bidirectional"))
    )
    (net (code "263") (name "Net-(J234-Pad3)") (class "Default")
      (node (ref "J234") (pin "3") (pinfunction "3_3") (pintype "bidirectional"))
      (node (ref "J235") (pin "2") (pinfunction "2_2") (pintype "bidirectional"))
    )
    (net (code "264") (name "Net-(J235-Pad3)") (class "Default")
      (node (ref "J235") (pin "3") (pinfunction "3_3") (pintype "bidirectional"))
      (node (ref "J236") (pin "2") (pinfunction "2_2") (pintype "bidirectional"))
    )
    (net (code "265") (name "Net-(J236-Pad3)") (class "Default")
      (node (ref "J236") (pin "3") (pinfunction "3_3") (pintype "bidirectional"))
      (node (ref "J237") (pin "2") (pinfunction "2_2") (pintype "bidirectional"))
    )
    (net (code "266") (name "Net-(J237-Pad3)") (class "Default")
      (node (ref "J237") (pin "3") (pinfunction "3_3") (pintype "bidirectional"))
      (node (ref "J238") (pin "2") (pinfunction "2_2") (pintype "bidirectional"))
    )
    (net (code "267") (name "Net-(J238-Pad3)") (class "Default")
      (node (ref "J238") (pin "3") (pinfunction "3_3") (pintype "bidirectional"))
      (node (ref "J239") (pin "2") (pinfunction "2_2") (pintype "bidirectional"))
    )
    (net (code "268") (name "Net-(J239-Pad3)") (class "Default")
      (node (ref "J239") (pin "3") (pinfunction "3_3") (pintype "bidirectional"))
      (node (ref "J240") (pin "2") (pinfunction "2_2") (pintype "bidirectional"))
    )
    (net (code "269") (name "Net-(J240-Pad3)") (class "Default")
      (node (ref "J240") (pin "3") (pinfunction "3_3") (pintype "bidirectional"))
      (node (ref "J241") (pin "2") (pinfunction "2_2") (pintype "bidirectional"))
    )
    (net (code "270") (name "Net-(J241-Pad3)") (class "Default")
      (node (ref "J241") (pin "3") (pinfunction "3_3") (pintype "bidirectional"))
      (node (ref "J242") (pin "2") (pinfunction "2_2") (pintype "bidirectional"))
    )
    (net (code "271") (name "Net-(J242-Pad3)") (class "Default")
      (node (ref "J242") (pin "3") (pinfunction "3_3") (pintype "bidirectional"))
      (node (ref "J243") (pin "2") (pinfunction "2_2") (pintype "bidirectional"))
    )
    (net (code "272") (name "Net-(J243-Pad3)") (class "Default")
      (node (ref "J243") (pin "3") (pinfunction "3_3") (pintype "bidirectional"))
      (node (ref "J244") (pin "2") (pinfunction "2_2") (pintype "bidirectional"))
    )
    (net (code "273") (name "Net-(J244-Pad3)") (class "Default")
      (node (ref "J244") (pin "3") (pinfunction "3_3") (pintype "bidirectional"))
      (node (ref "J245") (pin "2") (pinfunction "2_2") (pintype "bidirectional"))
    )
    (net (code "274") (name "Net-(J245-Pad3)") (class "Default")
      (node (ref "J245") (pin "3") (pinfunction "3_3") (pintype "bidirectional"))
      (node (ref "J246") (pin "2") (pinfunction "2_2") (pintype "bidirectional"))
    )
    (net (code "275") (name "Net-(J246-Pad3)") (class "Default")
      (node (ref "J246") (pin "3") (pinfunction "3_3") (pintype "bidirectional"))
      (node (ref "J247") (pin "2") (pinfunction "2_2") (pintype "bidirectional"))
    )
    (net (code "276") (name "Net-(J247-Pad3)") (class "Default")
      (node (ref "J247") (pin "3") (pinfunction "3_3") (pintype "bidirectional"))
      (node (ref "J248") (pin "2") (pinfunction "2_2") (pintype "bidirectional"))
    )
    (net (code "277") (name "Net-(J248-Pad3)") (class "Default")
      (node (ref "J248") (pin "3") (pinfunction "3_3") (pintype "bidirectional"))
      (node (ref "J249") (pin "2") (pinfunction "2_2") (pintype "bidirectional"))
    )
    (net (code "278") (name "Net-(J249-Pad3)") (class "Default")
      (node (ref "J249") (pin "3") (pinfunction "3_3") (pintype "bidirectional"))
      (node (ref "J250") (pin "2") (pinfunction "2_2") (pintype "bidirectional"))
    )
    (net (code "279") (name "Net-(J250-Pad3)") (class "Default")
      (node (ref "J250") (pin "3") (pinfunction "3_3") (pintype "bidirectional"))
      (node (ref "J251") (pin "2") (pinfunction "2_2") (pintype "bidirectional"))
    )
    (net (code "280") (name "Net-(J251-Pad3)") (class "Default")
      (node (ref "J251") (pin "3") (pinfunction "3_3") (pintype "bidirectional"))
      (node (ref "J252") (pin "2") (pinfunction "2_2") (pintype "bidirectional"))
    )
    (net (code "281") (name "Net-(J252-Pad3)") (class "Default")
      (node (ref "J252") (pin "3") (pinfunction "3_3") (pintype "bidirectional"))
      (node (ref "J253") (pin "2") (pinfunction "2_2") (pintype "bidirectional"))
    )
    (net (code "282") (name "Net-(J253-Pad3)") (class "Default")
      (node (ref "J253") (pin "3") (pinfunction "3_3") (pintype "bidirectional"))
      (node (ref "J254") (pin "2") (pinfunction "2_2") (pintype "bidirectional"))
    )
    (net (code "283") (name "Net-(J254-Pad3)") (class "Default")
      (node (ref "J254") (pin "3") (pinfunction "3_3") (pintype "bidirectional"))
      (node (ref "J255") (pin "2") (pinfunction "2_2") (pintype "bidirectional"))
    )
    (net (code "284") (name "Net-(J255-Pad3)") (class "Default")
      (node (ref "J255") (pin "3") (pinfunction "3_3") (pintype "bidirectional"))
      (node (ref "J256") (pin "2") (pinfunction "2_2") (pintype "bidirectional"))
    )
    (net (code "285") (name "Net-(Q1-B)") (class "Default")
      (node (ref "Q1") (pin "1") (pinfunction "B_1") (pintype "passive"))
      (node (ref "Q3") (pin "2") (pinfunction "S_2") (pintype "passive"))
      (node (ref "R1") (pin "1") (pinfunction "1_1") (pintype "bidirectional"))
      (node (ref "R7") (pin "2") (pinfunction "2_2") (pintype "bidirectional"))
    )
    (net (code "286") (name "Net-(Q1-C)") (class "Default")
      (node (ref "Q1") (pin "3") (pinfunction "C_3") (pintype "passive"))
      (node (ref "Q3") (pin "1") (pinfunction "G_1") (pintype "passive"))
      (node (ref "R1") (pin "2") (pinfunction "2_2") (pintype "bidirectional"))
      (node (ref "R2") (pin "1") (pinfunction "1_1") (pintype "bidirectional"))
    )
    (net (code "287") (name "Net-(Q2-G)") (class "Default")
      (node (ref "Q2") (pin "1") (pinfunction "G_1") (pintype "passive"))
      (node (ref "Q4") (pin "3") (pinfunction "C_3") (pintype "passive"))
      (node (ref "R4") (pin "2") (pinfunction "2_2") (pintype "bidirectional"))
      (node (ref "R5") (pin "1") (pinfunction "1_1") (pintype "bidirectional"))
    )
    (net (code "288") (name "Net-(Q2-S)") (class "Default")
      (node (ref "Q2") (pin "2") (pinfunction "S_2") (pintype "passive"))
      (node (ref "Q4") (pin "1") (pinfunction "B_1") (pintype "passive"))
      (node (ref "R3") (pin "2") (pinfunction "2_2") (pintype "bidirectional"))
      (node (ref "R4") (pin "1") (pinfunction "1_1") (pintype "bidirectional"))
    )
    (net (code "289") (name "Net-(Q5-B)") (class "Default")
      (node (ref "Q5") (pin "1") (pinfunction "B_1") (pintype "passive"))
      (node (ref "Q6") (pin "2") (pinfunction "S_2") (pintype "passive"))
      (node (ref "R14") (pin "2") (pinfunction "2_2") (pintype "bidirectional"))
      (node (ref "R8") (pin "1") (pinfunction "1_1") (pintype "bidirectional"))
    )
    (net (code "290") (name "Net-(Q5-C)") (class "Default")
      (node (ref "Q5") (pin "3") (pinfunction "C_3") (pintype "passive"))
      (node (ref "Q6") (pin "1") (pinfunction "G_1") (pintype "passive"))
      (node (ref "R10") (pin "1") (pinfunction "1_1") (pintype "bidirectional"))
      (node (ref "R8") (pin "2") (pinfunction "2_2") (pintype "bidirectional"))
    )
    (net (code "291") (name "Net-(Q7-B)") (class "Default")
      (node (ref "Q7") (pin "1") (pinfunction "B_1") (pintype "passive"))
      (node (ref "Q8") (pin "2") (pinfunction "S_2") (pintype "passive"))
      (node (ref "R15") (pin "1") (pinfunction "1_1") (pintype "bidirectional"))
      (node (ref "R27") (pin "2") (pinfunction "2_2") (pintype "bidirectional"))
    )
    (net (code "292") (name "Net-(Q7-C)") (class "Default")
      (node (ref "Q7") (pin "3") (pinfunction "C_3") (pintype "passive"))
      (node (ref "Q8") (pin "1") (pinfunction "G_1") (pintype "passive"))
      (node (ref "R15") (pin "2") (pinfunction "2_2") (pintype "bidirectional"))
      (node (ref "R17") (pin "1") (pinfunction "1_1") (pintype "bidirectional"))
    )
    (net (code "293") (name "Net-(U3A-IN+)") (class "Default")
      (node (ref "C20") (pin "2") (pinfunction "2_2") (pintype "bidirectional"))
      (node (ref "R18") (pin "1") (pinfunction "1_1") (pintype "bidirectional"))
      (node (ref "R19") (pin "2") (pinfunction "2_2") (pintype "bidirectional"))
      (node (ref "U3") (pin "3") (pinfunction "IN+_3") (pintype "input"))
    )
    (net (code "294") (name "Net-(U3B-IN-)") (class "Default")
      (node (ref "C9") (pin "2") (pinfunction "2_2") (pintype "bidirectional"))
      (node (ref "R20") (pin "1") (pinfunction "1_1") (pintype "bidirectional"))
      (node (ref "U3") (pin "9") (pinfunction "IN-_9") (pintype "input"))
    )
    (net (code "295") (name "Net-(U3B-OUT)") (class "Default")
      (node (ref "C16") (pin "1") (pinfunction "1_1") (pintype "bidirectional"))
      (node (ref "R20") (pin "2") (pinfunction "2_2") (pintype "bidirectional"))
      (node (ref "U3") (pin "8") (pinfunction "OUT_8") (pintype "output"))
    )
    (net (code "296") (name "Net-(U3C-IN-)") (class "Default")
      (node (ref "R21") (pin "2") (pinfunction "2_2") (pintype "bidirectional"))
      (node (ref "R22") (pin "1") (pinfunction "1_1") (pintype "bidirectional"))
      (node (ref "U3") (pin "6") (pinfunction "IN-_6") (pintype "input"))
    )
    (net (code "297") (name "Net-(U3C-OUT)") (class "Default")
      (node (ref "R22") (pin "2") (pinfunction "2_2") (pintype "bidirectional"))
      (node (ref "R25") (pin "1") (pinfunction "1_1") (pintype "bidirectional"))
      (node (ref "U3") (pin "7") (pinfunction "OUT_7") (pintype "output"))
    )
    (net (code "298") (name "Net-(U3D-IN-)") (class "Default")
      (node (ref "C18") (pin "2") (pinfunction "2_2") (pintype "bidirectional"))
      (node (ref "R23") (pin "1") (pinfunction "1_1") (pintype "bidirectional"))
      (node (ref "R24") (pin "1") (pinfunction "1_1") (pintype "bidirectional"))
      (node (ref "R26") (pin "2") (pinfunction "2_2") (pintype "bidirectional"))
      (node (ref "U3") (pin "13") (pinfunction "IN-_13") (pintype "input"))
    )
    (net (code "299") (name "Net-(U3D-OUT)") (class "Default")
      (node (ref "C10") (pin "1") (pinfunction "1_1") (pintype "bidirectional"))
      (node (ref "R23") (pin "2") (pinfunction "2_2") (pintype "bidirectional"))
      (node (ref "U3") (pin "14") (pinfunction "OUT_14") (pintype "output"))
    )
    (net (code "300") (name "REF") (class "Default")
      (node (ref "R24") (pin "2") (pinfunction "2_2") (pintype "bidirectional"))
      (node (ref "U3") (pin "1") (pinfunction "OUT_1") (pintype "output"))
      (node (ref "U3") (pin "10") (pinfunction "IN+_10") (pintype "input"))
      (node (ref "U3") (pin "12") (pinfunction "IN+_12") (pintype "input"))
      (node (ref "U3") (pin "2") (pinfunction "IN-_2") (pintype "input"))
      (node (ref "U3") (pin "5") (pinfunction "IN+_5") (pintype "input"))
    )
    (net (code "301") (name "SOUND") (class "Default")
      (node (ref "C10") (pin "2") (pinfunction "2_2") (pintype "bidirectional"))
      (node (ref "JP1") (pin "5") (pinfunction "5_5") (pintype "passive"))
      (node (ref "JP3") (pin "5") (pinfunction "5_5") (pintype "passive"))
      (node (ref "R11") (pin "1") (pinfunction "1_1") (pintype "bidirectional"))
      (node (ref "R12") (pin "2") (pinfunction "2_2") (pintype "bidirectional"))
    )
    (net (code "302") (name "STREAMING") (class "Default")
      (node (ref "JP2") (pin "6") (pinfunction "6_6") (pintype "passive"))
      (node (ref "JP4") (pin "6") (pinfunction "6_6") (pintype "passive"))
      (node (ref "ONLINE/OFFLINE") (pin "2") (pinfunction "P_2") (pintype "passive"))
      (node (ref "R6") (pin "2") (pinfunction "2_2") (pintype "bidirectional"))
    )
    (net (code "303") (name "V+") (class "Default")
      (node (ref "C1") (pin "+") (pinfunction "1_+") (pintype "bidirectional"))
      (node (ref "C2") (pin "+") (pinfunction "1_+") (pintype "bidirectional"))
      (node (ref "C3") (pin "+") (pinfunction "1_+") (pintype "bidirectional"))
      (node (ref "C4") (pin "+") (pinfunction "1_+") (pintype "bidirectional"))
      (node (ref "C5") (pin "2") (pinfunction "2_2") (pintype "bidirectional"))
      (node (ref "C6") (pin "2") (pinfunction "2_2") (pintype "bidirectional"))
      (node (ref "C7") (pin "2") (pinfunction "2_2") (pintype "bidirectional"))
      (node (ref "C8") (pin "2") (pinfunction "2_2") (pintype "bidirectional"))
      (node (ref "J1") (pin "1") (pinfunction "1_1") (pintype "bidirectional"))
      (node (ref "J10") (pin "1") (pinfunction "1_1") (pintype "bidirectional"))
      (node (ref "J100") (pin "1") (pinfunction "1_1") (pintype "bidirectional"))
      (node (ref "J101") (pin "1") (pinfunction "1_1") (pintype "bidirectional"))
      (node (ref "J102") (pin "1") (pinfunction "1_1") (pintype "bidirectional"))
      (node (ref "J103") (pin "1") (pinfunction "1_1") (pintype "bidirectional"))
      (node (ref "J104") (pin "1") (pinfunction "1_1") (pintype "bidirectional"))
      (node (ref "J105") (pin "1") (pinfunction "1_1") (pintype "bidirectional"))
      (node (ref "J106") (pin "1") (pinfunction "1_1") (pintype "bidirectional"))
      (node (ref "J107") (pin "1") (pinfunction "1_1") (pintype "bidirectional"))
      (node (ref "J108") (pin "1") (pinfunction "1_1") (pintype "bidirectional"))
      (node (ref "J109") (pin "1") (pinfunction "1_1") (pintype "bidirectional"))
      (node (ref "J11") (pin "1") (pinfunction "1_1") (pintype "bidirectional"))
      (node (ref "J110") (pin "1") (pinfunction "1_1") (pintype "bidirectional"))
      (node (ref "J111") (pin "1") (pinfunction "1_1") (pintype "bidirectional"))
      (node (ref "J112") (pin "1") (pinfunction "1_1") (pintype "bidirectional"))
      (node (ref "J113") (pin "1") (pinfunction "1_1") (pintype "bidirectional"))
      (node (ref "J114") (pin "1") (pinfunction "1_1") (pintype "bidirectional"))
      (node (ref "J115") (pin "1") (pinfunction "1_1") (pintype "bidirectional"))
      (node (ref "J116") (pin "1") (pinfunction "1_1") (pintype "bidirectional"))
      (node (ref "J117") (pin "1") (pinfunction "1_1") (pintype "bidirectional"))
      (node (ref "J118") (pin "1") (pinfunction "1_1") (pintype "bidirectional"))
      (node (ref "J119") (pin "1") (pinfunction "1_1") (pintype "bidirectional"))
      (node (ref "J12") (pin "1") (pinfunction "1_1") (pintype "bidirectional"))
      (node (ref "J120") (pin "1") (pinfunction "1_1") (pintype "bidirectional"))
      (node (ref "J121") (pin "1") (pinfunction "1_1") (pintype "bidirectional"))
      (node (ref "J122") (pin "1") (pinfunction "1_1") (pintype "bidirectional"))
      (node (ref "J123") (pin "1") (pinfunction "1_1") (pintype "bidirectional"))
      (node (ref "J124") (pin "1") (pinfunction "1_1") (pintype "bidirectional"))
      (node (ref "J125") (pin "1") (pinfunction "1_1") (pintype "bidirectional"))
      (node (ref "J126") (pin "1") (pinfunction "1_1") (pintype "bidirectional"))
      (node (ref "J127") (pin "1") (pinfunction "1_1") (pintype "bidirectional"))
      (node (ref "J128") (pin "1") (pinfunction "1_1") (pintype "bidirectional"))
      (node (ref "J129") (pin "1") (pinfunction "1_1") (pintype "bidirectional"))
      (node (ref "J13") (pin "1") (pinfunction "1_1") (pintype "bidirectional"))
      (node (ref "J130") (pin "1") (pinfunction "1_1") (pintype "bidirectional"))
      (node (ref "J131") (pin "1") (pinfunction "1_1") (pintype "bidirectional"))
      (node (ref "J132") (pin "1") (pinfunction "1_1") (pintype "bidirectional"))
      (node (ref "J133") (pin "1") (pinfunction "1_1") (pintype "bidirectional"))
      (node (ref "J134") (pin "1") (pinfunction "1_1") (pintype "bidirectional"))
      (node (ref "J135") (pin "1") (pinfunction "1_1") (pintype "bidirectional"))
      (node (ref "J136") (pin "1") (pinfunction "1_1") (pintype "bidirectional"))
      (node (ref "J137") (pin "1") (pinfunction "1_1") (pintype "bidirectional"))
      (node (ref "J138") (pin "1") (pinfunction "1_1") (pintype "bidirectional"))
      (node (ref "J139") (pin "1") (pinfunction "1_1") (pintype "bidirectional"))
      (node (ref "J14") (pin "1") (pinfunction "1_1") (pintype "bidirectional"))
      (node (ref "J140") (pin "1") (pinfunction "1_1") (pintype "bidirectional"))
      (node (ref "J141") (pin "1") (pinfunction "1_1") (pintype "bidirectional"))
      (node (ref "J142") (pin "1") (pinfunction "1_1") (pintype "bidirectional"))
      (node (ref "J143") (pin "1") (pinfunction "1_1") (pintype "bidirectional"))
      (node (ref "J144") (pin "1") (pinfunction "1_1") (pintype "bidirectional"))
      (node (ref "J145") (pin "1") (pinfunction "1_1") (pintype "bidirectional"))
      (node (ref "J146") (pin "1") (pinfunction "1_1") (pintype "bidirectional"))
      (node (ref "J147") (pin "1") (pinfunction "1_1") (pintype "bidirectional"))
      (node (ref "J148") (pin "1") (pinfunction "1_1") (pintype "bidirectional"))
      (node (ref "J149") (pin "1") (pinfunction "1_1") (pintype "bidirectional"))
      (node (ref "J15") (pin "1") (pinfunction "1_1") (pintype "bidirectional"))
      (node (ref "J150") (pin "1") (pinfunction "1_1") (pintype "bidirectional"))
      (node (ref "J151") (pin "1") (pinfunction "1_1") (pintype "bidirectional"))
      (node (ref "J152") (pin "1") (pinfunction "1_1") (pintype "bidirectional"))
      (node (ref "J153") (pin "1") (pinfunction "1_1") (pintype "bidirectional"))
      (node (ref "J154") (pin "1") (pinfunction "1_1") (pintype "bidirectional"))
      (node (ref "J155") (pin "1") (pinfunction "1_1") (pintype "bidirectional"))
      (node (ref "J156") (pin "1") (pinfunction "1_1") (pintype "bidirectional"))
      (node (ref "J157") (pin "1") (pinfunction "1_1") (pintype "bidirectional"))
      (node (ref "J158") (pin "1") (pinfunction "1_1") (pintype "bidirectional"))
      (node (ref "J159") (pin "1") (pinfunction "1_1") (pintype "bidirectional"))
      (node (ref "J16") (pin "1") (pinfunction "1_1") (pintype "bidirectional"))
      (node (ref "J160") (pin "1") (pinfunction "1_1") (pintype "bidirectional"))
      (node (ref "J161") (pin "1") (pinfunction "1_1") (pintype "bidirectional"))
      (node (ref "J162") (pin "1") (pinfunction "1_1") (pintype "bidirectional"))
      (node (ref "J163") (pin "1") (pinfunction "1_1") (pintype "bidirectional"))
      (node (ref "J164") (pin "1") (pinfunction "1_1") (pintype "bidirectional"))
      (node (ref "J165") (pin "1") (pinfunction "1_1") (pintype "bidirectional"))
      (node (ref "J166") (pin "1") (pinfunction "1_1") (pintype "bidirectional"))
      (node (ref "J167") (pin "1") (pinfunction "1_1") (pintype "bidirectional"))
      (node (ref "J168") (pin "1") (pinfunction "1_1") (pintype "bidirectional"))
      (node (ref "J169") (pin "1") (pinfunction "1_1") (pintype "bidirectional"))
      (node (ref "J17") (pin "1") (pinfunction "1_1") (pintype "bidirectional"))
      (node (ref "J170") (pin "1") (pinfunction "1_1") (pintype "bidirectional"))
      (node (ref "J171") (pin "1") (pinfunction "1_1") (pintype "bidirectional"))
      (node (ref "J172") (pin "1") (pinfunction "1_1") (pintype "bidirectional"))
      (node (ref "J173") (pin "1") (pinfunction "1_1") (pintype "bidirectional"))
      (node (ref "J174") (pin "1") (pinfunction "1_1") (pintype "bidirectional"))
      (node (ref "J175") (pin "1") (pinfunction "1_1") (pintype "bidirectional"))
      (node (ref "J176") (pin "1") (pinfunction "1_1") (pintype "bidirectional"))
      (node (ref "J177") (pin "1") (pinfunction "1_1") (pintype "bidirectional"))
      (node (ref "J178") (pin "1") (pinfunction "1_1") (pintype "bidirectional"))
      (node (ref "J179") (pin "1") (pinfunction "1_1") (pintype "bidirectional"))
      (node (ref "J18") (pin "1") (pinfunction "1_1") (pintype "bidirectional"))
      (node (ref "J180") (pin "1") (pinfunction "1_1") (pintype "bidirectional"))
      (node (ref "J181") (pin "1") (pinfunction "1_1") (pintype "bidirectional"))
      (node (ref "J182") (pin "1") (pinfunction "1_1") (pintype "bidirectional"))
      (node (ref "J183") (pin "1") (pinfunction "1_1") (pintype "bidirectional"))
      (node (ref "J184") (pin "1") (pinfunction "1_1") (pintype "bidirectional"))
      (node (ref "J185") (pin "1") (pinfunction "1_1") (pintype "bidirectional"))
      (node (ref "J186") (pin "1") (pinfunction "1_1") (pintype "bidirectional"))
      (node (ref "J187") (pin "1") (pinfunction "1_1") (pintype "bidirectional"))
      (node (ref "J188") (pin "1") (pinfunction "1_1") (pintype "bidirectional"))
      (node (ref "J189") (pin "1") (pinfunction "1_1") (pintype "bidirectional"))
      (node (ref "J19") (pin "1") (pinfunction "1_1") (pintype "bidirectional"))
      (node (ref "J190") (pin "1") (pinfunction "1_1") (pintype "bidirectional"))
      (node (ref "J191") (pin "1") (pinfunction "1_1") (pintype "bidirectional"))
      (node (ref "J192") (pin "1") (pinfunction "1_1") (pintype "bidirectional"))
      (node (ref "J193") (pin "1") (pinfunction "1_1") (pintype "bidirectional"))
      (node (ref "J194") (pin "1") (pinfunction "1_1") (pintype "bidirectional"))
      (node (ref "J195") (pin "1") (pinfunction "1_1") (pintype "bidirectional"))
      (node (ref "J196") (pin "1") (pinfunction "1_1") (pintype "bidirectional"))
      (node (ref "J197") (pin "1") (pinfunction "1_1") (pintype "bidirectional"))
      (node (ref "J198") (pin "1") (pinfunction "1_1") (pintype "bidirectional"))
      (node (ref "J199") (pin "1") (pinfunction "1_1") (pintype "bidirectional"))
      (node (ref "J2") (pin "1") (pinfunction "1_1") (pintype "bidirectional"))
      (node (ref "J20") (pin "1") (pinfunction "1_1") (pintype "bidirectional"))
      (node (ref "J200") (pin "1") (pinfunction "1_1") (pintype "bidirectional"))
      (node (ref "J201") (pin "1") (pinfunction "1_1") (pintype "bidirectional"))
      (node (ref "J202") (pin "1") (pinfunction "1_1") (pintype "bidirectional"))
      (node (ref "J203") (pin "1") (pinfunction "1_1") (pintype "bidirectional"))
      (node (ref "J204") (pin "1") (pinfunction "1_1") (pintype "bidirectional"))
      (node (ref "J205") (pin "1") (pinfunction "1_1") (pintype "bidirectional"))
      (node (ref "J206") (pin "1") (pinfunction "1_1") (pintype "bidirectional"))
      (node (ref "J207") (pin "1") (pinfunction "1_1") (pintype "bidirectional"))
      (node (ref "J208") (pin "1") (pinfunction "1_1") (pintype "bidirectional"))
      (node (ref "J209") (pin "1") (pinfunction "1_1") (pintype "bidirectional"))
      (node (ref "J21") (pin "1") (pinfunction "1_1") (pintype "bidirectional"))
      (node (ref "J210") (pin "1") (pinfunction "1_1") (pintype "bidirectional"))
      (node (ref "J211") (pin "1") (pinfunction "1_1") (pintype "bidirectional"))
      (node (ref "J212") (pin "1") (pinfunction "1_1") (pintype "bidirectional"))
      (node (ref "J213") (pin "1") (pinfunction "1_1") (pintype "bidirectional"))
      (node (ref "J214") (pin "1") (pinfunction "1_1") (pintype "bidirectional"))
      (node (ref "J215") (pin "1") (pinfunction "1_1") (pintype "bidirectional"))
      (node (ref "J216") (pin "1") (pinfunction "1_1") (pintype "bidirectional"))
      (node (ref "J217") (pin "1") (pinfunction "1_1") (pintype "bidirectional"))
      (node (ref "J218") (pin "1") (pinfunction "1_1") (pintype "bidirectional"))
      (node (ref "J219") (pin "1") (pinfunction "1_1") (pintype "bidirectional"))
      (node (ref "J22") (pin "1") (pinfunction "1_1") (pintype "bidirectional"))
      (node (ref "J220") (pin "1") (pinfunction "1_1") (pintype "bidirectional"))
      (node (ref "J221") (pin "1") (pinfunction "1_1") (pintype "bidirectional"))
      (node (ref "J222") (pin "1") (pinfunction "1_1") (pintype "bidirectional"))
      (node (ref "J223") (pin "1") (pinfunction "1_1") (pintype "bidirectional"))
      (node (ref "J224") (pin "1") (pinfunction "1_1") (pintype "bidirectional"))
      (node (ref "J225") (pin "1") (pinfunction "1_1") (pintype "bidirectional"))
      (node (ref "J226") (pin "1") (pinfunction "1_1") (pintype "bidirectional"))
      (node (ref "J227") (pin "1") (pinfunction "1_1") (pintype "bidirectional"))
      (node (ref "J228") (pin "1") (pinfunction "1_1") (pintype "bidirectional"))
      (node (ref "J229") (pin "1") (pinfunction "1_1") (pintype "bidirectional"))
      (node (ref "J23") (pin "1") (pinfunction "1_1") (pintype "bidirectional"))
      (node (ref "J230") (pin "1") (pinfunction "1_1") (pintype "bidirectional"))
      (node (ref "J231") (pin "1") (pinfunction "1_1") (pintype "bidirectional"))
      (node (ref "J232") (pin "1") (pinfunction "1_1") (pintype "bidirectional"))
      (node (ref "J233") (pin "1") (pinfunction "1_1") (pintype "bidirectional"))
      (node (ref "J234") (pin "1") (pinfunction "1_1") (pintype "bidirectional"))
      (node (ref "J235") (pin "1") (pinfunction "1_1") (pintype "bidirectional"))
      (node (ref "J236") (pin "1") (pinfunction "1_1") (pintype "bidirectional"))
      (node (ref "J237") (pin "1") (pinfunction "1_1") (pintype "bidirectional"))
      (node (ref "J238") (pin "1") (pinfunction "1_1") (pintype "bidirectional"))
      (node (ref "J239") (pin "1") (pinfunction "1_1") (pintype "bidirectional"))
      (node (ref "J24") (pin "1") (pinfunction "1_1") (pintype "bidirectional"))
      (node (ref "J240") (pin "1") (pinfunction "1_1") (pintype "bidirectional"))
      (node (ref "J241") (pin "1") (pinfunction "1_1") (pintype "bidirectional"))
      (node (ref "J242") (pin "1") (pinfunction "1_1") (pintype "bidirectional"))
      (node (ref "J243") (pin "1") (pinfunction "1_1") (pintype "bidirectional"))
      (node (ref "J244") (pin "1") (pinfunction "1_1") (pintype "bidirectional"))
      (node (ref "J245") (pin "1") (pinfunction "1_1") (pintype "bidirectional"))
      (node (ref "J246") (pin "1") (pinfunction "1_1") (pintype "bidirectional"))
      (node (ref "J247") (pin "1") (pinfunction "1_1") (pintype "bidirectional"))
      (node (ref "J248") (pin "1") (pinfunction "1_1") (pintype "bidirectional"))
      (node (ref "J249") (pin "1") (pinfunction "1_1") (pintype "bidirectional"))
      (node (ref "J25") (pin "1") (pinfunction "1_1") (pintype "bidirectional"))
      (node (ref "J250") (pin "1") (pinfunction "1_1") (pintype "bidirectional"))
      (node (ref "J251") (pin "1") (pinfunction "1_1") (pintype "bidirectional"))
      (node (ref "J252") (pin "1") (pinfunction "1_1") (pintype "bidirectional"))
      (node (ref "J253") (pin "1") (pinfunction "1_1") (pintype "bidirectional"))
      (node (ref "J254") (pin "1") (pinfunction "1_1") (pintype "bidirectional"))
      (node (ref "J255") (pin "1") (pinfunction "1_1") (pintype "bidirectional"))
      (node (ref "J256") (pin "1") (pinfunction "1_1") (pintype "bidirectional"))
      (node (ref "J26") (pin "1") (pinfunction "1_1") (pintype "bidirectional"))
      (node (ref "J27") (pin "1") (pinfunction "1_1") (pintype "bidirectional"))
      (node (ref "J28") (pin "1") (pinfunction "1_1") (pintype "bidirectional"))
      (node (ref "J29") (pin "1") (pinfunction "1_1") (pintype "bidirectional"))
      (node (ref "J3") (pin "1") (pinfunction "1_1") (pintype "bidirectional"))
      (node (ref "J30") (pin "1") (pinfunction "1_1") (pintype "bidirectional"))
      (node (ref "J31") (pin "1") (pinfunction "1_1") (pintype "bidirectional"))
      (node (ref "J32") (pin "1") (pinfunction "1_1") (pintype "bidirectional"))
      (node (ref "J33") (pin "1") (pinfunction "1_1") (pintype "bidirectional"))
      (node (ref "J34") (pin "1") (pinfunction "1_1") (pintype "bidirectional"))
      (node (ref "J35") (pin "1") (pinfunction "1_1") (pintype "bidirectional"))
      (node (ref "J36") (pin "1") (pinfunction "1_1") (pintype "bidirectional"))
      (node (ref "J37") (pin "1") (pinfunction "1_1") (pintype "bidirectional"))
      (node (ref "J38") (pin "1") (pinfunction "1_1") (pintype "bidirectional"))
      (node (ref "J39") (pin "1") (pinfunction "1_1") (pintype "bidirectional"))
      (node (ref "J4") (pin "1") (pinfunction "1_1") (pintype "bidirectional"))
      (node (ref "J40") (pin "1") (pinfunction "1_1") (pintype "bidirectional"))
      (node (ref "J41") (pin "1") (pinfunction "1_1") (pintype "bidirectional"))
      (node (ref "J42") (pin "1") (pinfunction "1_1") (pintype "bidirectional"))
      (node (ref "J43") (pin "1") (pinfunction "1_1") (pintype "bidirectional"))
      (node (ref "J44") (pin "1") (pinfunction "1_1") (pintype "bidirectional"))
      (node (ref "J45") (pin "1") (pinfunction "1_1") (pintype "bidirectional"))
      (node (ref "J46") (pin "1") (pinfunction "1_1") (pintype "bidirectional"))
      (node (ref "J47") (pin "1") (pinfunction "1_1") (pintype "bidirectional"))
      (node (ref "J48") (pin "1") (pinfunction "1_1") (pintype "bidirectional"))
      (node (ref "J49") (pin "1") (pinfunction "1_1") (pintype "bidirectional"))
      (node (ref "J5") (pin "1") (pinfunction "1_1") (pintype "bidirectional"))
      (node (ref "J50") (pin "1") (pinfunction "1_1") (pintype "bidirectional"))
      (node (ref "J51") (pin "1") (pinfunction "1_1") (pintype "bidirectional"))
      (node (ref "J52") (pin "1") (pinfunction "1_1") (pintype "bidirectional"))
      (node (ref "J53") (pin "1") (pinfunction "1_1") (pintype "bidirectional"))
      (node (ref "J54") (pin "1") (pinfunction "1_1") (pintype "bidirectional"))
      (node (ref "J55") (pin "1") (pinfunction "1_1") (pintype "bidirectional"))
      (node (ref "J56") (pin "1") (pinfunction "1_1") (pintype "bidirectional"))
      (node (ref "J57") (pin "1") (pinfunction "1_1") (pintype "bidirectional"))
      (node (ref "J58") (pin "1") (pinfunction "1_1") (pintype "bidirectional"))
      (node (ref "J59") (pin "1") (pinfunction "1_1") (pintype "bidirectional"))
      (node (ref "J6") (pin "1") (pinfunction "1_1") (pintype "bidirectional"))
      (node (ref "J60") (pin "1") (pinfunction "1_1") (pintype "bidirectional"))
      (node (ref "J61") (pin "1") (pinfunction "1_1") (pintype "bidirectional"))
      (node (ref "J62") (pin "1") (pinfunction "1_1") (pintype "bidirectional"))
      (node (ref "J63") (pin "1") (pinfunction "1_1") (pintype "bidirectional"))
      (node (ref "J64") (pin "1") (pinfunction "1_1") (pintype "bidirectional"))
      (node (ref "J65") (pin "1") (pinfunction "1_1") (pintype "bidirectional"))
      (node (ref "J66") (pin "1") (pinfunction "1_1") (pintype "bidirectional"))
      (node (ref "J67") (pin "1") (pinfunction "1_1") (pintype "bidirectional"))
      (node (ref "J68") (pin "1") (pinfunction "1_1") (pintype "bidirectional"))
      (node (ref "J69") (pin "1") (pinfunction "1_1") (pintype "bidirectional"))
      (node (ref "J7") (pin "1") (pinfunction "1_1") (pintype "bidirectional"))
      (node (ref "J70") (pin "1") (pinfunction "1_1") (pintype "bidirectional"))
      (node (ref "J71") (pin "1") (pinfunction "1_1") (pintype "bidirectional"))
      (node (ref "J72") (pin "1") (pinfunction "1_1") (pintype "bidirectional"))
      (node (ref "J73") (pin "1") (pinfunction "1_1") (pintype "bidirectional"))
      (node (ref "J74") (pin "1") (pinfunction "1_1") (pintype "bidirectional"))
      (node (ref "J75") (pin "1") (pinfunction "1_1") (pintype "bidirectional"))
      (node (ref "J76") (pin "1") (pinfunction "1_1") (pintype "bidirectional"))
      (node (ref "J77") (pin "1") (pinfunction "1_1") (pintype "bidirectional"))
      (node (ref "J78") (pin "1") (pinfunction "1_1") (pintype "bidirectional"))
      (node (ref "J79") (pin "1") (pinfunction "1_1") (pintype "bidirectional"))
      (node (ref "J8") (pin "1") (pinfunction "1_1") (pintype "bidirectional"))
      (node (ref "J80") (pin "1") (pinfunction "1_1") (pintype "bidirectional"))
      (node (ref "J81") (pin "1") (pinfunction "1_1") (pintype "bidirectional"))
      (node (ref "J82") (pin "1") (pinfunction "1_1") (pintype "bidirectional"))
      (node (ref "J83") (pin "1") (pinfunction "1_1") (pintype "bidirectional"))
      (node (ref "J84") (pin "1") (pinfunction "1_1") (pintype "bidirectional"))
      (node (ref "J85") (pin "1") (pinfunction "1_1") (pintype "bidirectional"))
      (node (ref "J86") (pin "1") (pinfunction "1_1") (pintype "bidirectional"))
      (node (ref "J87") (pin "1") (pinfunction "1_1") (pintype "bidirectional"))
      (node (ref "J88") (pin "1") (pinfunction "1_1") (pintype "bidirectional"))
      (node (ref "J89") (pin "1") (pinfunction "1_1") (pintype "bidirectional"))
      (node (ref "J9") (pin "1") (pinfunction "1_1") (pintype "bidirectional"))
      (node (ref "J90") (pin "1") (pinfunction "1_1") (pintype "bidirectional"))
      (node (ref "J91") (pin "1") (pinfunction "1_1") (pintype "bidirectional"))
      (node (ref "J92") (pin "1") (pinfunction "1_1") (pintype "bidirectional"))
      (node (ref "J93") (pin "1") (pinfunction "1_1") (pintype "bidirectional"))
      (node (ref "J94") (pin "1") (pinfunction "1_1") (pintype "bidirectional"))
      (node (ref "J95") (pin "1") (pinfunction "1_1") (pintype "bidirectional"))
      (node (ref "J96") (pin "1") (pinfunction "1_1") (pintype "bidirectional"))
      (node (ref "J97") (pin "1") (pinfunction "1_1") (pintype "bidirectional"))
      (node (ref "J98") (pin "1") (pinfunction "1_1") (pintype "bidirectional"))
      (node (ref "J99") (pin "1") (pinfunction "1_1") (pintype "bidirectional"))
      (node (ref "Q2") (pin "3") (pinfunction "D_3") (pintype "passive"))
      (node (ref "Q3") (pin "3") (pinfunction "D_3") (pintype "passive"))
      (node (ref "Q6") (pin "3") (pinfunction "D_3") (pintype "passive"))
      (node (ref "Q8") (pin "3") (pinfunction "D_3") (pintype "passive"))
      (node (ref "TER_CONN") (pin "1_1") (pinfunction "1_1_1") (pintype "bidirectional"))
      (node (ref "TER_CONN") (pin "1_2") (pinfunction "1_1_2") (pintype "bidirectional"))
      (node (ref "TER_CONN") (pin "1_3") (pinfunction "1_1_3") (pintype "bidirectional"))
      (node (ref "TER_CONN") (pin "1_4") (pinfunction "1_1_4") (pintype "bidirectional"))
    )
    (net (code "304") (name "XOUT") (class "Default")
      (node (ref "C14") (pin "2") (pinfunction "2_2") (pintype "bidirectional"))
      (node (ref "JP1") (pin "12") (pinfunction "12_12") (pintype "passive"))
      (node (ref "JP3") (pin "12") (pinfunction "12_12") (pintype "passive"))
      (node (ref "U1") (pin "X") (pinfunction "X_X") (pintype "bidirectional"))
    )
    (net (code "305") (name "YOUT") (class "Default")
      (node (ref "C13") (pin "2") (pinfunction "2_2") (pintype "bidirectional"))
      (node (ref "JP1") (pin "11") (pinfunction "11_11") (pintype "passive"))
      (node (ref "JP3") (pin "11") (pinfunction "11_11") (pintype "passive"))
      (node (ref "U1") (pin "Y") (pinfunction "Y_Y") (pintype "bidirectional"))
    )
    (net (code "306") (name "ZOUT") (class "Default")
      (node (ref "C12") (pin "2") (pinfunction "2_2") (pintype "bidirectional"))
      (node (ref "JP1") (pin "6") (pinfunction "6_6") (pintype "passive"))
      (node (ref "JP3") (pin "6") (pinfunction "6_6") (pintype "passive"))
      (node (ref "U1") (pin "Z") (pinfunction "Z_Z") (pintype "bidirectional"))
    )
    (net (code "307") (name "unconnected-(J64-Pad3)") (class "Default")
      (node (ref "J64") (pin "3") (pinfunction "3_3") (pintype "bidirectional"))
    )
    (net (code "308") (name "unconnected-(J128-Pad3)") (class "Default")
      (node (ref "J128") (pin "3") (pinfunction "3_3") (pintype "bidirectional"))
    )
    (net (code "309") (name "unconnected-(J192-Pad3)") (class "Default")
      (node (ref "J192") (pin "3") (pinfunction "3_3") (pintype "bidirectional"))
    )
    (net (code "310") (name "unconnected-(J256-Pad3)") (class "Default")
      (node (ref "J256") (pin "3") (pinfunction "3_3") (pintype "bidirectional"))
    )
    (net (code "311") (name "unconnected-(ONLINE/OFFLINE-O-Pad1)") (class "Default")
      (node (ref "ONLINE/OFFLINE") (pin "1") (pinfunction "O_1") (pintype "passive"))
    )
    (net (code "312") (name "unconnected-(U$2-PadP$1)") (class "Default")
      (node (ref "U$2") (pin "P$1") (pinfunction "P$1_P$1") (pintype "bidirectional"))
    )
    (net (code "313") (name "unconnected-(U$3-PadP$1)") (class "Default")
      (node (ref "U$3") (pin "P$1") (pinfunction "P$1_P$1") (pintype "bidirectional"))
    )
    (net (code "314") (name "unconnected-(U$4-AIN1-Pad86)") (class "Default")
      (node (ref "U$4") (pin "86") (pinfunction "AIN1_86") (pintype "passive"))
    )
    (net (code "315") (name "unconnected-(U$4-AIN2-Pad83)") (class "Default")
      (node (ref "U$4") (pin "83") (pinfunction "AIN2_83") (pintype "passive"))
    )
    (net (code "316") (name "unconnected-(U$4-AIN3-Pad84)") (class "Default")
      (node (ref "U$4") (pin "84") (pinfunction "AIN3_84") (pintype "passive"))
    )
    (net (code "317") (name "unconnected-(U$4-AIN4-Pad79)") (class "Default")
      (node (ref "U$4") (pin "79") (pinfunction "AIN4_79") (pintype "passive"))
    )
    (net (code "318") (name "unconnected-(U$4-AIN5-Pad82)") (class "Default")
      (node (ref "U$4") (pin "82") (pinfunction "AIN5_82") (pintype "passive"))
    )
    (net (code "319") (name "unconnected-(U$4-AIN6-Pad81)") (class "Default")
      (node (ref "U$4") (pin "81") (pinfunction "AIN6_81") (pintype "passive"))
    )
    (net (code "320") (name "unconnected-(U$4-CLKOUT2-Pad87)") (class "Default")
      (node (ref "U$4") (pin "87") (pinfunction "CLKOUT2_87") (pintype "input"))
    )
    (net (code "321") (name "unconnected-(U$4-EHRPWM1A-Pad60)") (class "Default")
      (node (ref "U$4") (pin "60") (pinfunction "EHRPWM1A_60") (pintype "passive"))
    )
    (net (code "322") (name "unconnected-(U$4-EHRPWM1B-Pad62)") (class "Default")
      (node (ref "U$4") (pin "62") (pinfunction "EHRPWM1B_62") (pintype "passive"))
    )
    (net (code "323") (name "unconnected-(U$4-EHRPWM2A-Pad19)") (class "Default")
      (node (ref "U$4") (pin "19") (pinfunction "EHRPWM2A_19") (pintype "passive"))
    )
    (net (code "324") (name "unconnected-(U$4-EHRPWM2B-Pad13)") (class "Default")
      (node (ref "U$4") (pin "13") (pinfunction "EHRPWM2B_13") (pintype "passive"))
    )
    (net (code "325") (name "unconnected-(U$4-GNDA_ADC-Pad80)") (class "Default")
      (node (ref "U$4") (pin "80") (pinfunction "GNDA_ADC_80") (pintype "passive"))
    )
    (net (code "326") (name "unconnected-(U$4-GPIO0_7-Pad88)") (class "Default")
      (node (ref "U$4") (pin "88") (pinfunction "GPIO0_7_88") (pintype "passive"))
    )
    (net (code "327") (name "unconnected-(U$4-GPIO0_26-Pad14)") (class "Default")
      (node (ref "U$4") (pin "14") (pinfunction "GPIO0_26_14") (pintype "passive"))
    )
    (net (code "328") (name "unconnected-(U$4-GPIO0_27-Pad17)") (class "Default")
      (node (ref "U$4") (pin "17") (pinfunction "GPIO0_27_17") (pintype "passive"))
    )
    (net (code "329") (name "unconnected-(U$4-GPIO1_0-Pad25)") (class "Default")
      (node (ref "U$4") (pin "25") (pinfunction "GPIO1_0_25") (pintype "passive"))
    )
    (net (code "330") (name "unconnected-(U$4-GPIO1_1-Pad24)") (class "Default")
      (node (ref "U$4") (pin "24") (pinfunction "GPIO1_1_24") (pintype "passive"))
    )
    (net (code "331") (name "unconnected-(U$4-GPIO1_2-Pad5)") (class "Default")
      (node (ref "U$4") (pin "5") (pinfunction "GPIO1_2_5") (pintype "passive"))
    )
    (net (code "332") (name "unconnected-(U$4-GPIO1_3-Pad6)") (class "Default")
      (node (ref "U$4") (pin "6") (pinfunction "GPIO1_3_6") (pintype "passive"))
    )
    (net (code "333") (name "unconnected-(U$4-GPIO1_4-Pad23)") (class "Default")
      (node (ref "U$4") (pin "23") (pinfunction "GPIO1_4_23") (pintype "passive"))
    )
    (net (code "334") (name "unconnected-(U$4-GPIO1_5-Pad22)") (class "Default")
      (node (ref "U$4") (pin "22") (pinfunction "GPIO1_5_22") (pintype "passive"))
    )
    (net (code "335") (name "unconnected-(U$4-GPIO1_6-Pad3)") (class "Default")
      (node (ref "U$4") (pin "3") (pinfunction "GPIO1_6_3") (pintype "passive"))
    )
    (net (code "336") (name "unconnected-(U$4-GPIO1_7-Pad4)") (class "Default")
      (node (ref "U$4") (pin "4") (pinfunction "GPIO1_7_4") (pintype "passive"))
    )
    (net (code "337") (name "unconnected-(U$4-GPIO1_12-Pad12)") (class "Default")
      (node (ref "U$4") (pin "12") (pinfunction "GPIO1_12_12") (pintype "passive"))
    )
    (net (code "338") (name "unconnected-(U$4-GPIO1_13-Pad11)") (class "Default")
      (node (ref "U$4") (pin "11") (pinfunction "GPIO1_13_11") (pintype "passive"))
    )
    (net (code "339") (name "unconnected-(U$4-GPIO1_14-Pad16)") (class "Default")
      (node (ref "U$4") (pin "16") (pinfunction "GPIO1_14_16") (pintype "passive"))
    )
    (net (code "340") (name "unconnected-(U$4-GPIO1_15-Pad15)") (class "Default")
      (node (ref "U$4") (pin "15") (pinfunction "GPIO1_15_15") (pintype "passive"))
    )
    (net (code "341") (name "unconnected-(U$4-GPIO1_16-Pad61)") (class "Default")
      (node (ref "U$4") (pin "61") (pinfunction "GPIO1_16_61") (pintype "passive"))
    )
    (net (code "342") (name "unconnected-(U$4-GPIO1_17-Pad69)") (class "Default")
      (node (ref "U$4") (pin "69") (pinfunction "GPIO1_17_69") (pintype "passive"))
    )
    (net (code "343") (name "unconnected-(U$4-GPIO1_28-Pad58)") (class "Default")
      (node (ref "U$4") (pin "58") (pinfunction "GPIO1_28_58") (pintype "passive"))
    )
    (net (code "344") (name "unconnected-(U$4-GPIO1_29-Pad26)") (class "Default")
      (node (ref "U$4") (pin "26") (pinfunction "GPIO1_29_26") (pintype "passive"))
    )
    (net (code "345") (name "unconnected-(U$4-GPIO1_30-Pad21)") (class "Default")
      (node (ref "U$4") (pin "21") (pinfunction "GPIO1_30_21") (pintype "passive"))
    )
    (net (code "346") (name "unconnected-(U$4-GPIO1_31-Pad20)") (class "Default")
      (node (ref "U$4") (pin "20") (pinfunction "GPIO1_31_20") (pintype "passive"))
    )
    (net (code "347") (name "unconnected-(U$4-GPIO2_1-Pad18)") (class "Default")
      (node (ref "U$4") (pin "18") (pinfunction "GPIO2_1_18") (pintype "passive"))
    )
    (net (code "348") (name "unconnected-(U$4-GPIO2_22-Pad27)") (class "Default")
      (node (ref "U$4") (pin "27") (pinfunction "GPIO2_22_27") (pintype "passive"))
    )
    (net (code "349") (name "unconnected-(U$4-GPIO2_23-Pad29)") (class "Default")
      (node (ref "U$4") (pin "29") (pinfunction "GPIO2_23_29") (pintype "passive"))
    )
    (net (code "350") (name "unconnected-(U$4-GPIO2_24-Pad28)") (class "Default")
      (node (ref "U$4") (pin "28") (pinfunction "GPIO2_24_28") (pintype "passive"))
    )
    (net (code "351") (name "unconnected-(U$4-GPIO2_25-Pad30)") (class "Default")
      (node (ref "U$4") (pin "30") (pinfunction "GPIO2_25_30") (pintype "passive"))
    )
    (net (code "352") (name "unconnected-(U$4-GPIO3_19-Pad73)") (class "Default")
      (node (ref "U$4") (pin "73") (pinfunction "GPIO3_19_73") (pintype "passive"))
    )
    (net (code "353") (name "unconnected-(U$4-GPIO3_21-Pad71)") (class "Default")
      (node (ref "U$4") (pin "71") (pinfunction "GPIO3_21_71") (pintype "passive"))
    )
    (net (code "354") (name "unconnected-(U$4-I2C1_SCL-Pad63)") (class "Default")
      (node (ref "U$4") (pin "63") (pinfunction "I2C1_SCL_63") (pintype "passive"))
    )
    (net (code "355") (name "unconnected-(U$4-I2C1_SDA-Pad64)") (class "Default")
      (node (ref "U$4") (pin "64") (pinfunction "I2C1_SDA_64") (pintype "passive"))
    )
    (net (code "356") (name "unconnected-(U$4-I2C2_SCL-Pad65)") (class "Default")
      (node (ref "U$4") (pin "65") (pinfunction "I2C2_SCL_65") (pintype "passive"))
    )
    (net (code "357") (name "unconnected-(U$4-I2C2_SDA-Pad66)") (class "Default")
      (node (ref "U$4") (pin "66") (pinfunction "I2C2_SDA_66") (pintype "passive"))
    )
    (net (code "358") (name "unconnected-(U$4-PWR_BUT-Pad55)") (class "Default")
      (node (ref "U$4") (pin "55") (pinfunction "PWR_BUT_55") (pintype "passive"))
    )
    (net (code "359") (name "unconnected-(U$4-SPI1_CS0-Pad74)") (class "Default")
      (node (ref "U$4") (pin "74") (pinfunction "SPI1_CS0_74") (pintype "passive"))
    )
    (net (code "360") (name "unconnected-(U$4-SPI1_DI-Pad76)") (class "Default")
      (node (ref "U$4") (pin "76") (pinfunction "SPI1_DI_76") (pintype "passive"))
    )
    (net (code "361") (name "unconnected-(U$4-SPI1_DO-Pad75)") (class "Default")
      (node (ref "U$4") (pin "75") (pinfunction "SPI1_DO_75") (pintype "passive"))
    )
    (net (code "362") (name "unconnected-(U$4-SPI1_SCLK-Pad77)") (class "Default")
      (node (ref "U$4") (pin "77") (pinfunction "SPI1_SCLK_77") (pintype "passive"))
    )
    (net (code "363") (name "unconnected-(U$4-SYS_5V-Pad54)") (class "Default")
      (node (ref "U$4") (pin "54") (pinfunction "SYS_5V_54") (pintype "passive"))
    )
    (net (code "364") (name "unconnected-(U$4-SYS_RESETN-Pad56)") (class "Default")
      (node (ref "U$4") (pin "56") (pinfunction "SYS_RESETN_56") (pintype "passive"))
    )
    (net (code "365") (name "unconnected-(U$4-TIMER4-Pad7)") (class "Default")
      (node (ref "U$4") (pin "7") (pinfunction "TIMER4_7") (pintype "passive"))
    )
    (net (code "366") (name "unconnected-(U$4-TIMER5-Pad9)") (class "Default")
      (node (ref "U$4") (pin "9") (pinfunction "TIMER5_9") (pintype "passive"))
    )
    (net (code "367") (name "unconnected-(U$4-TIMER6-Pad10)") (class "Default")
      (node (ref "U$4") (pin "10") (pinfunction "TIMER6_10") (pintype "passive"))
    )
    (net (code "368") (name "unconnected-(U$4-TIMER7-Pad8)") (class "Default")
      (node (ref "U$4") (pin "8") (pinfunction "TIMER7_8") (pintype "passive"))
    )
    (net (code "369") (name "unconnected-(U$4-UART1_RXD-Pad72)") (class "Default")
      (node (ref "U$4") (pin "72") (pinfunction "UART1_RXD_72") (pintype "passive"))
    )
    (net (code "370") (name "unconnected-(U$4-UART1_TXD-Pad70)") (class "Default")
      (node (ref "U$4") (pin "70") (pinfunction "UART1_TXD_70") (pintype "passive"))
    )
    (net (code "371") (name "unconnected-(U$4-UART2_RXD-Pad68)") (class "Default")
      (node (ref "U$4") (pin "68") (pinfunction "UART2_RXD_68") (pintype "passive"))
    )
    (net (code "372") (name "unconnected-(U$4-UART2_TXD-Pad67)") (class "Default")
      (node (ref "U$4") (pin "67") (pinfunction "UART2_TXD_67") (pintype "passive"))
    )
    (net (code "373") (name "unconnected-(U$4-UART3_CTSN-Pad36)") (class "Default")
      (node (ref "U$4") (pin "36") (pinfunction "UART3_CTSN_36") (pintype "passive"))
    )
    (net (code "374") (name "unconnected-(U$4-UART3_RTSN-Pad34)") (class "Default")
      (node (ref "U$4") (pin "34") (pinfunction "UART3_RTSN_34") (pintype "passive"))
    )
    (net (code "375") (name "unconnected-(U$4-UART4_CTSN-Pad35)") (class "Default")
      (node (ref "U$4") (pin "35") (pinfunction "UART4_CTSN_35") (pintype "passive"))
    )
    (net (code "376") (name "unconnected-(U$4-UART4_RTSN-Pad33)") (class "Default")
      (node (ref "U$4") (pin "33") (pinfunction "UART4_RTSN_33") (pintype "passive"))
    )
    (net (code "377") (name "unconnected-(U$4-UART4_RXD-Pad57)") (class "Default")
      (node (ref "U$4") (pin "57") (pinfunction "UART4_RXD_57") (pintype "passive"))
    )
    (net (code "378") (name "unconnected-(U$4-UART4_TXD-Pad59)") (class "Default")
      (node (ref "U$4") (pin "59") (pinfunction "UART4_TXD_59") (pintype "passive"))
    )
    (net (code "379") (name "unconnected-(U$4-UART5_CTSN-Pad31)") (class "Default")
      (node (ref "U$4") (pin "31") (pinfunction "UART5_CTSN_31") (pintype "passive"))
    )
    (net (code "380") (name "unconnected-(U$4-UART5_RTSN-Pad32)") (class "Default")
      (node (ref "U$4") (pin "32") (pinfunction "UART5_RTSN_32") (pintype "passive"))
    )
    (net (code "381") (name "unconnected-(U$4-UART5_RXD-Pad38)") (class "Default")
      (node (ref "U$4") (pin "38") (pinfunction "UART5_RXD_38") (pintype "passive"))
    )
    (net (code "382") (name "unconnected-(U$4-UART5_TXD-Pad37)") (class "Default")
      (node (ref "U$4") (pin "37") (pinfunction "UART5_TXD_37") (pintype "passive"))
    )
    (net (code "383") (name "unconnected-(U$4-VDD_ADC-Pad78)") (class "Default")
      (node (ref "U$4") (pin "78") (pinfunction "VDD_ADC_78") (pintype "passive"))
    )
    (net (code "384") (name "unconnected-(U1-PadNC1)") (class "Default")
      (node (ref "U1") (pin "NC1") (pinfunction "NC1_NC1") (pintype "bidirectional"))
    )
    (net (code "385") (name "unconnected-(U1-PadNC2)") (class "Default")
      (node (ref "U1") (pin "NC2") (pinfunction "NC2_NC2") (pintype "bidirectional"))
    )
    (net (code "386") (name "unconnected-(U1-PadNC3)") (class "Default")
      (node (ref "U1") (pin "NC3") (pinfunction "NC3_NC3") (pintype "bidirectional"))
    )
    (net (code "387") (name "unconnected-(U1-PadNC4)") (class "Default")
      (node (ref "U1") (pin "NC4") (pinfunction "NC4_NC4") (pintype "bidirectional"))
    )
    (net (code "388") (name "unconnected-(U1-PadNC5)") (class "Default")
      (node (ref "U1") (pin "NC5") (pinfunction "NC5_NC5") (pintype "bidirectional"))
    )
    (net (code "389") (name "unconnected-(U1-PadNC6)") (class "Default")
      (node (ref "U1") (pin "NC6") (pinfunction "NC6_NC6") (pintype "bidirectional"))
    )
    (net (code "390") (name "unconnected-(U1-PadST)") (class "Default")
      (node (ref "U1") (pin "ST") (pinfunction "ST_ST") (pintype "bidirectional"))
    )
  )
)
